# extension.net
KiCad netlist of a schematic drawn in EAGLE
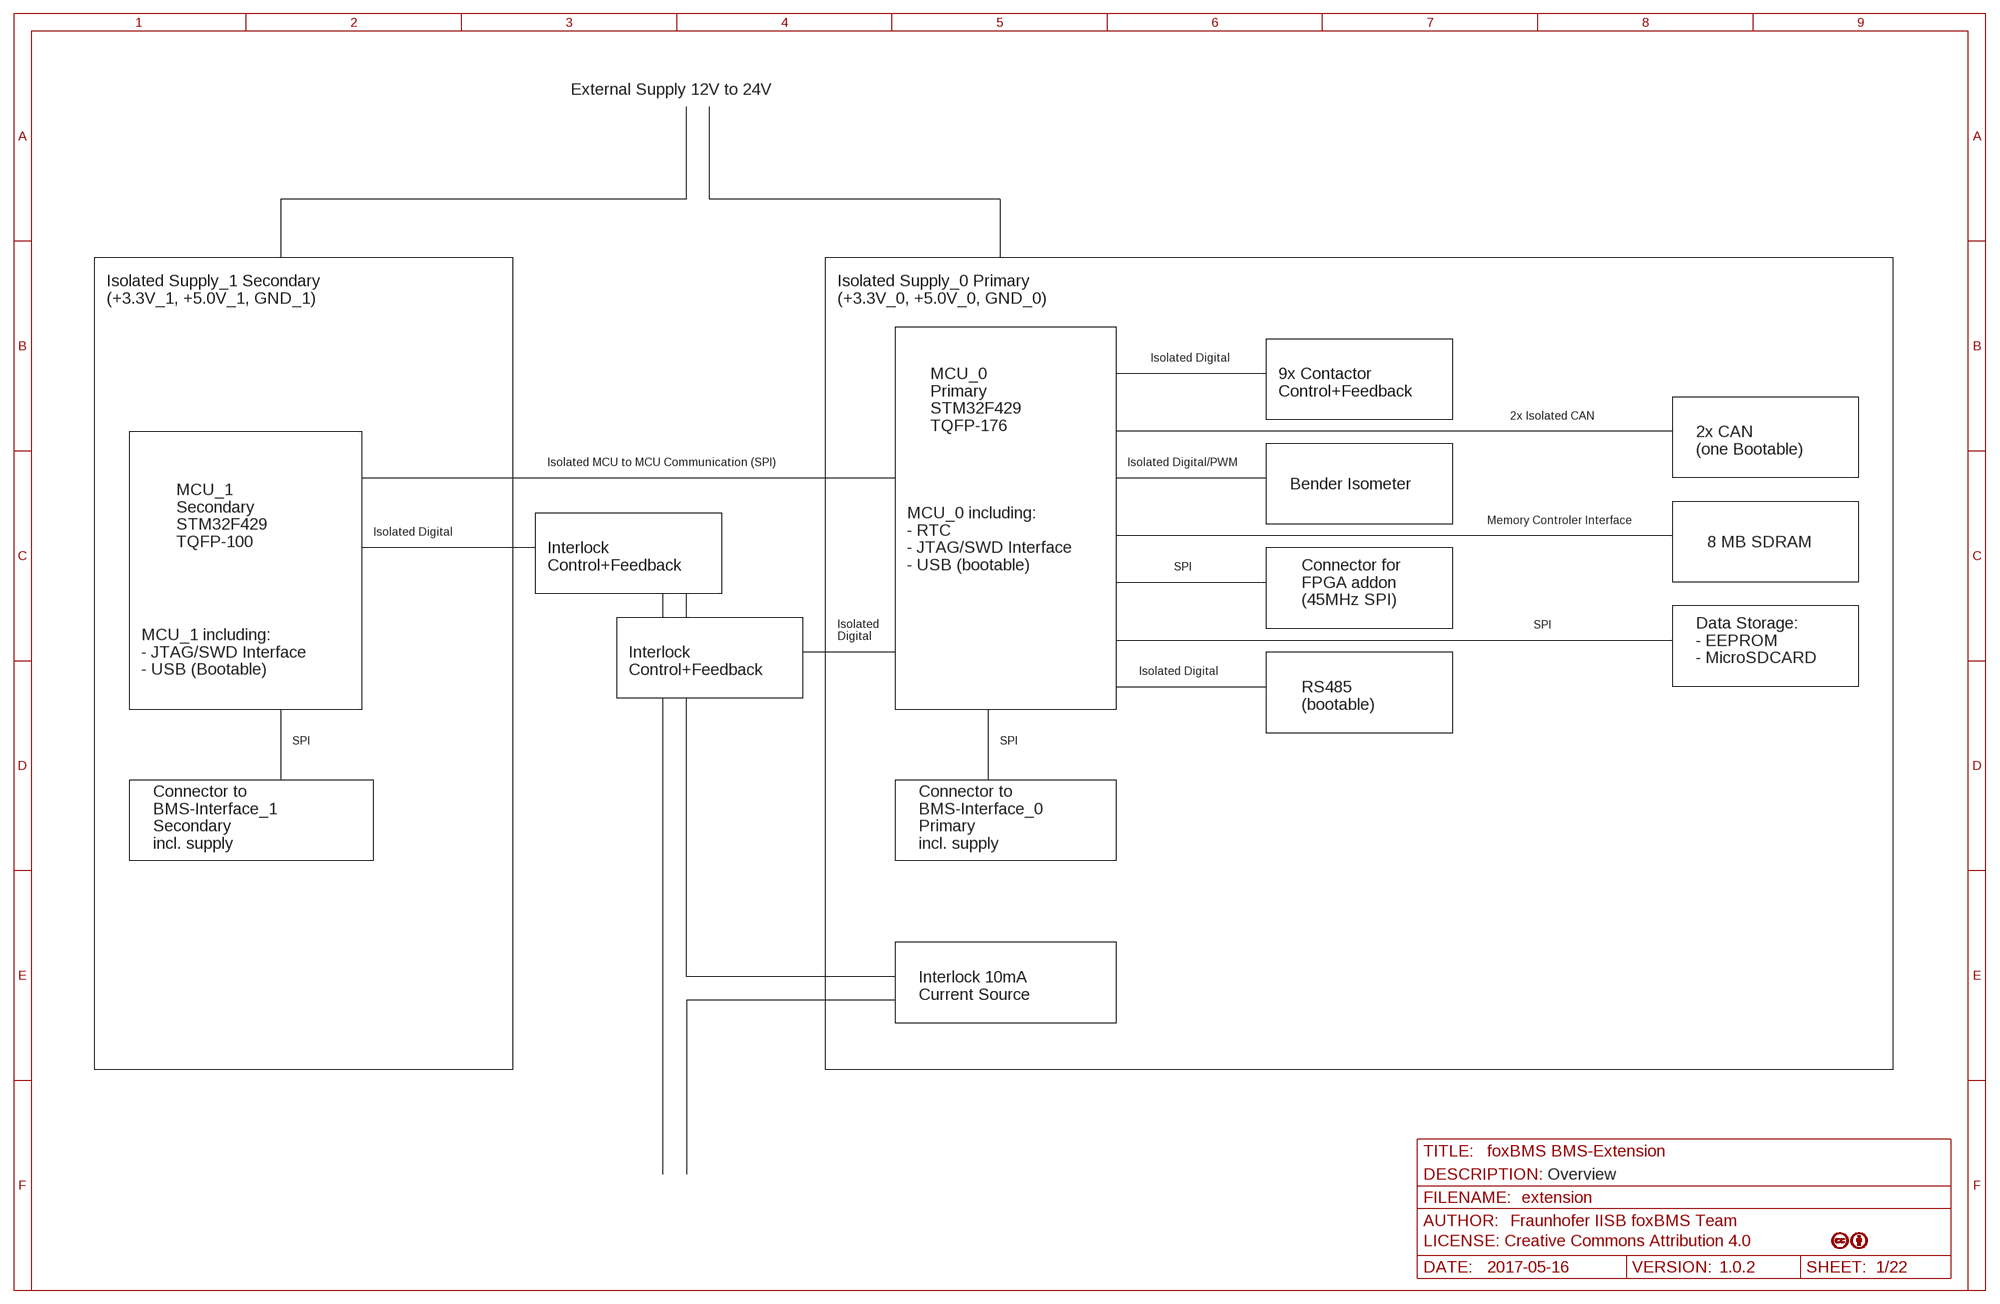
[diagram p0: schematic, sheet 1]
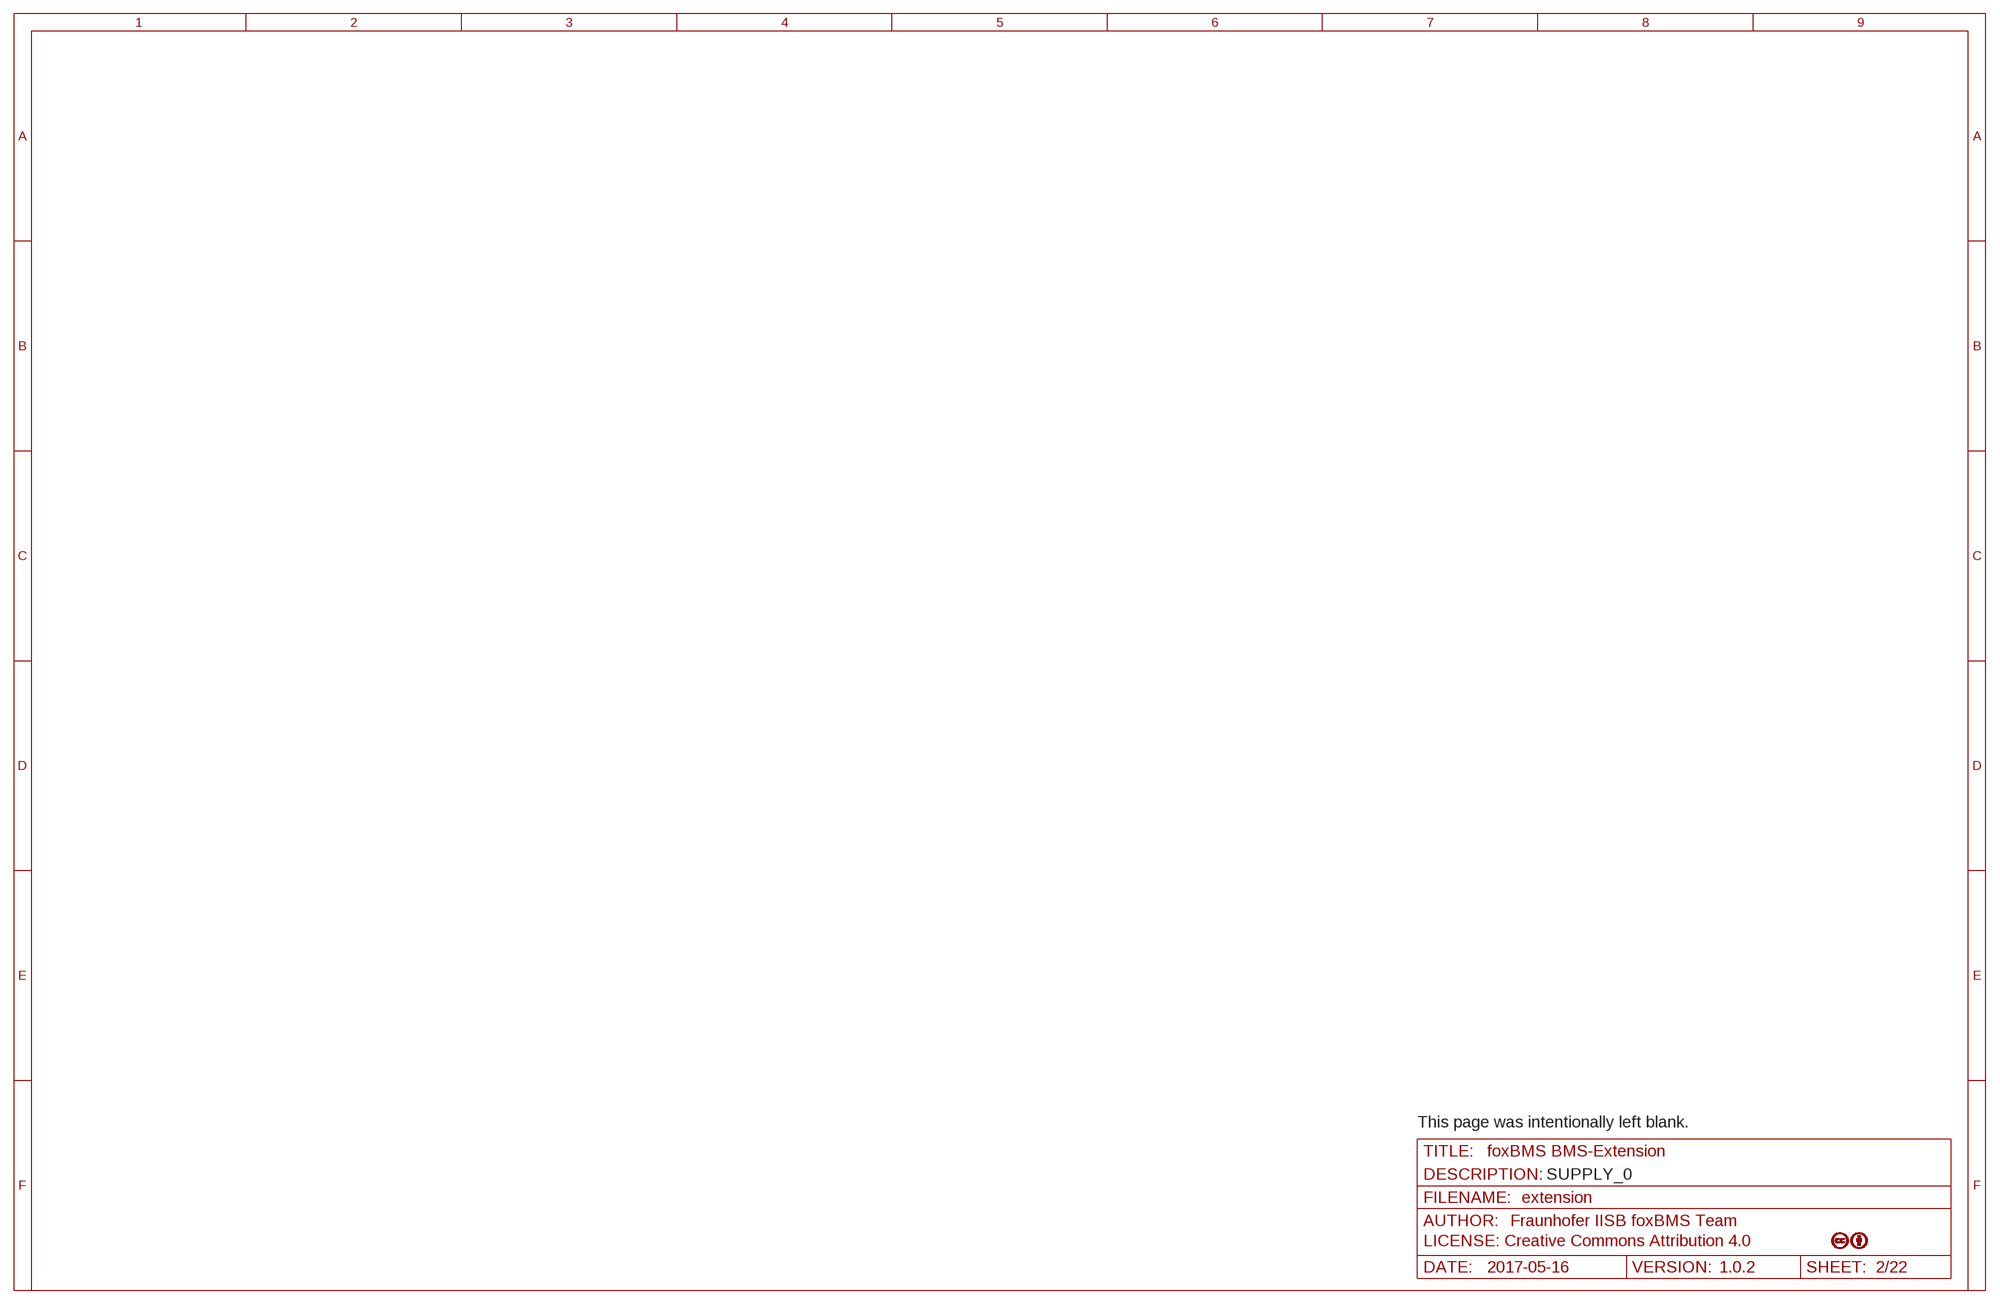
[diagram p1: schematic, sheet 2]
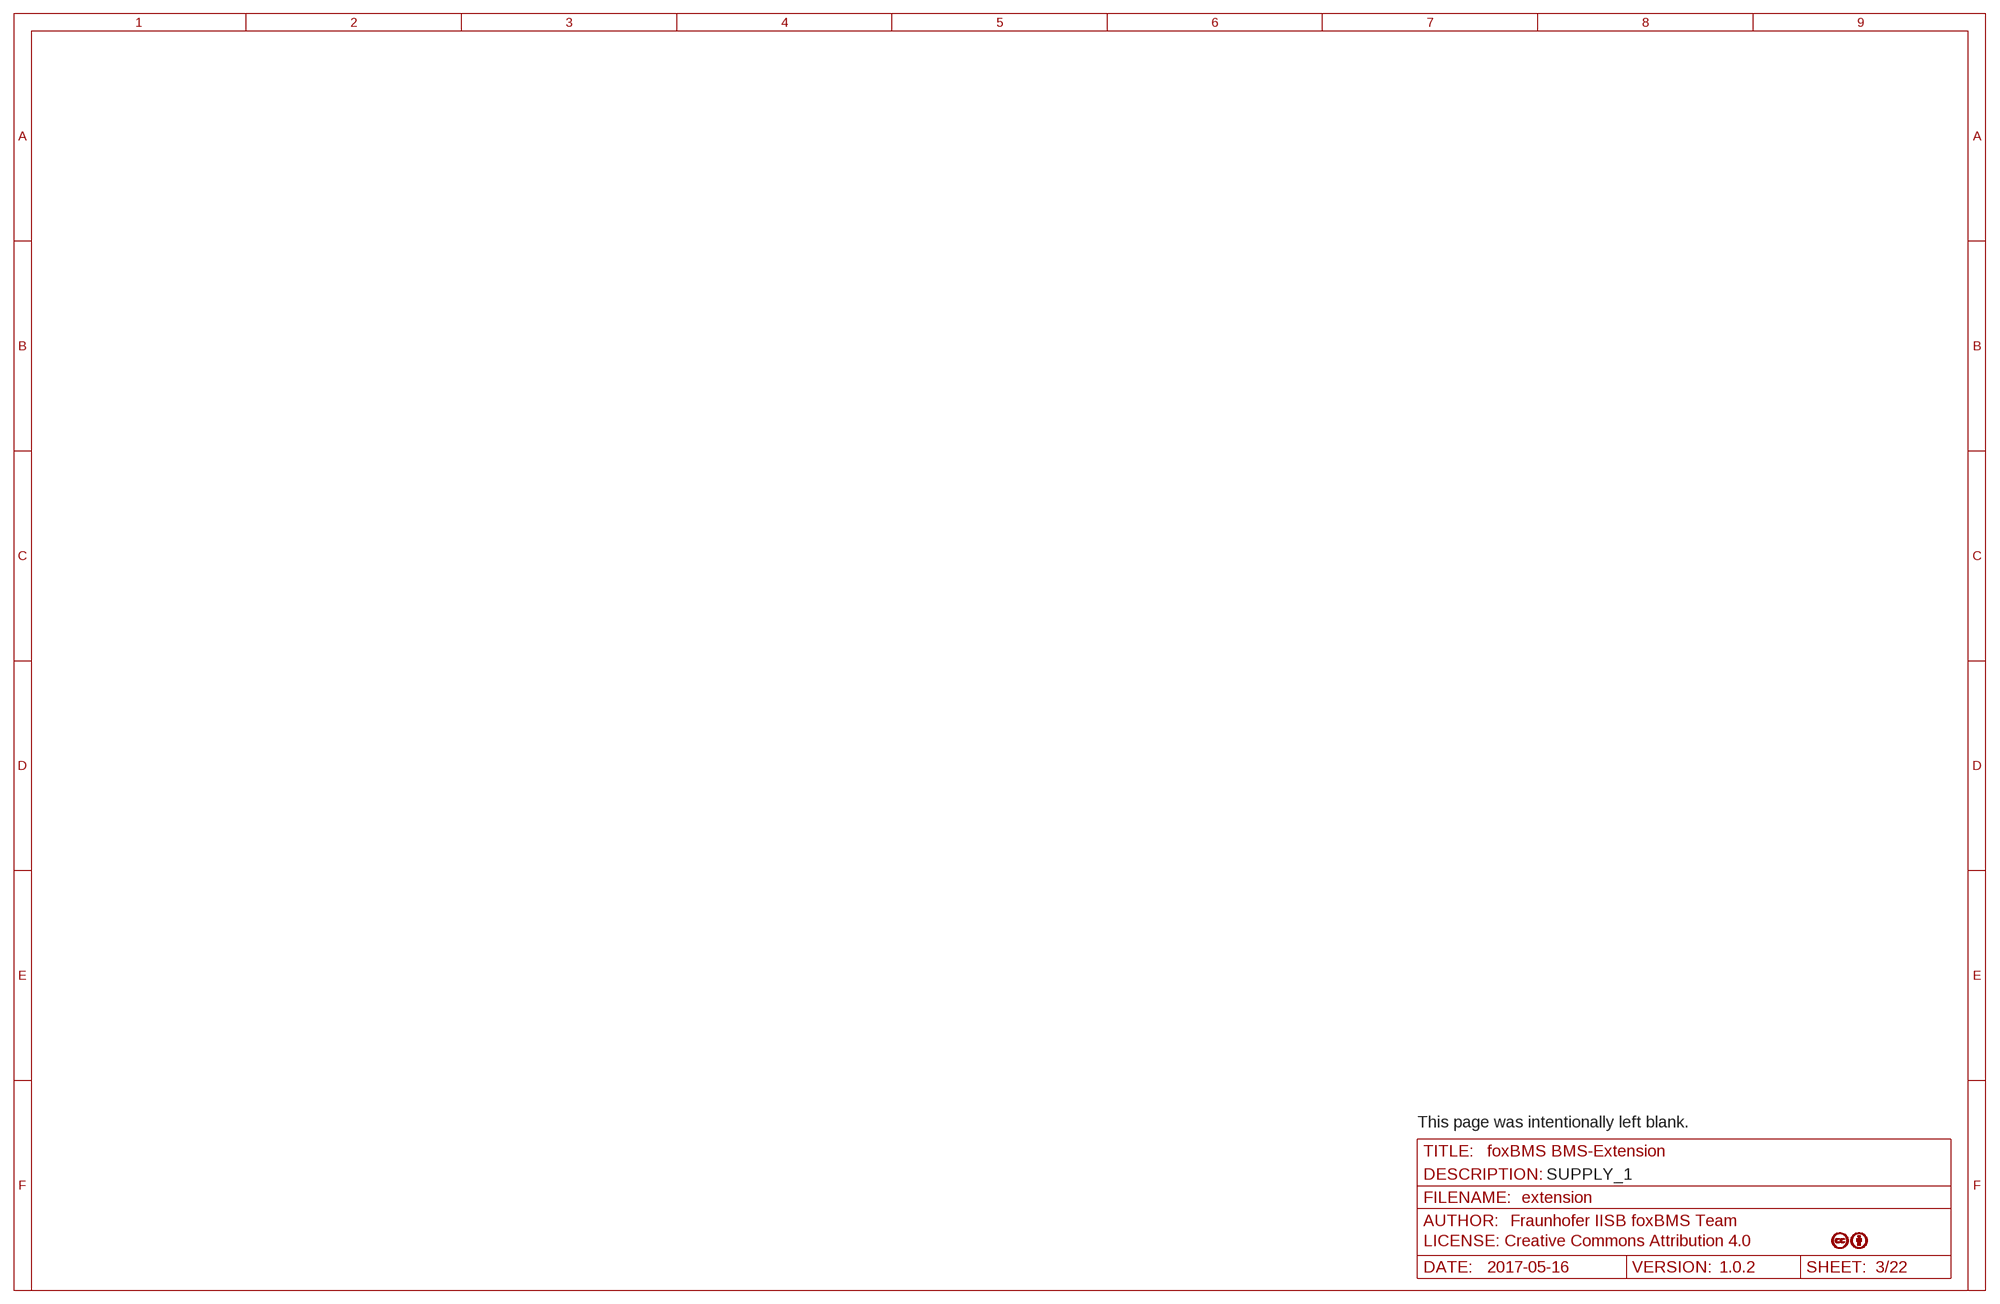
[diagram p2: schematic, sheet 3]
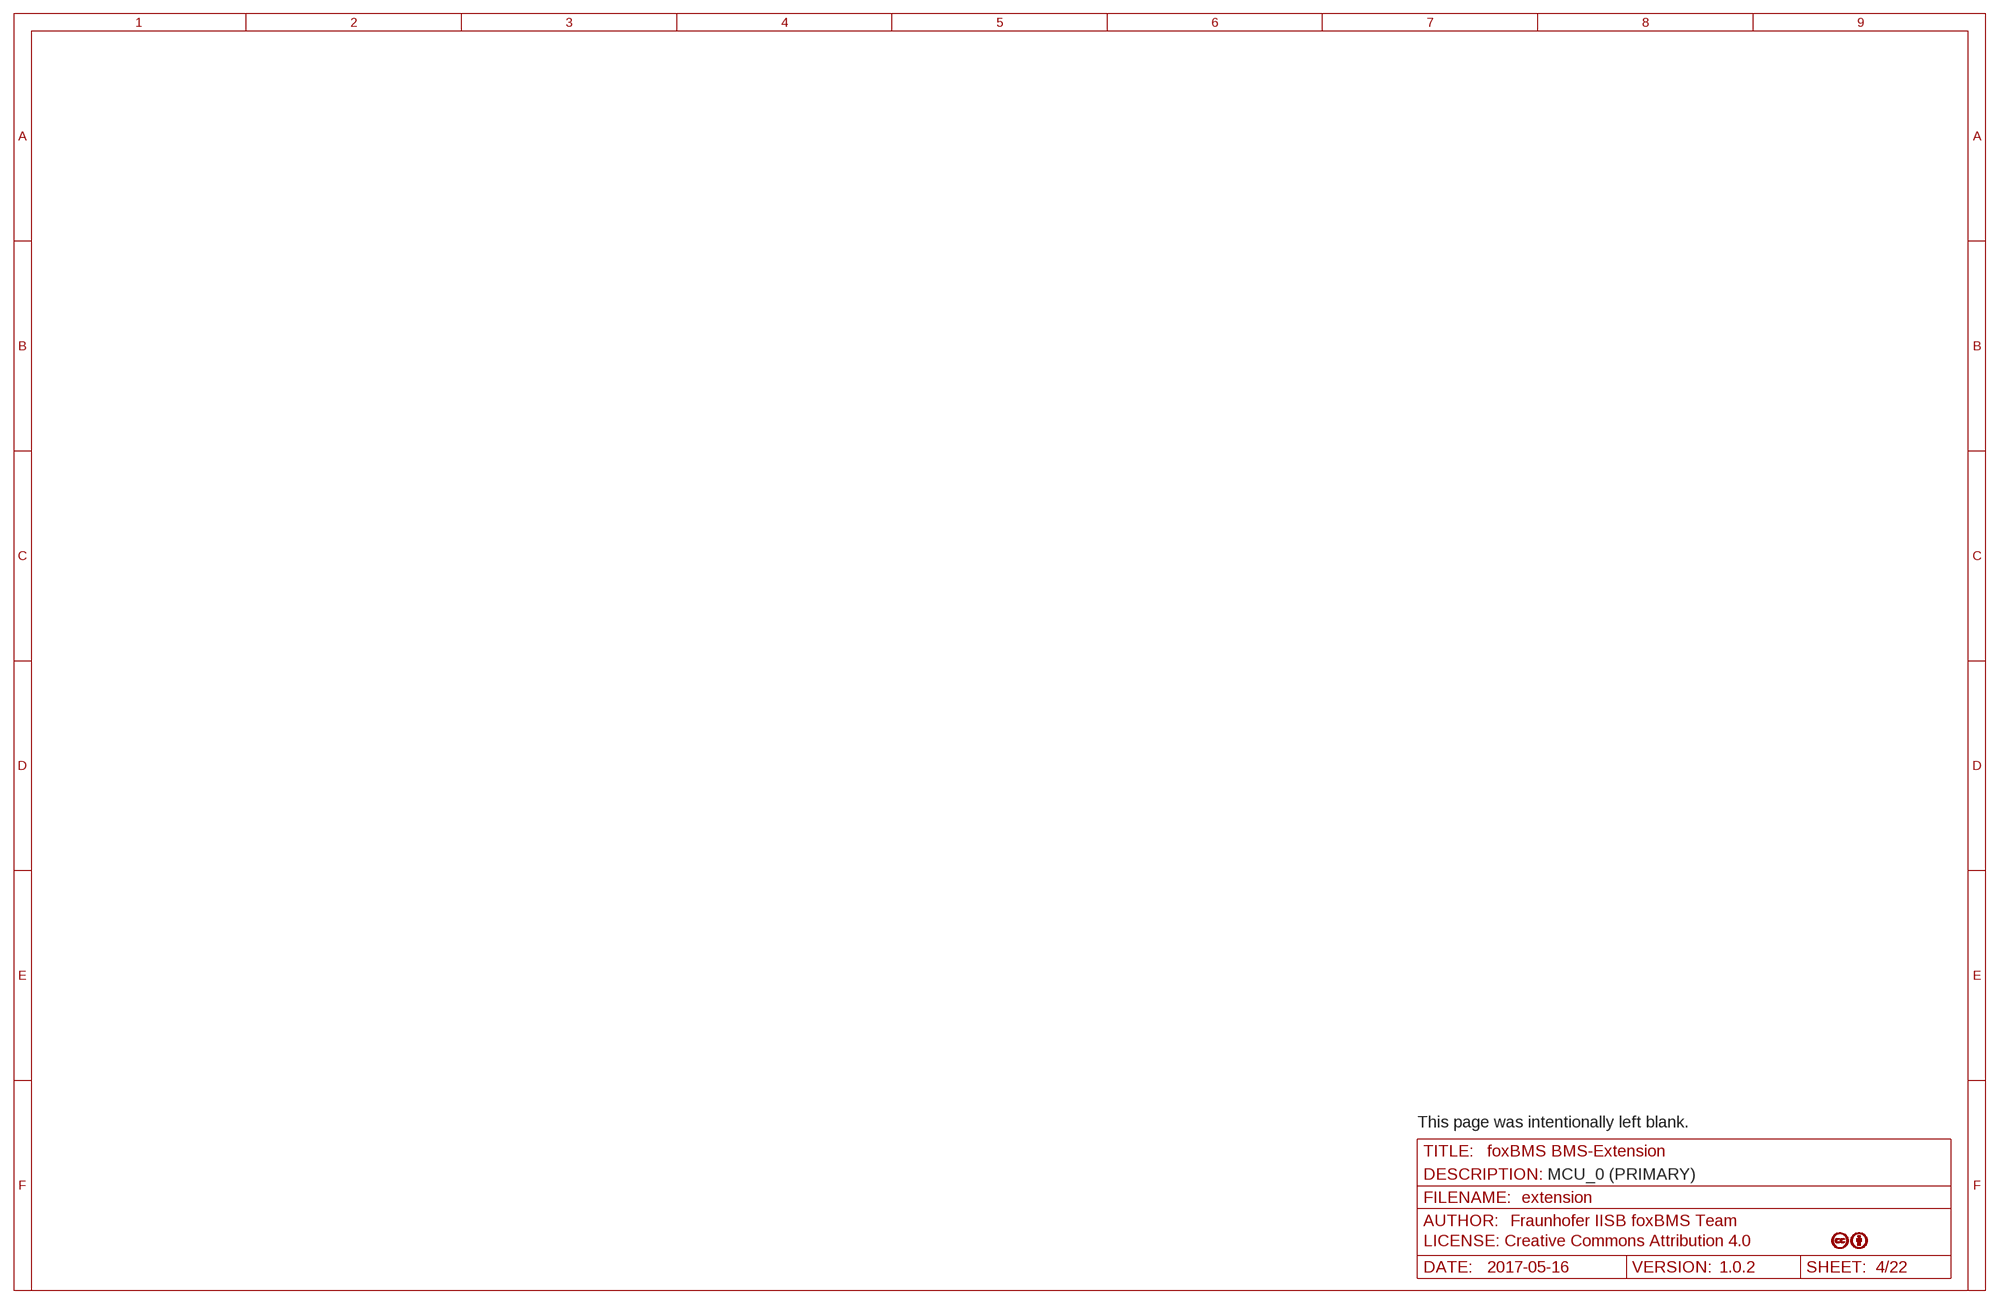
[diagram p3: schematic, sheet 4]
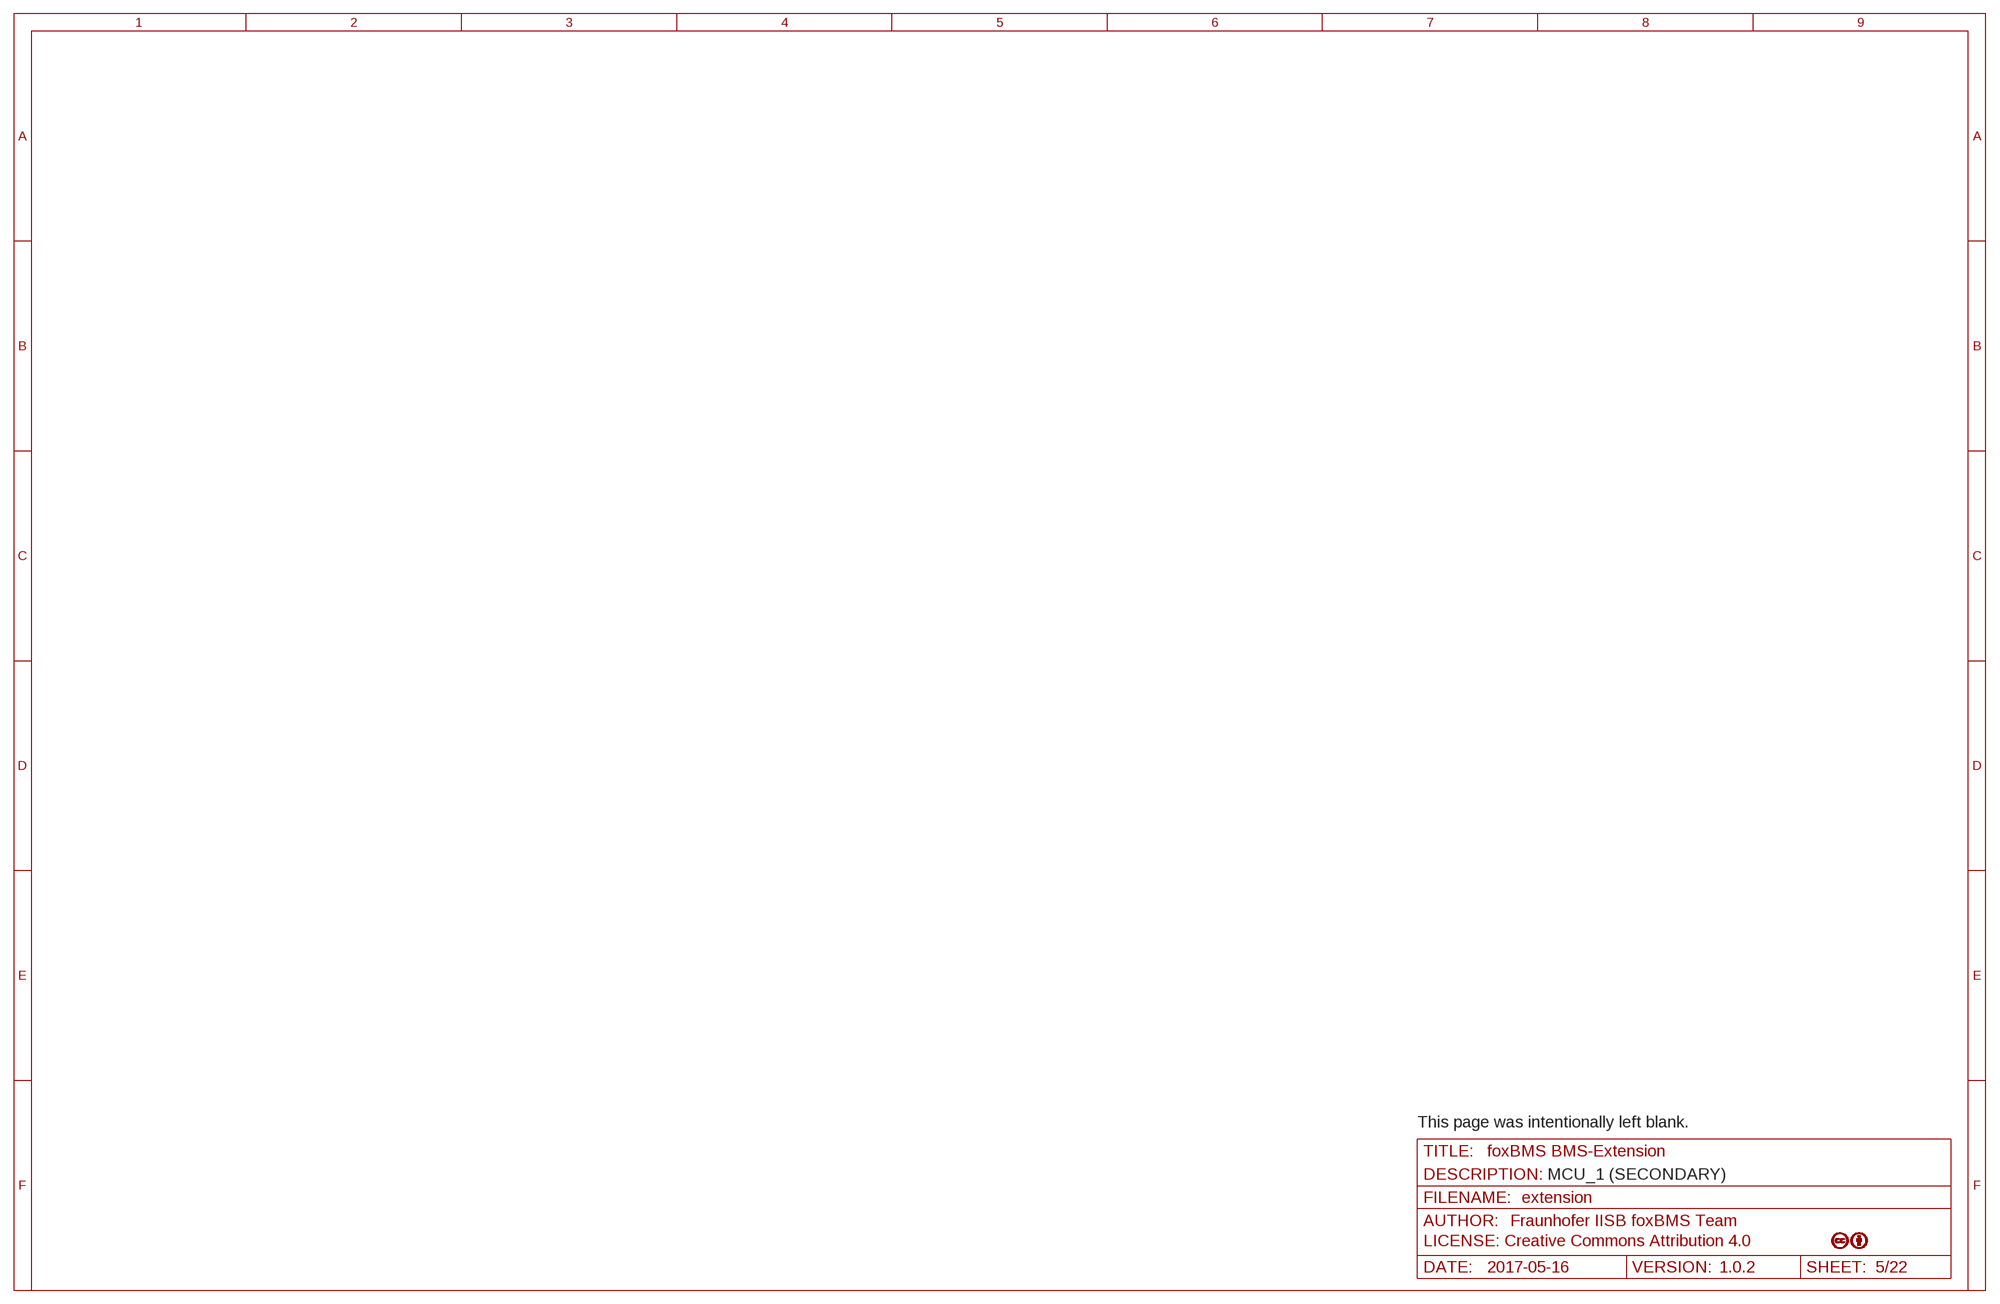
[diagram p4: schematic, sheet 5]
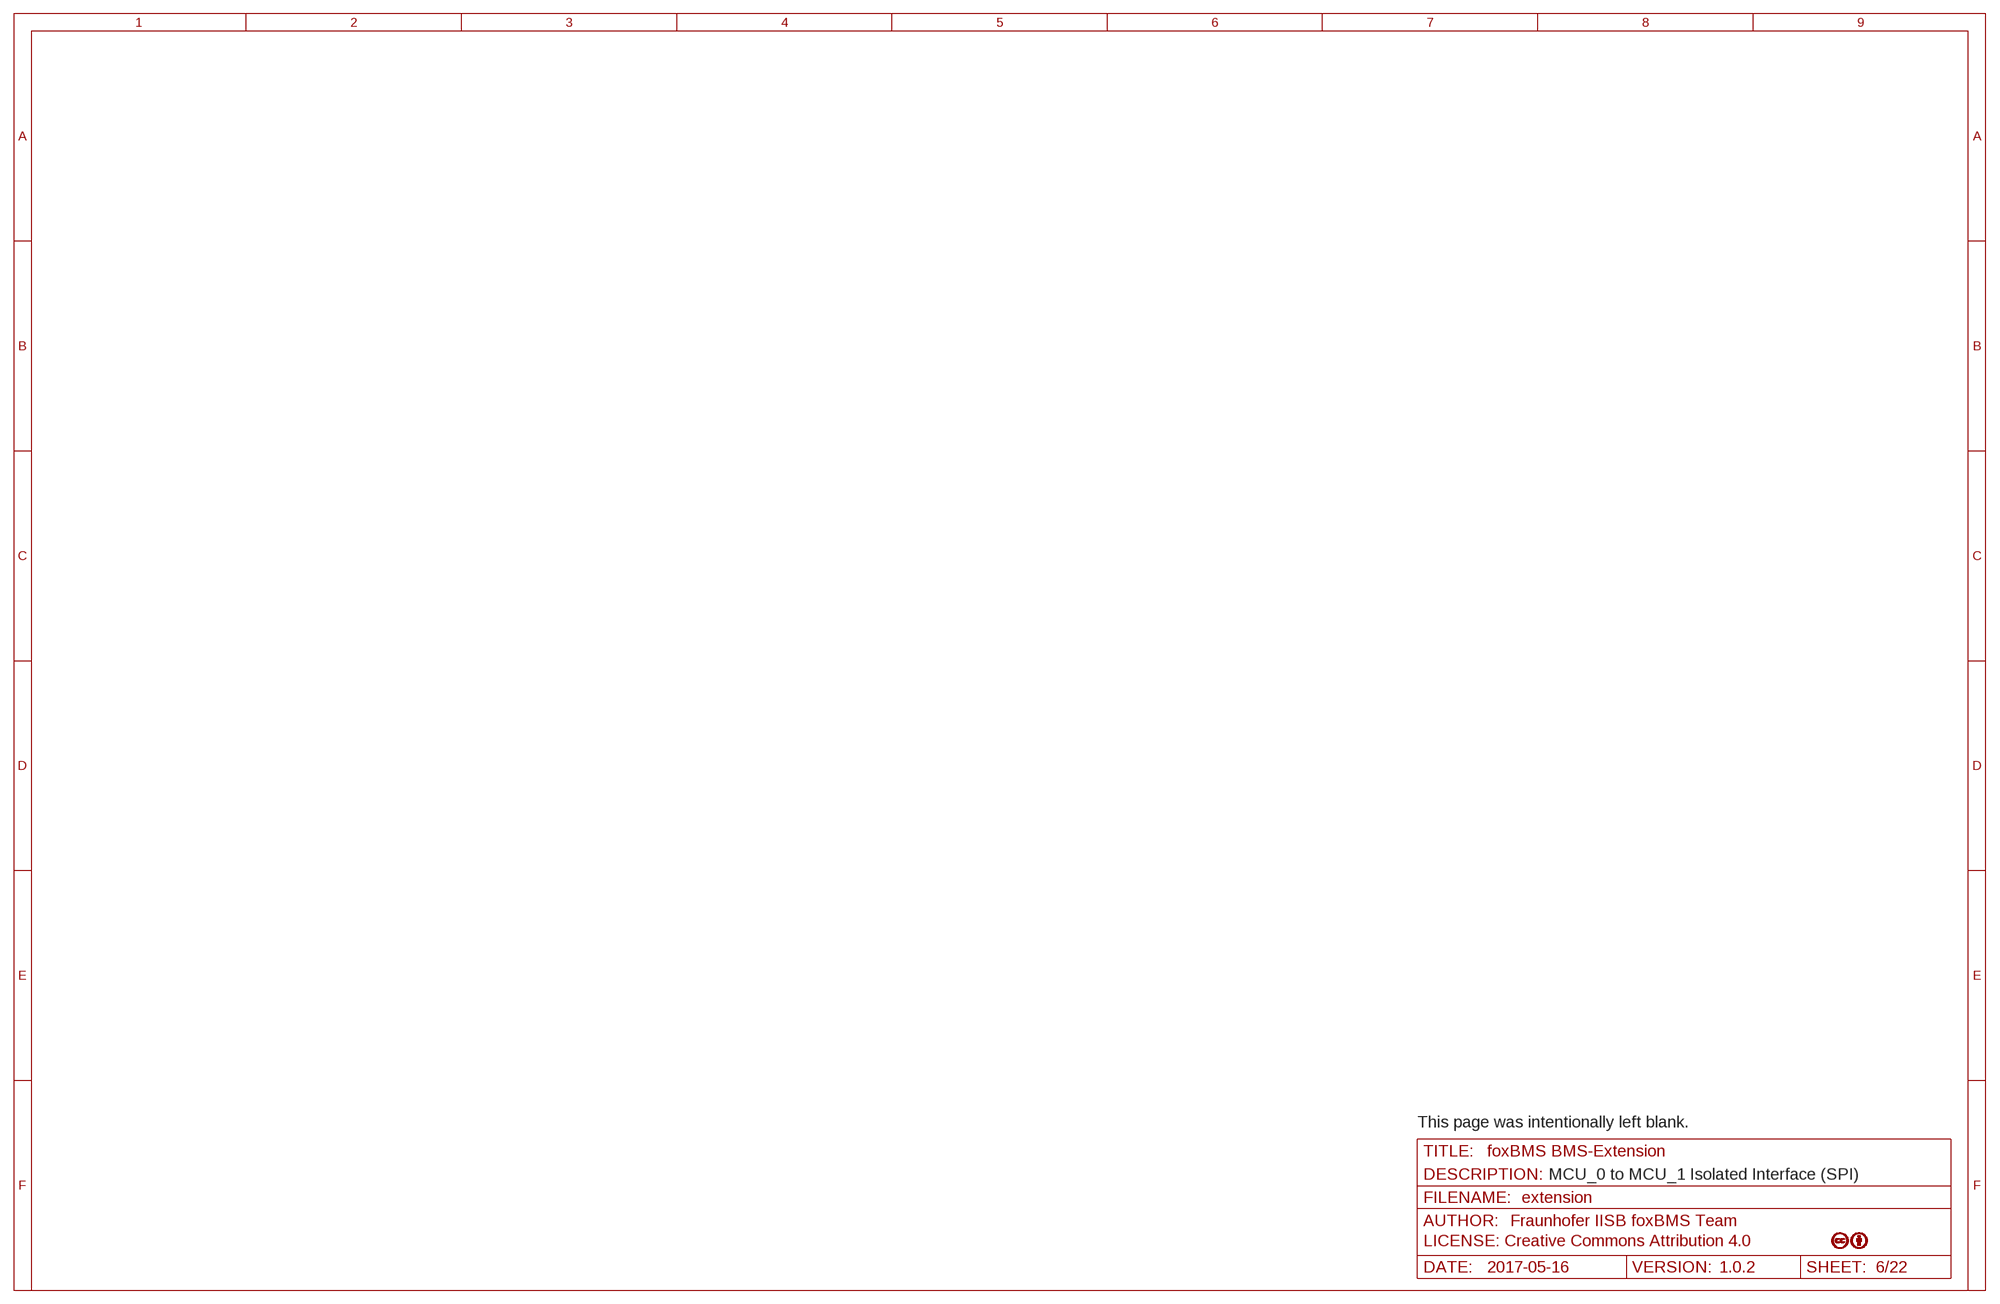
[diagram p5: schematic, sheet 6]
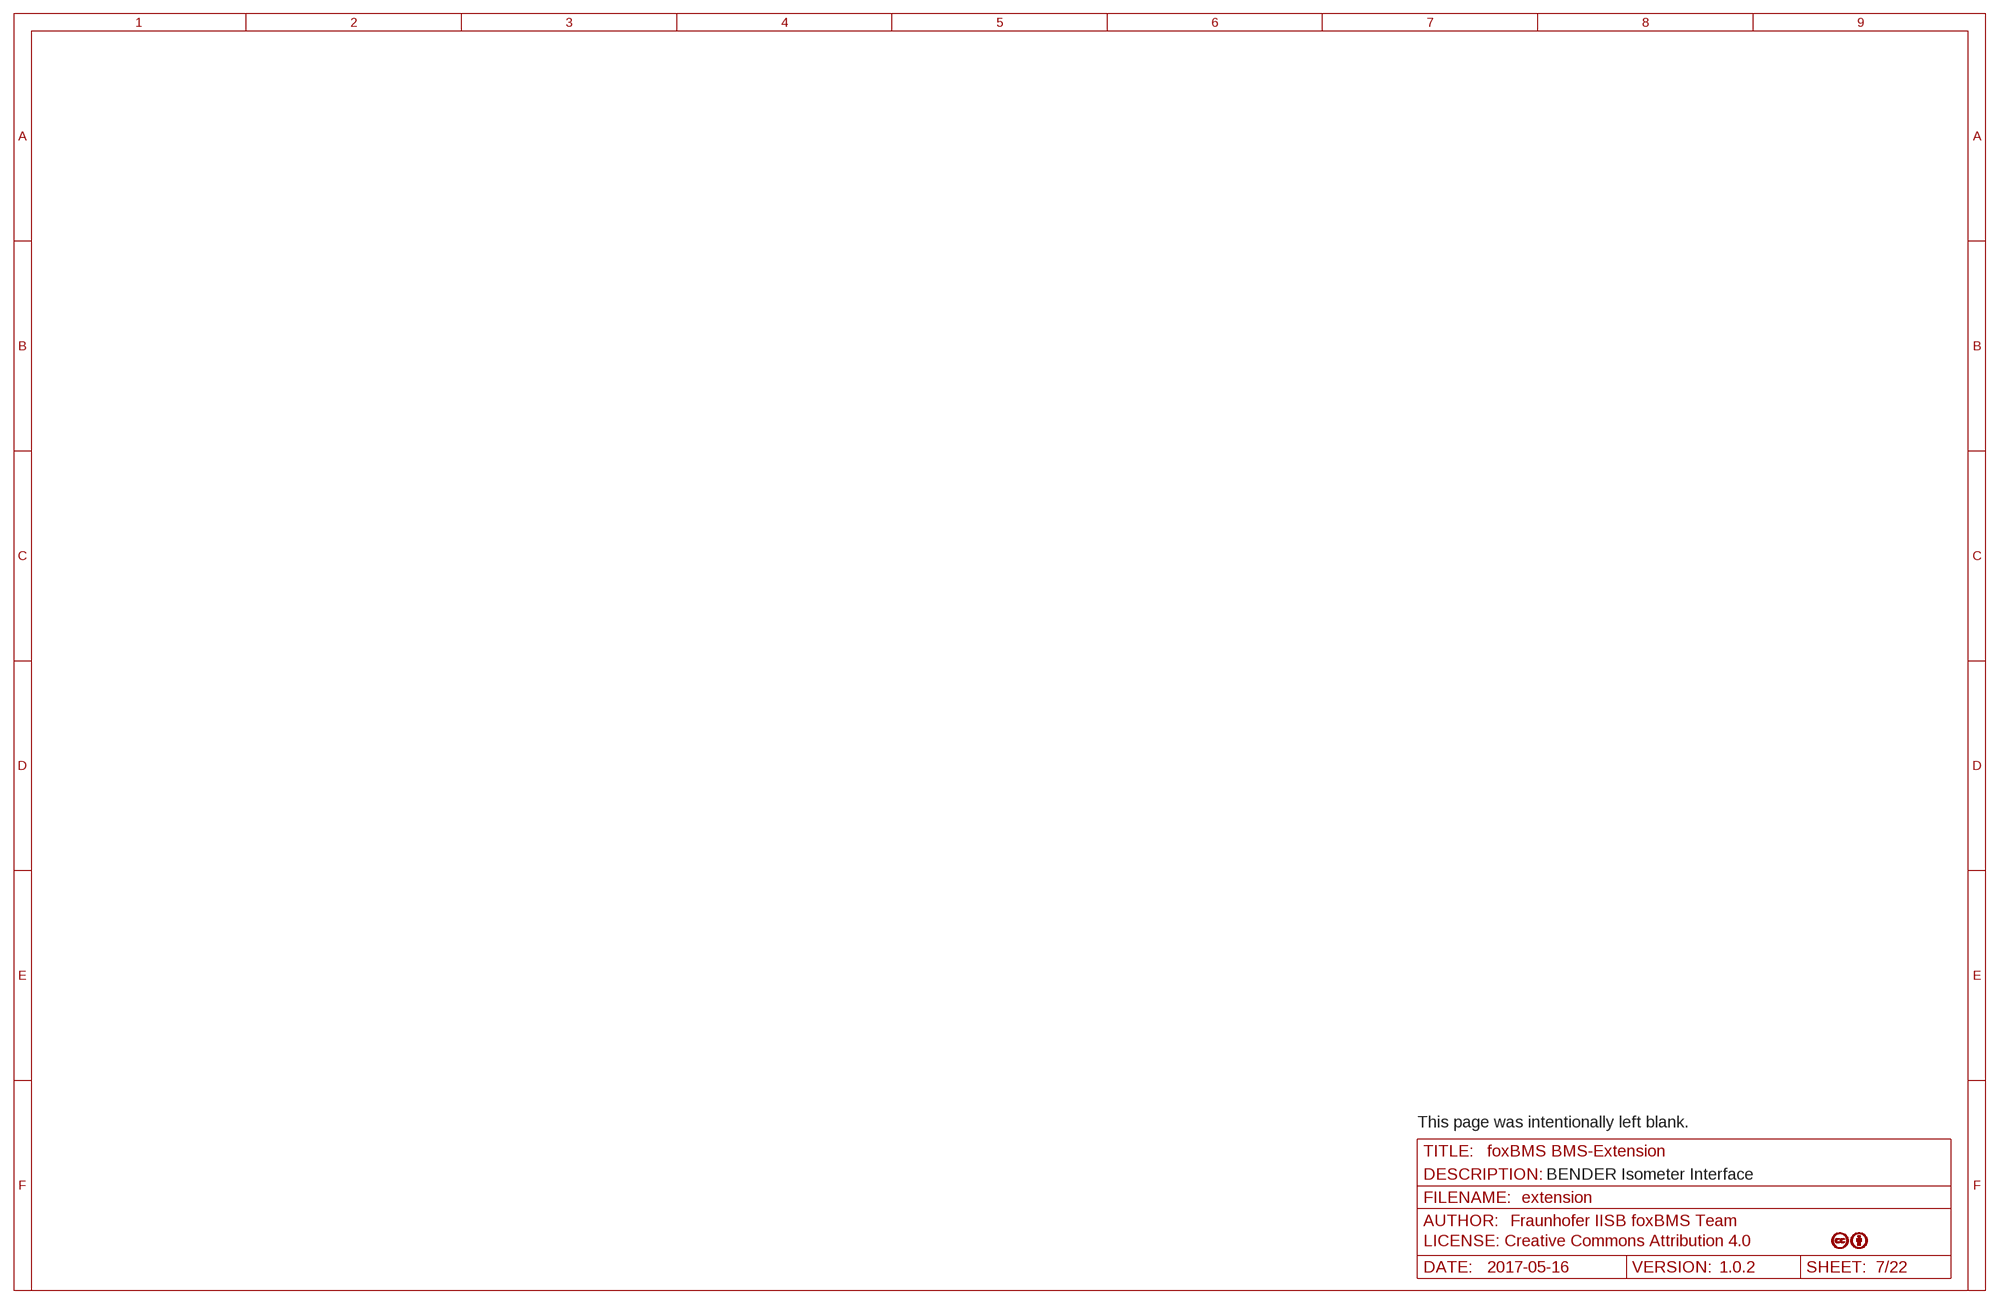
[diagram p6: schematic, sheet 7]
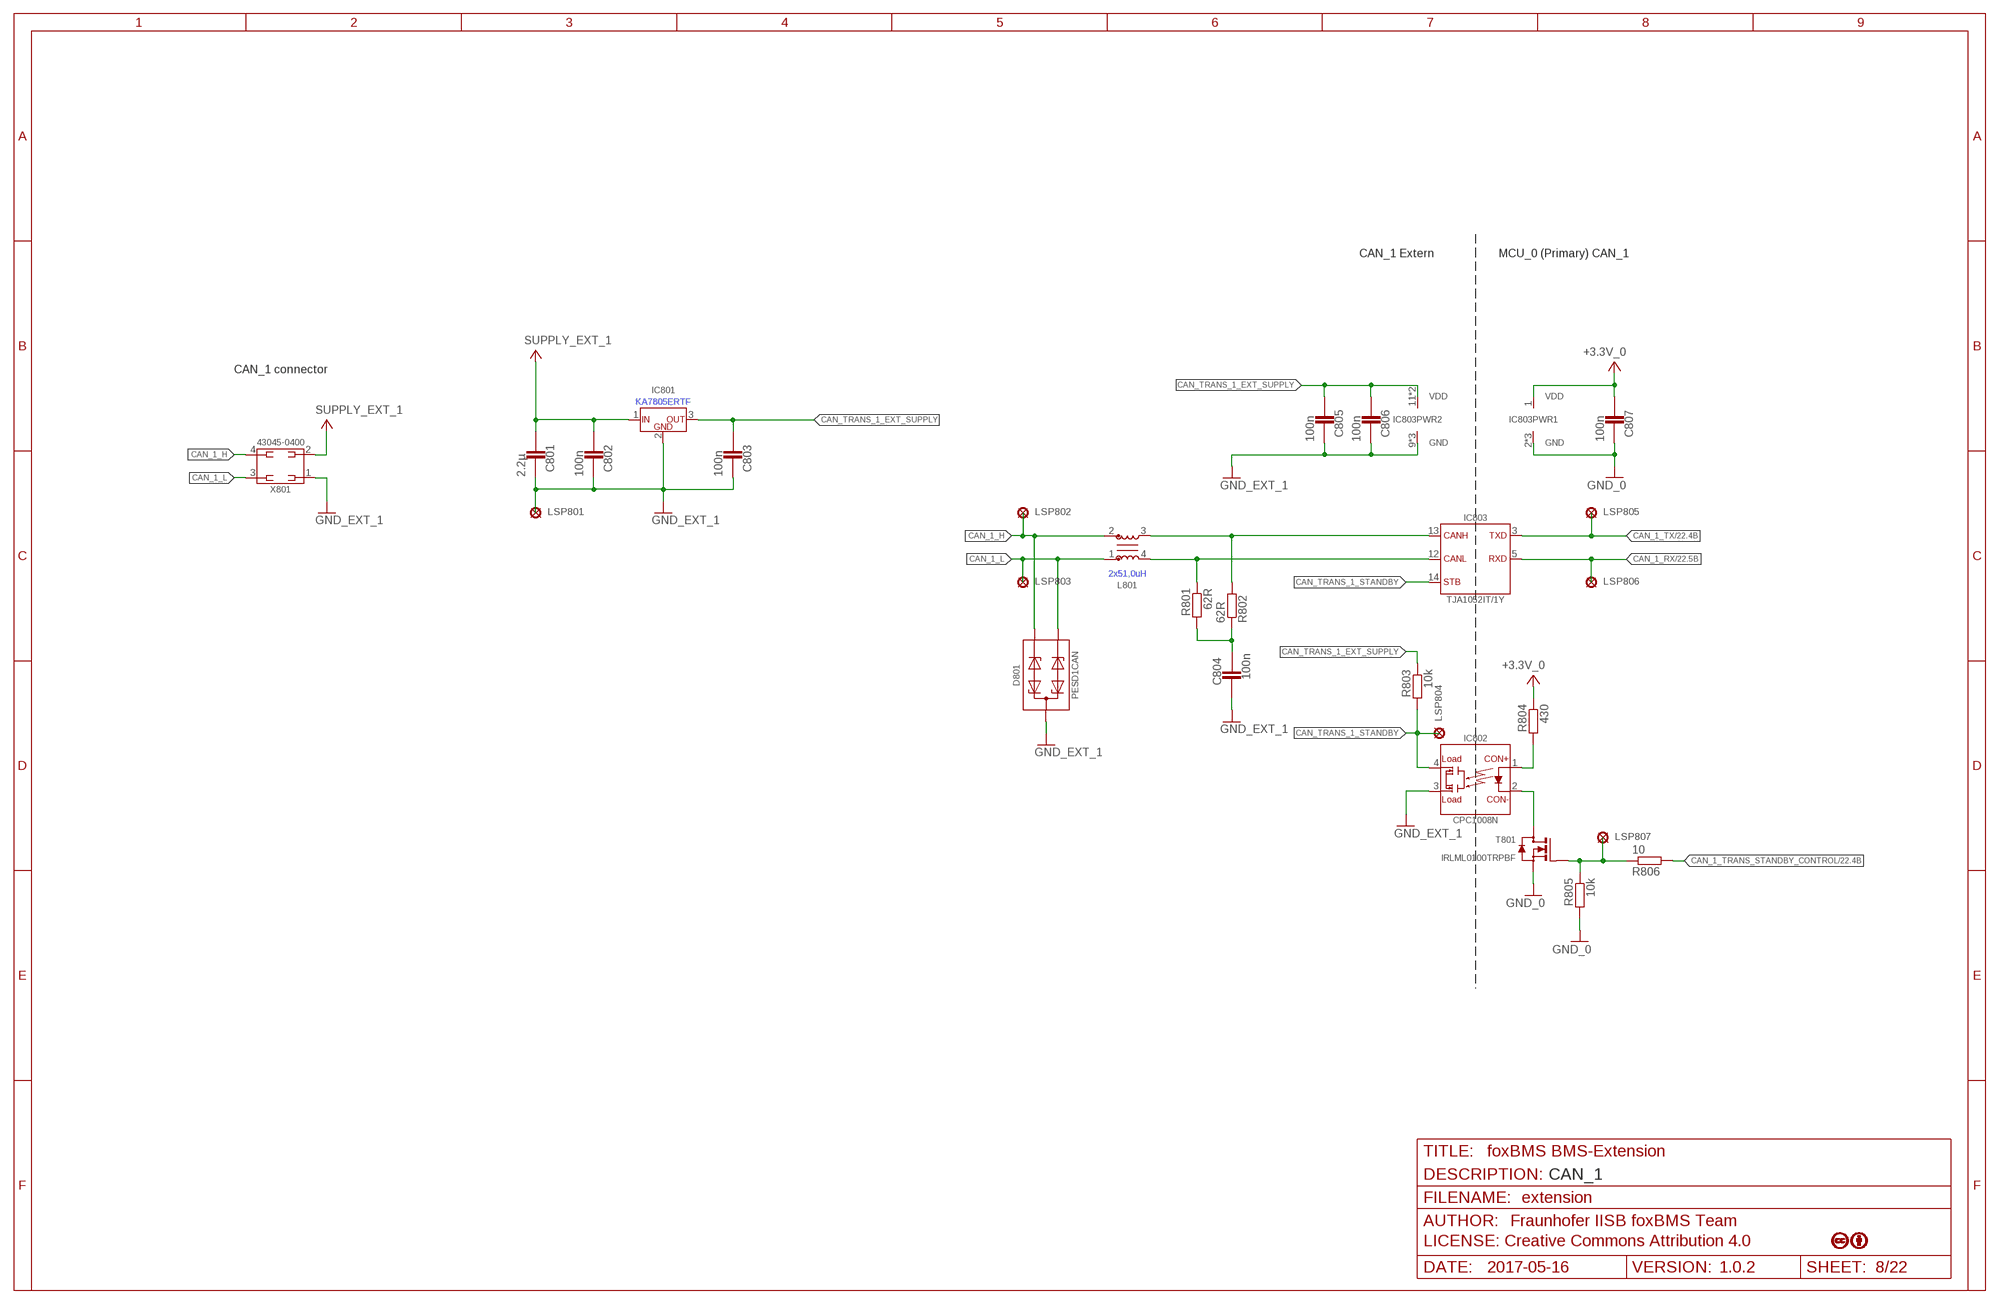
[diagram p7: schematic, sheet 8]
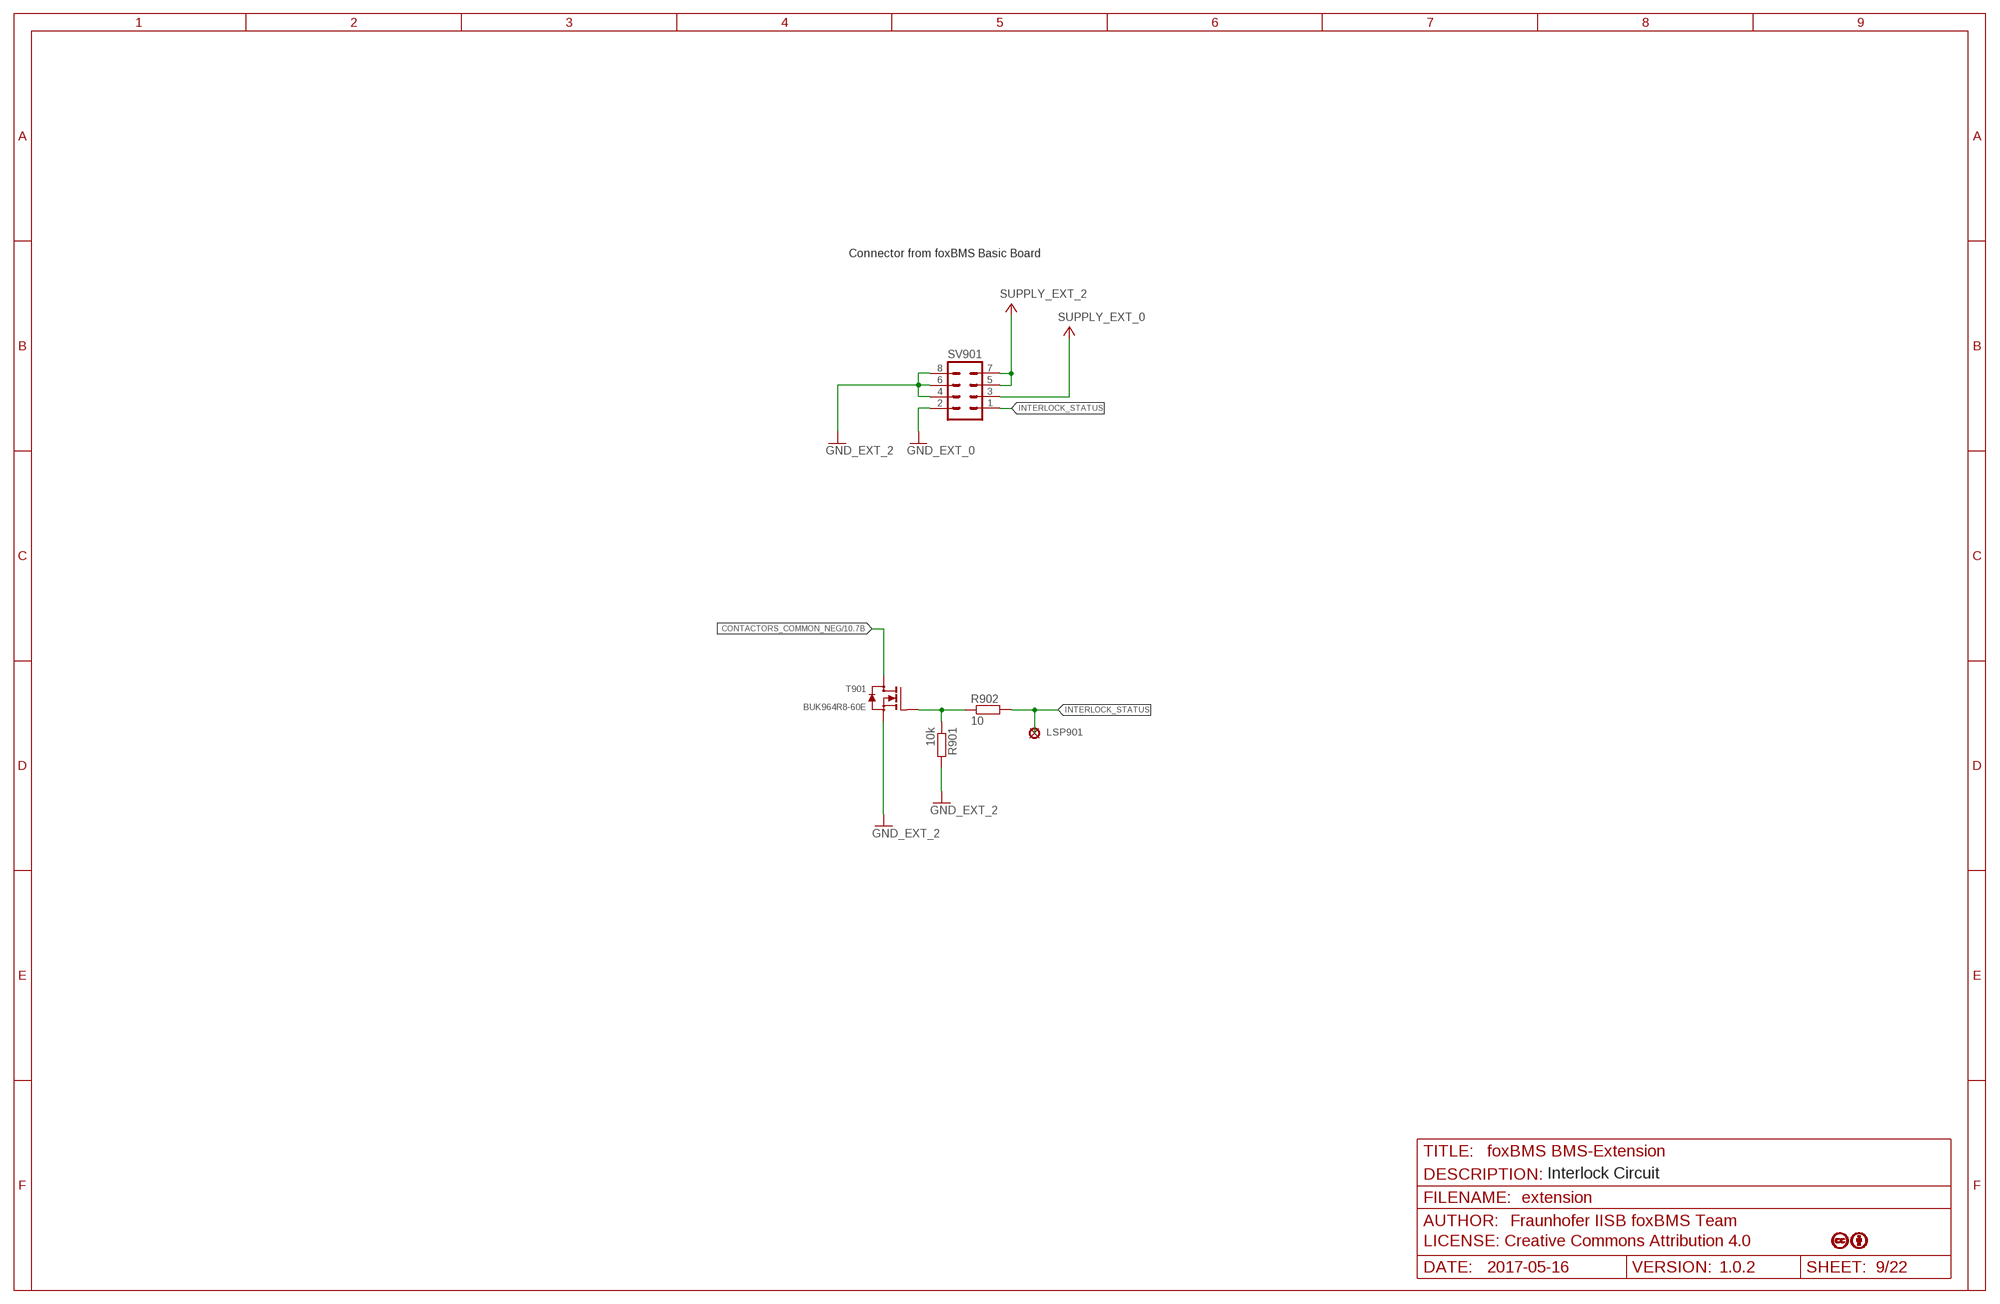
[diagram p8: schematic, sheet 9]
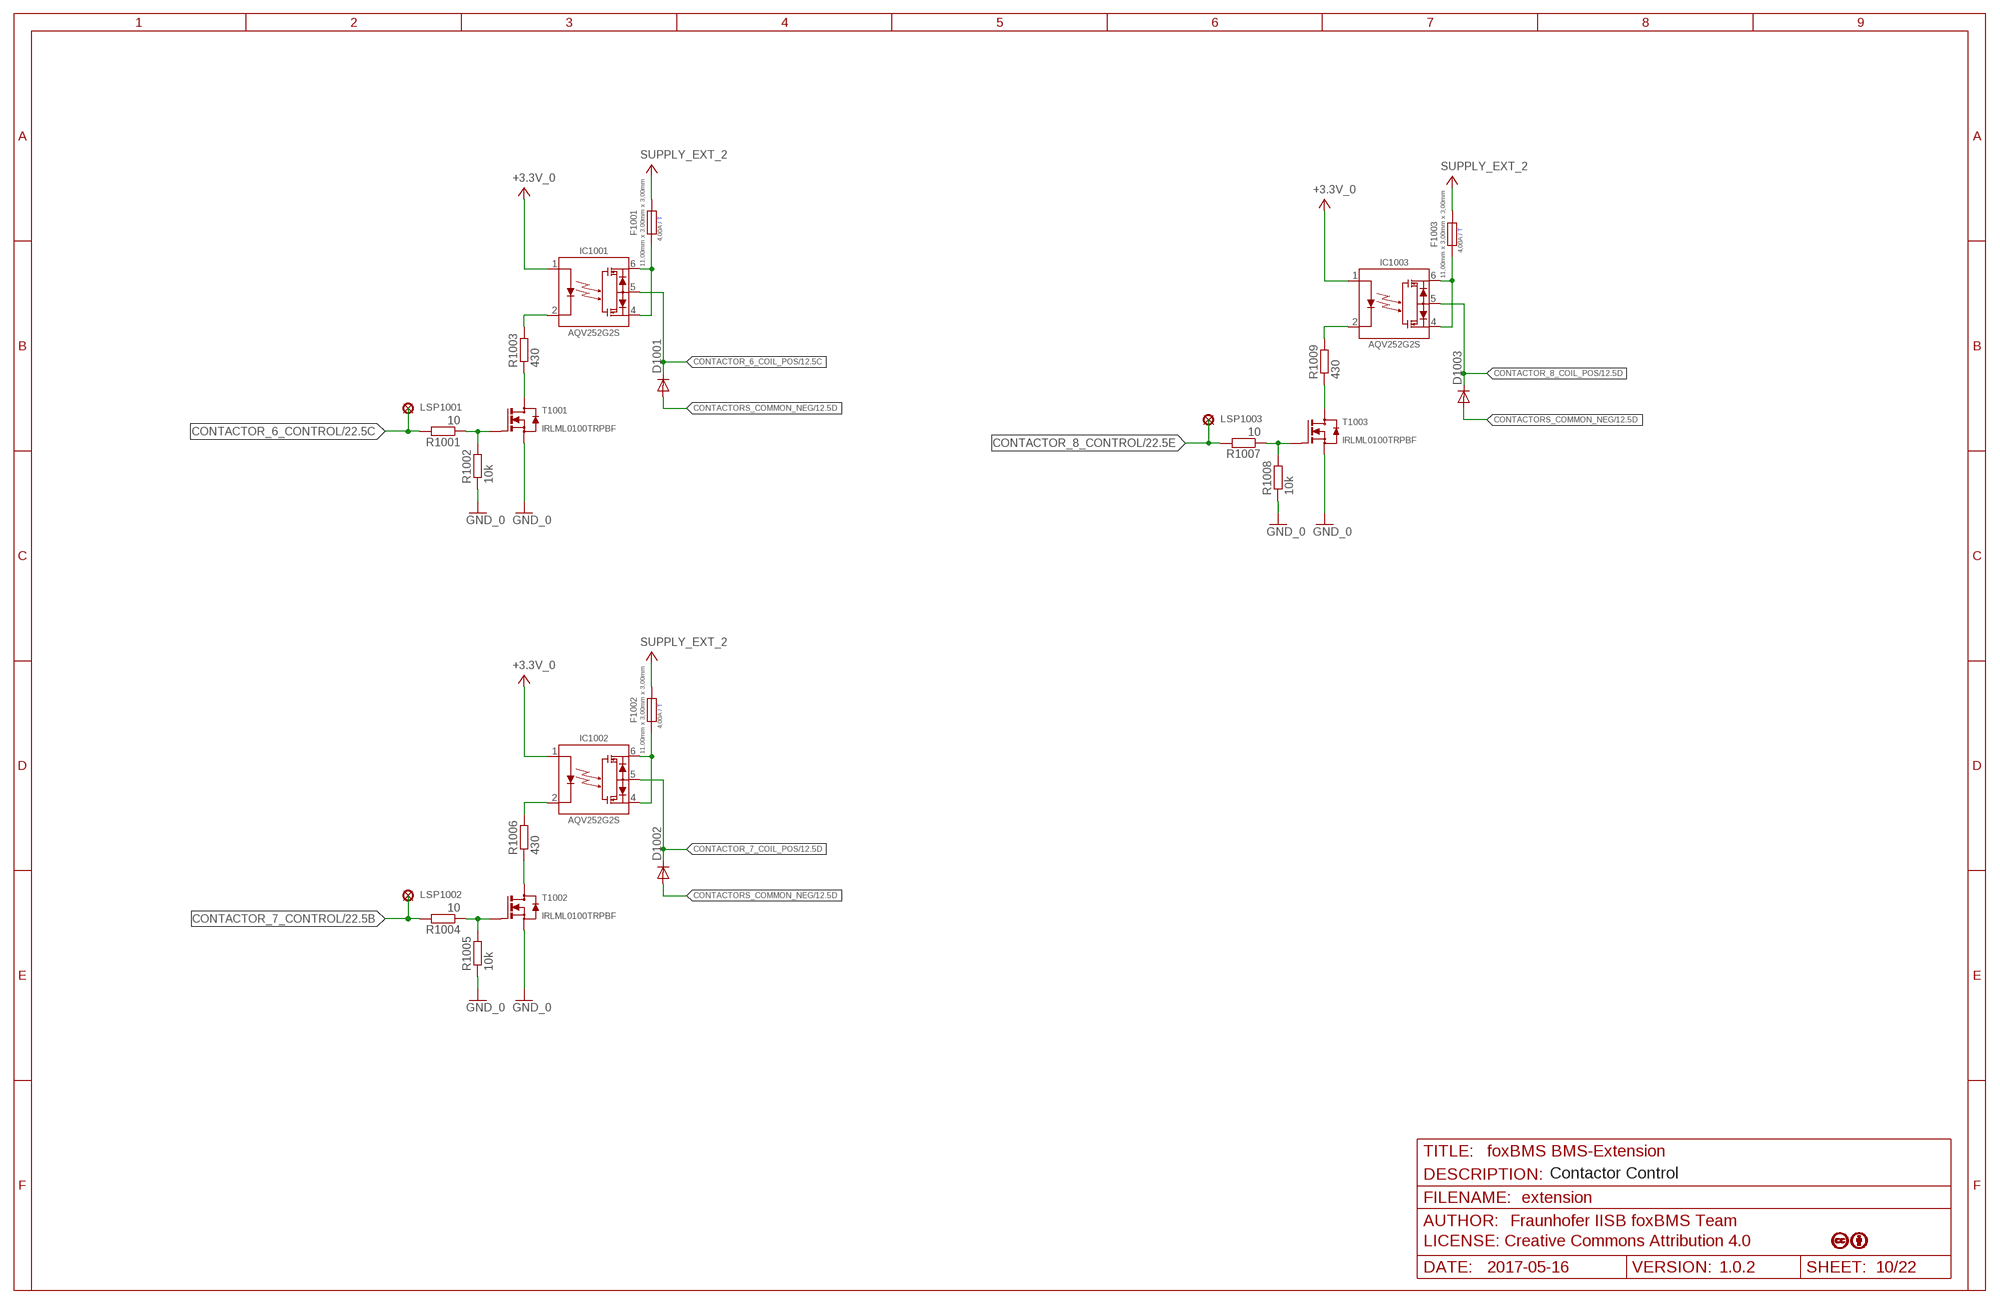
[diagram p9: schematic, sheet 10]
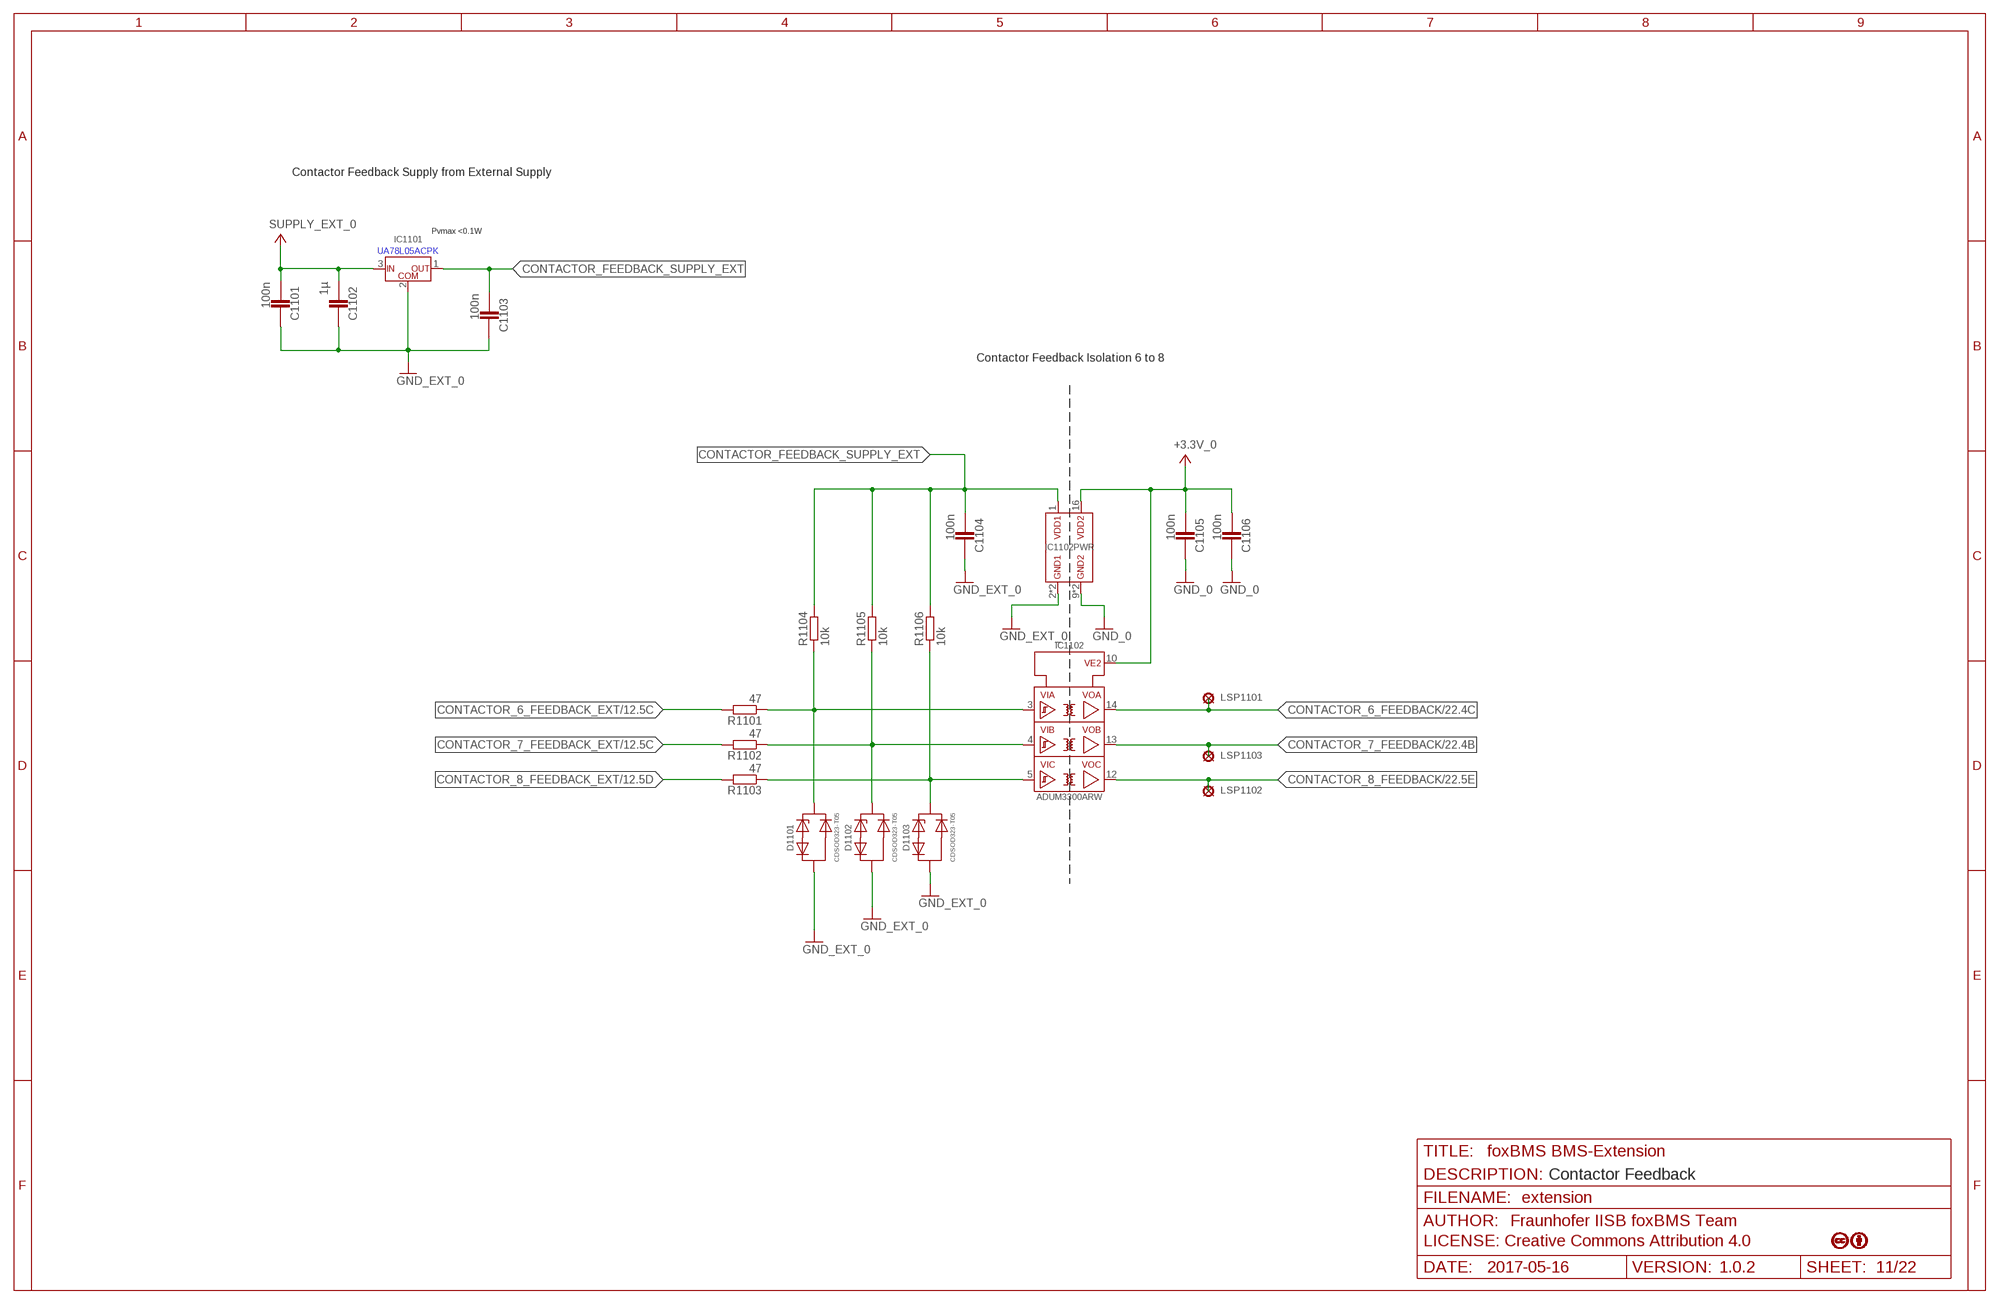
[diagram p10: schematic, sheet 11]
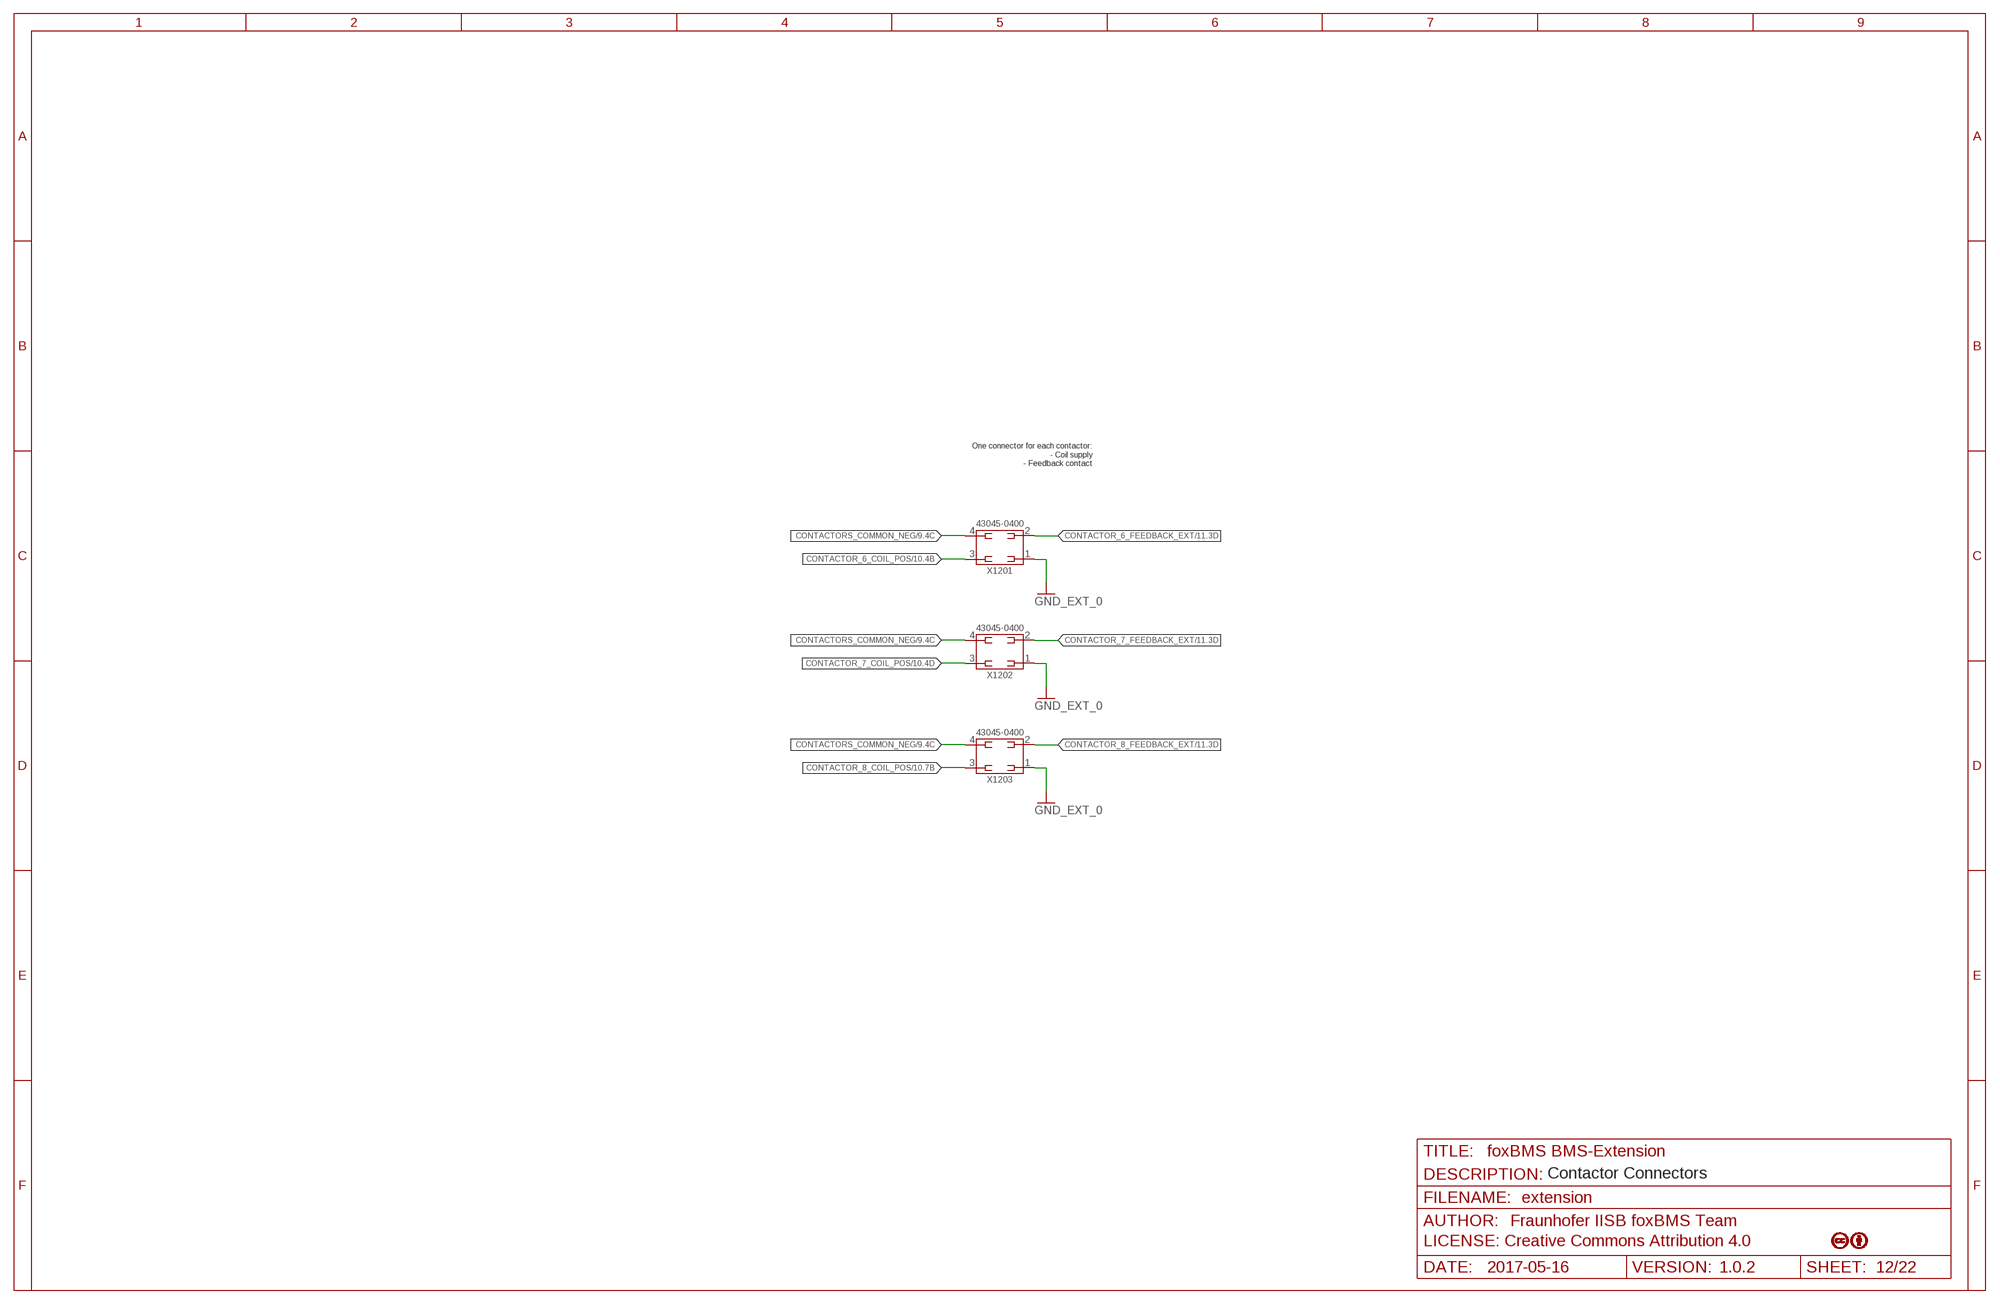
[diagram p11: schematic, sheet 12]
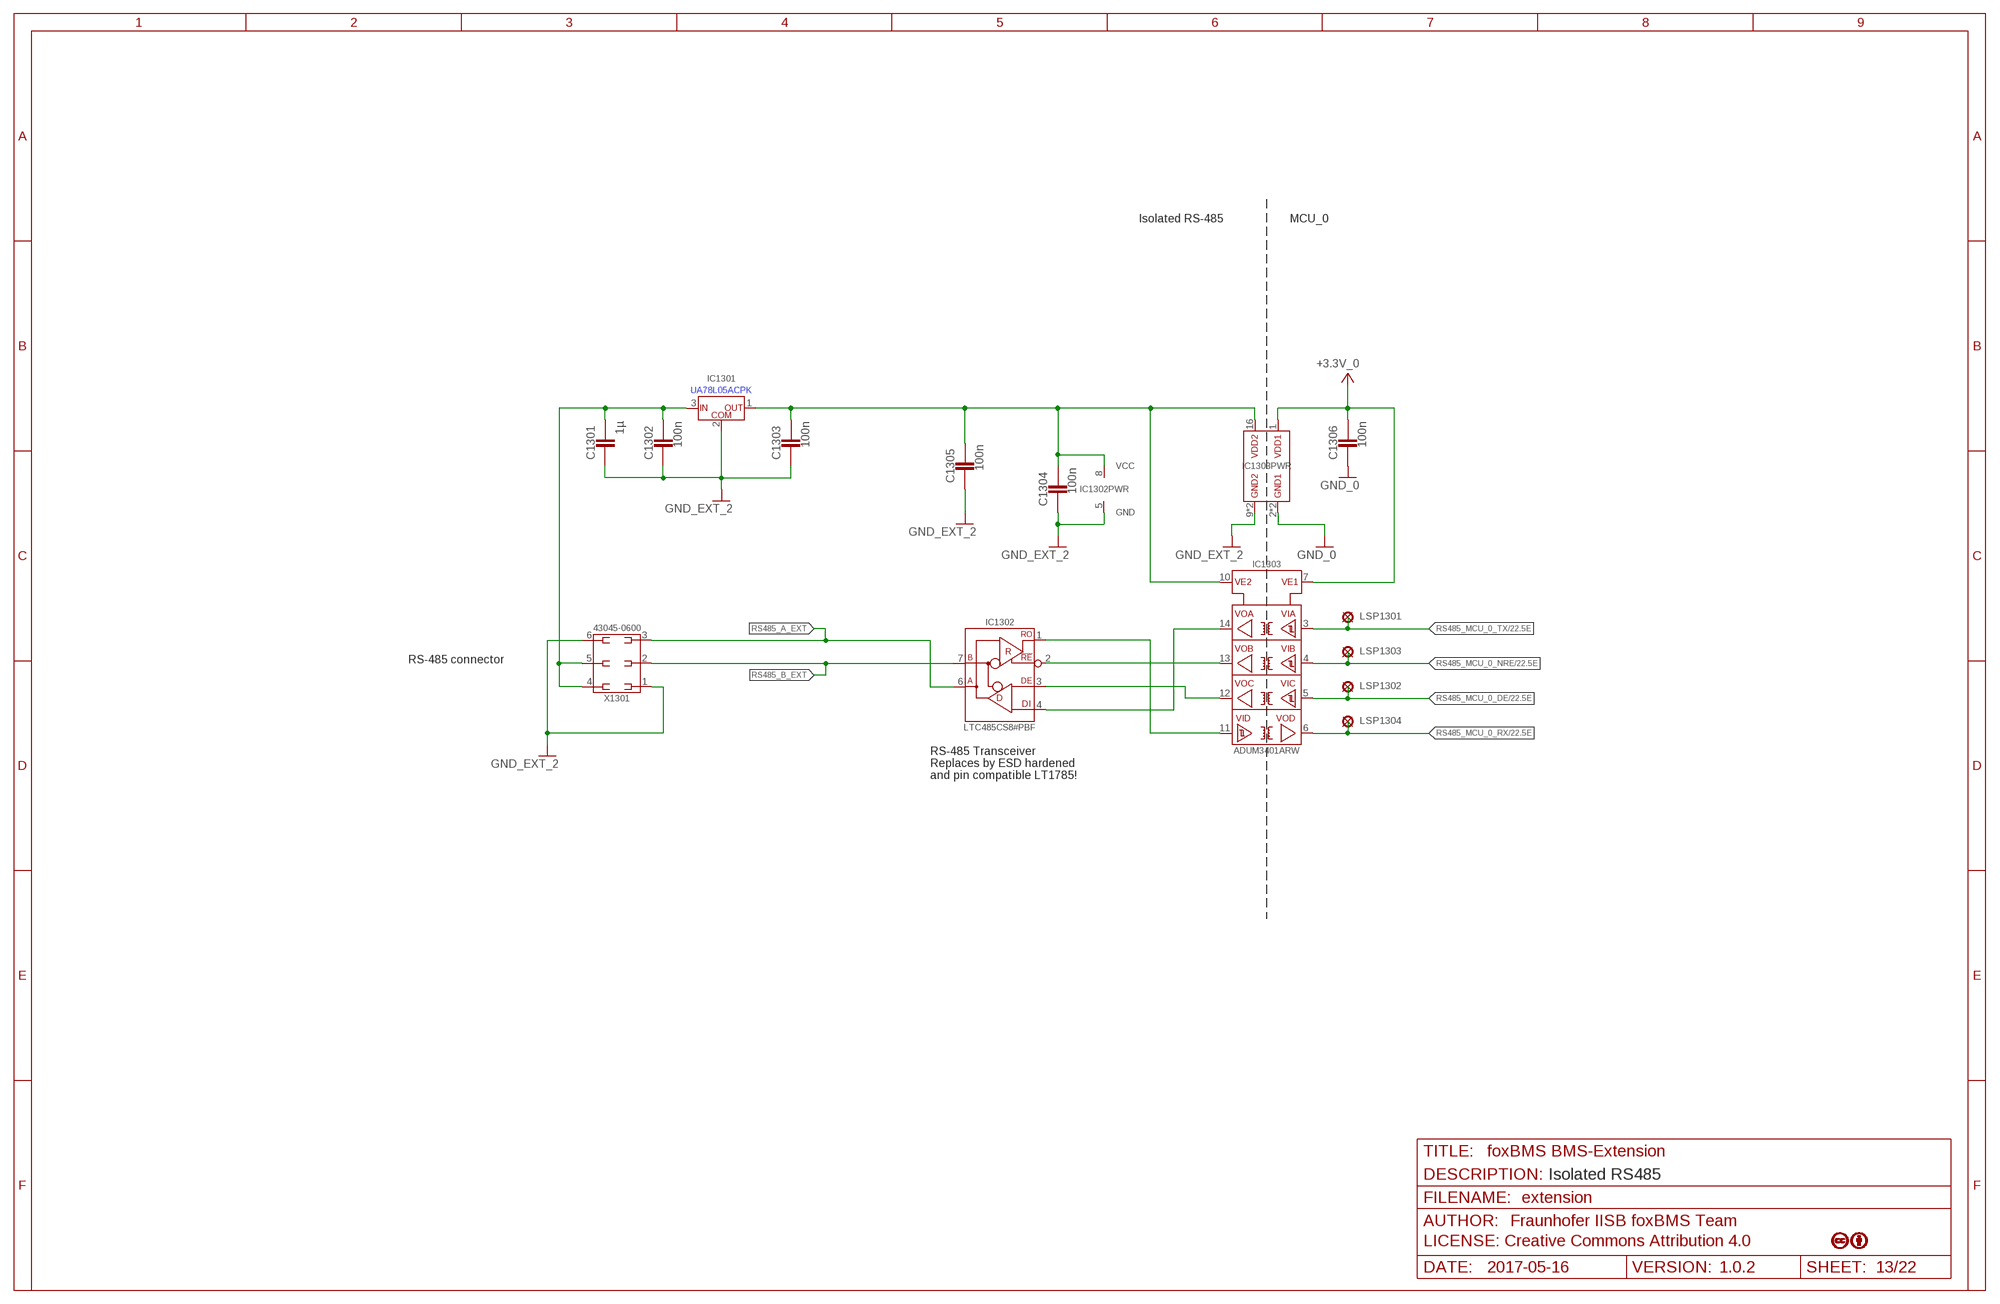
[diagram p12: schematic, sheet 13]
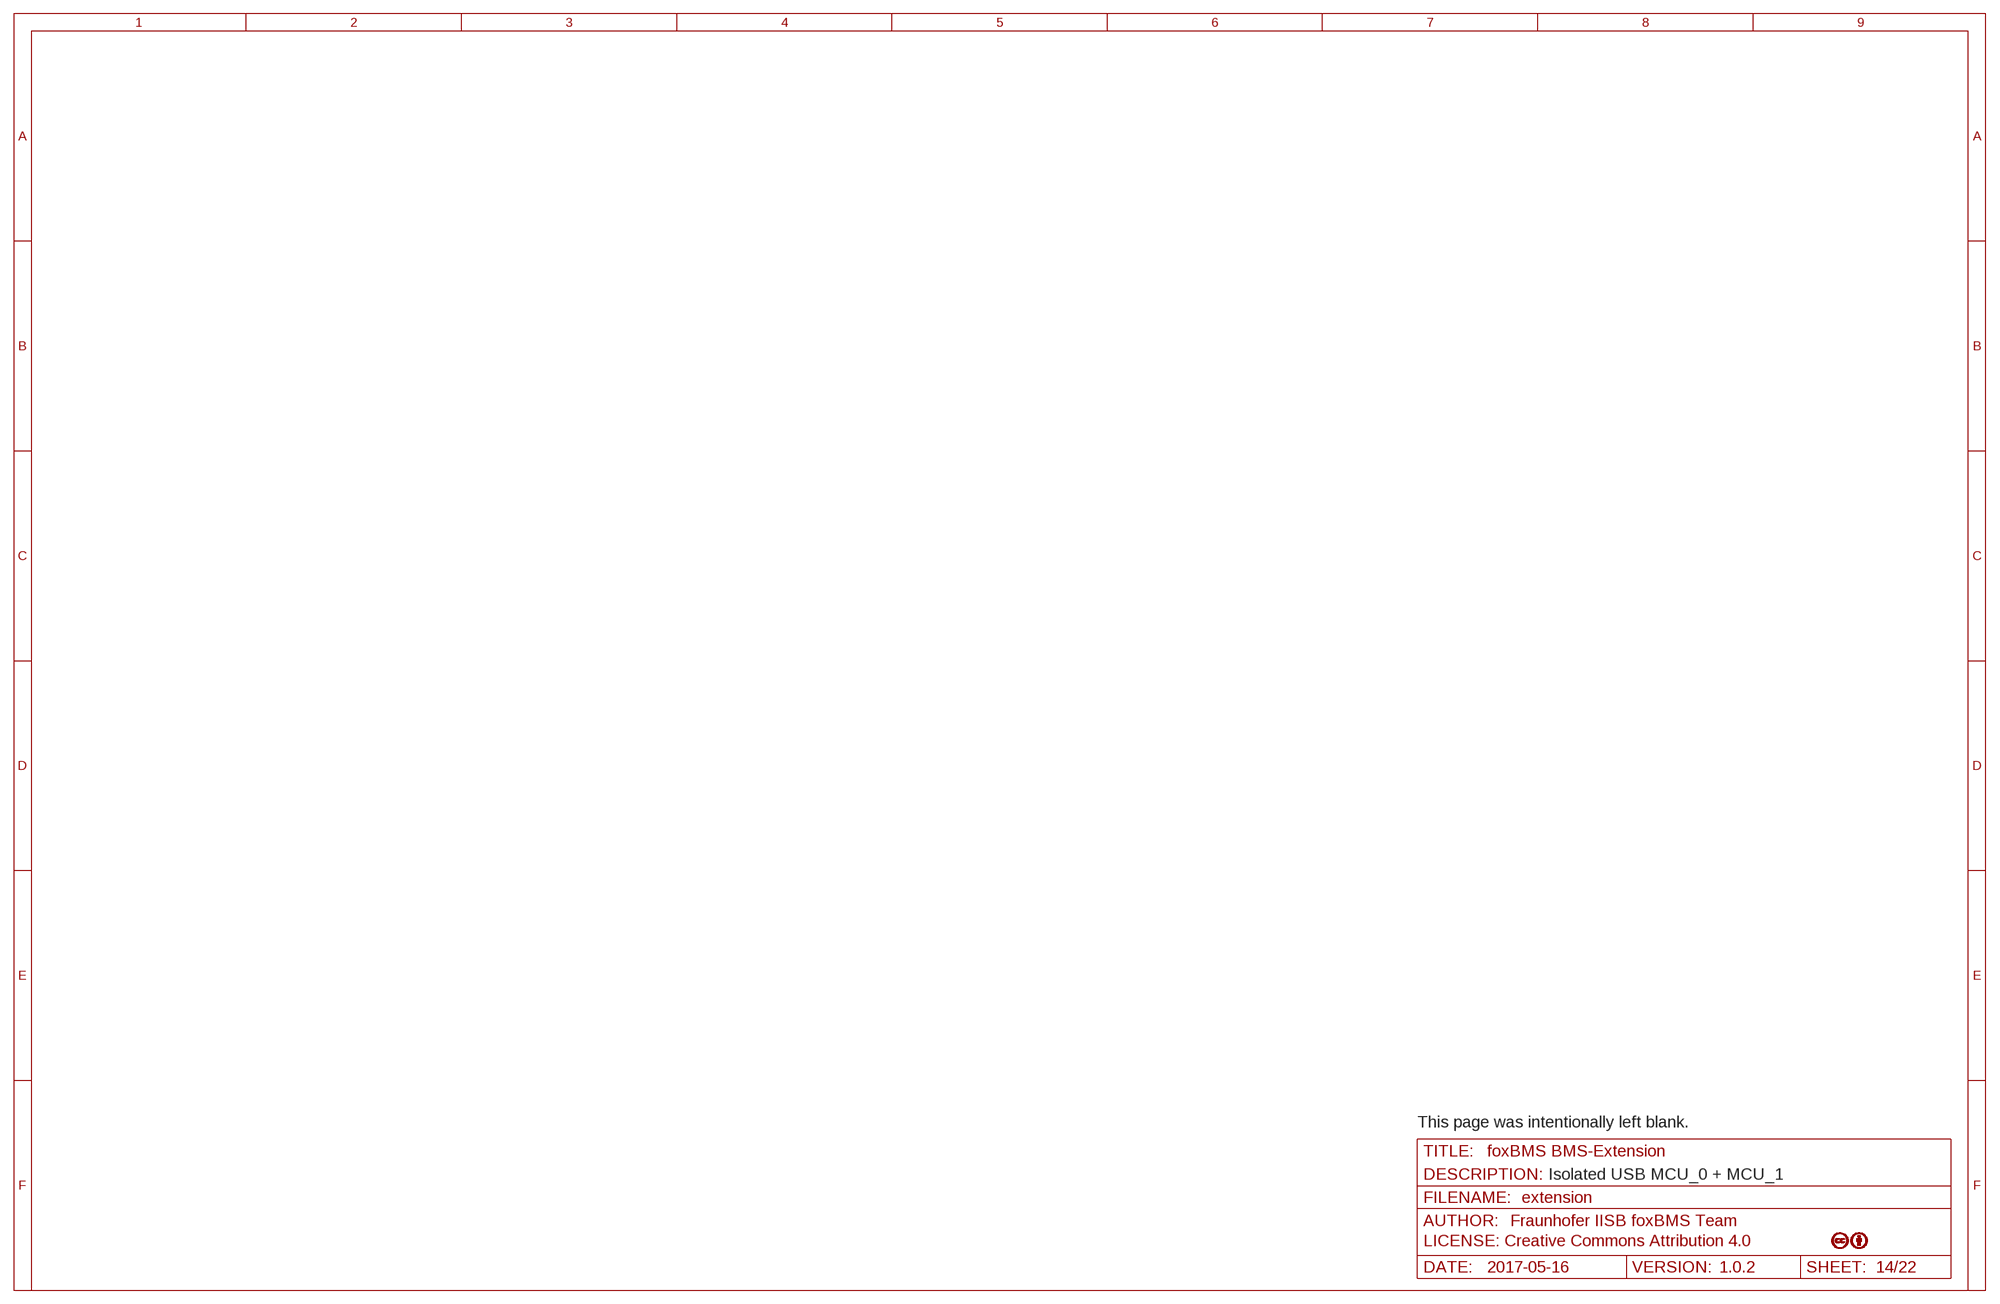
[diagram p13: schematic, sheet 14]
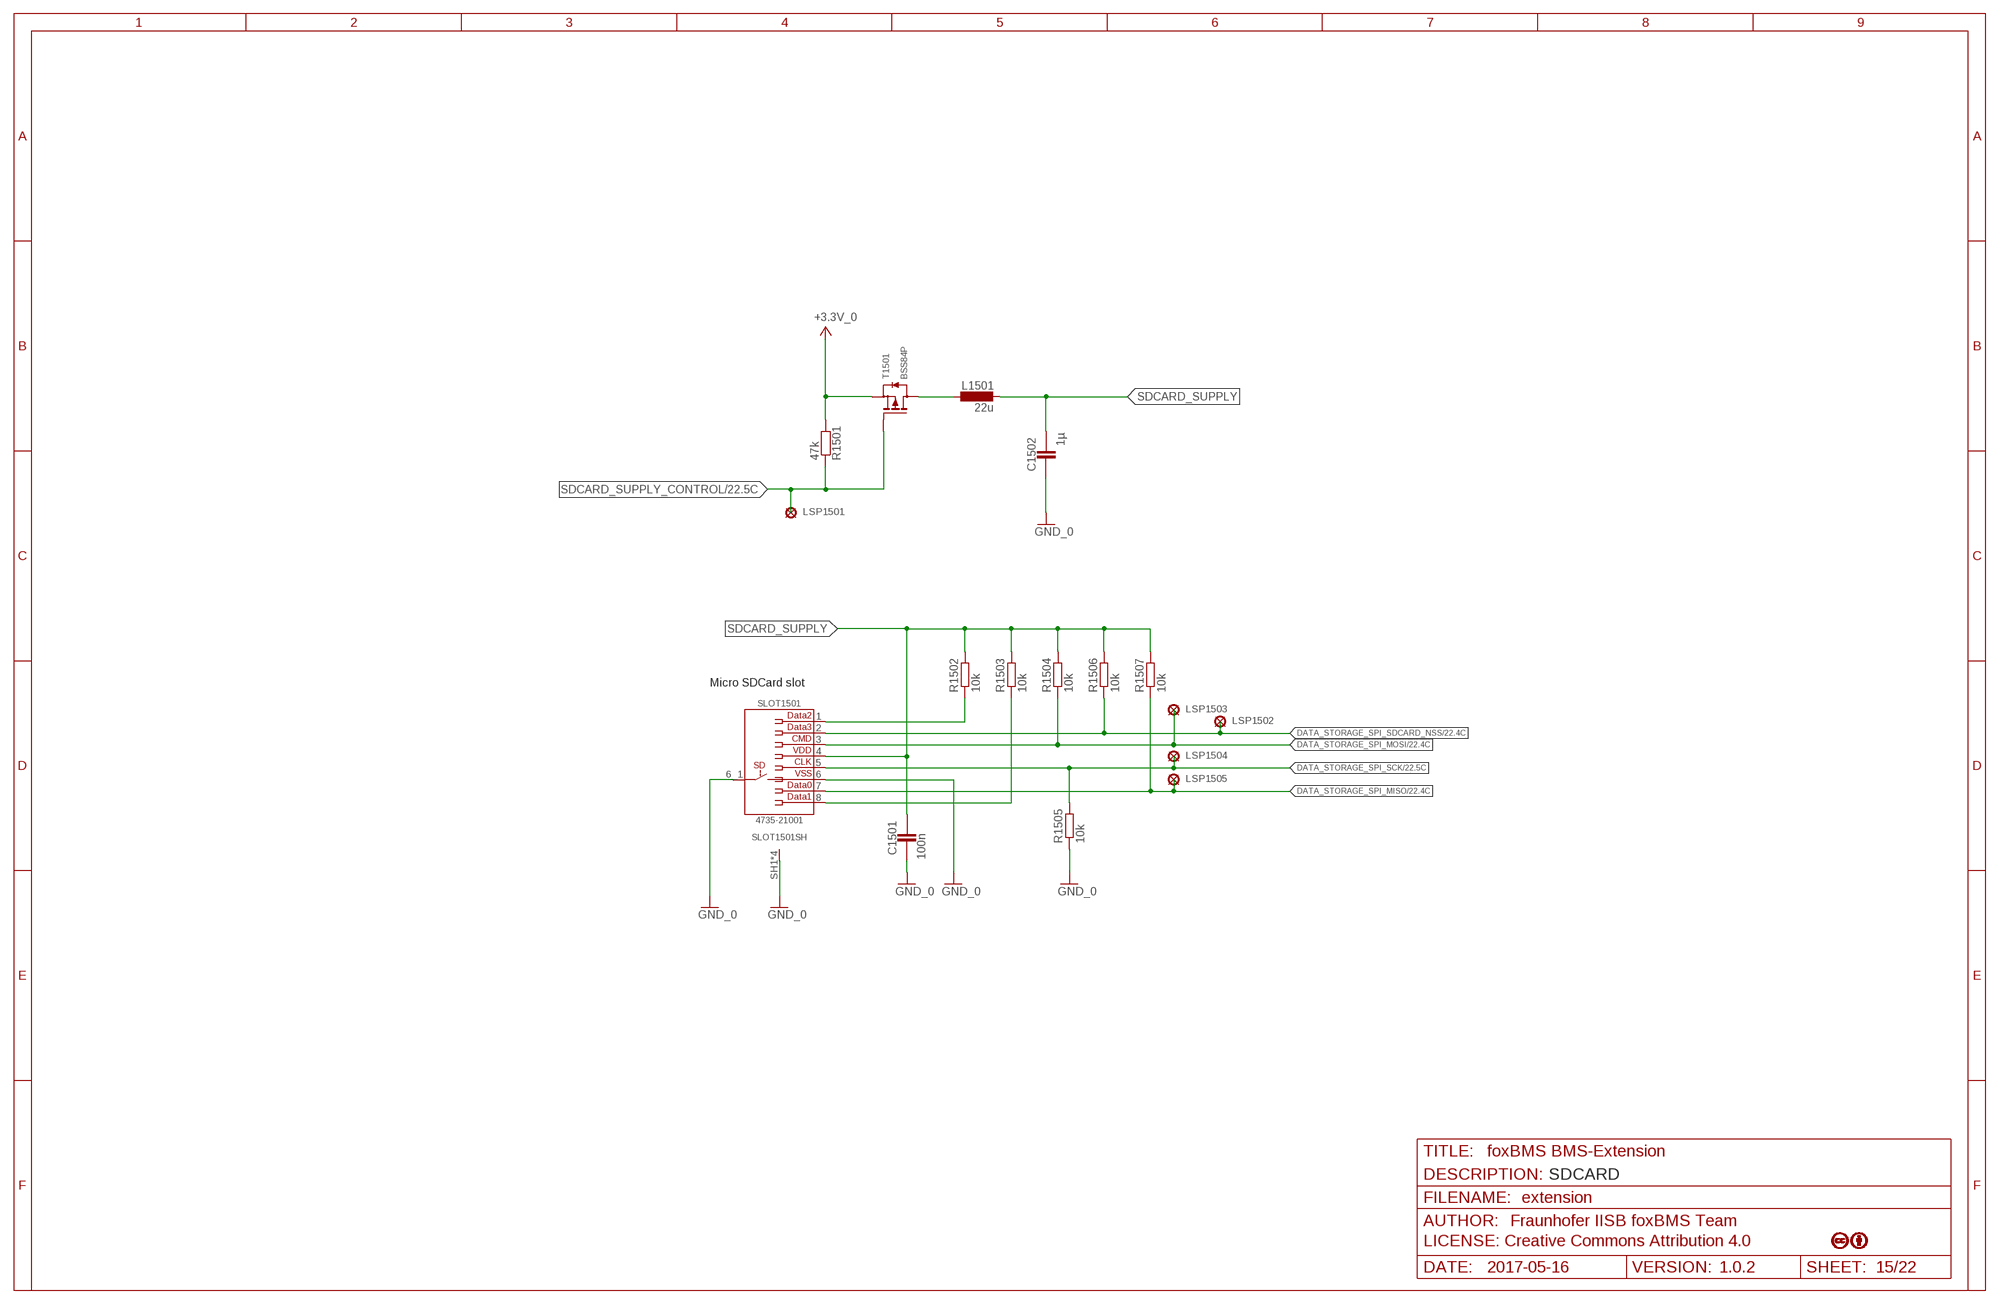
[diagram p14: schematic, sheet 15]
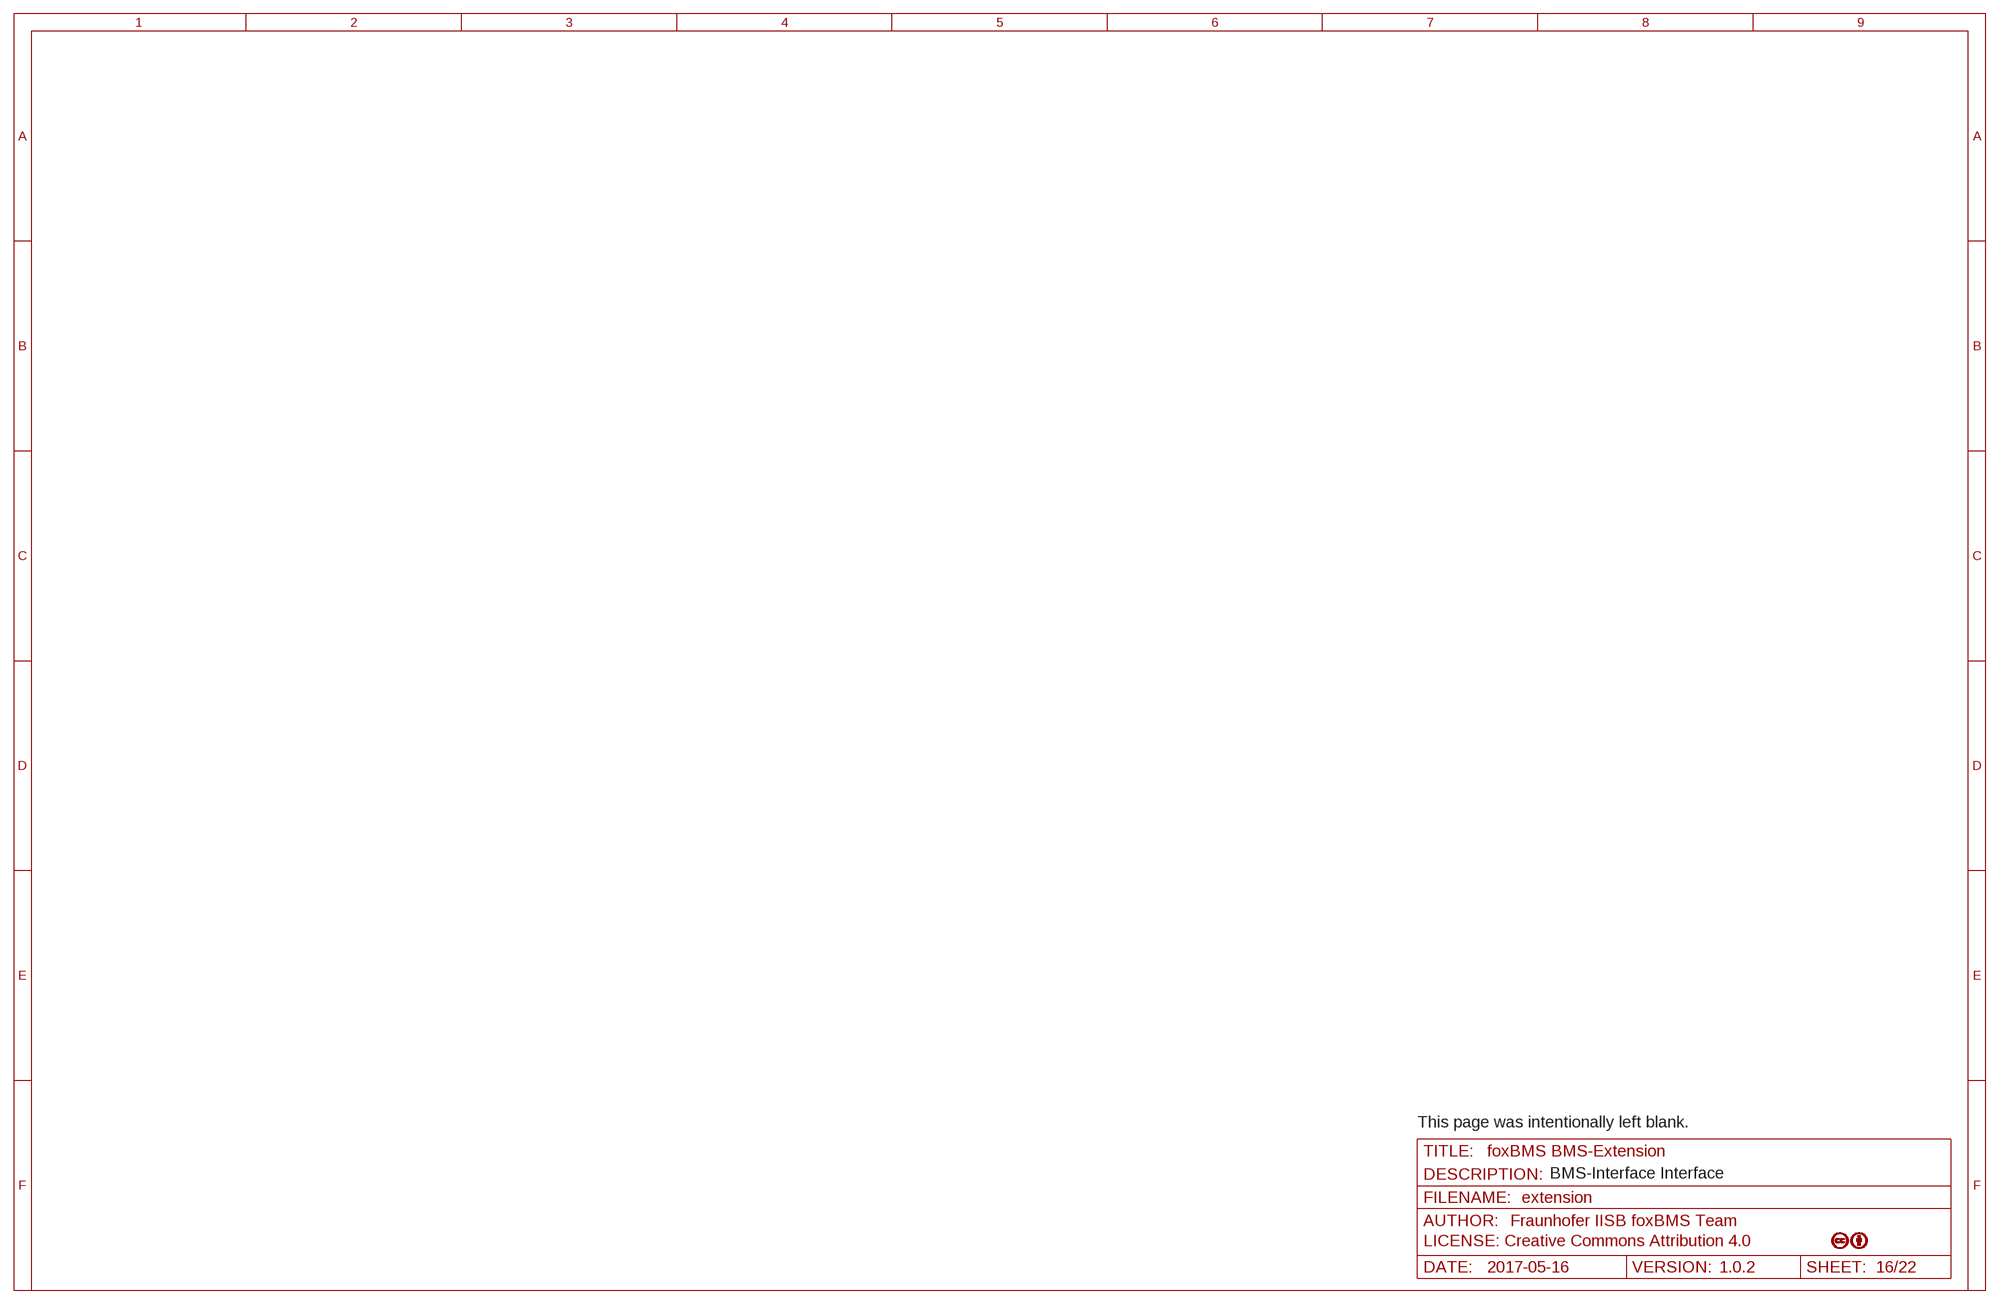
[diagram p15: schematic, sheet 16]
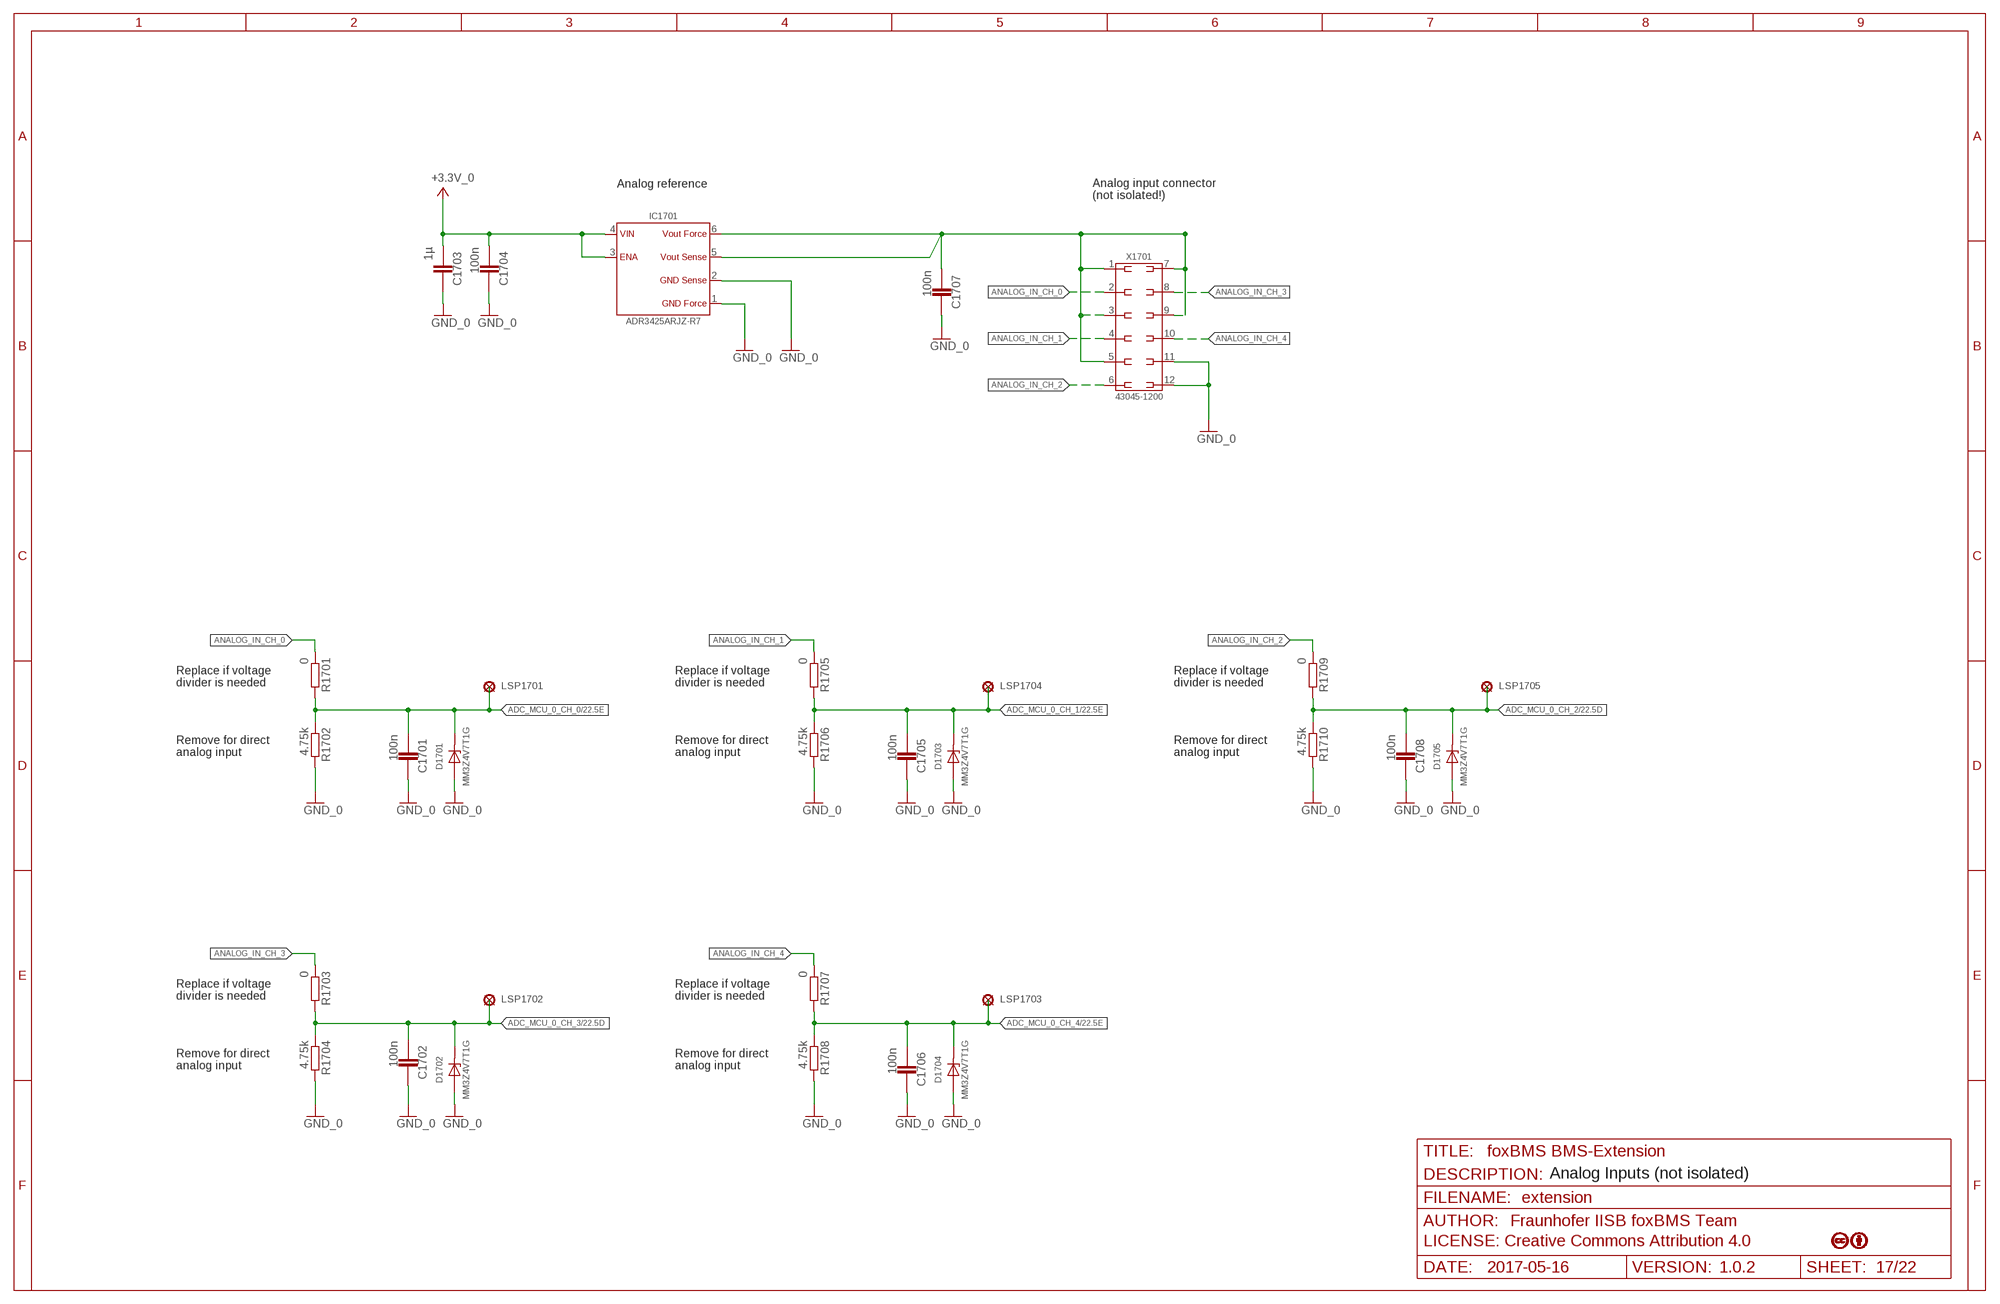
[diagram p16: schematic, sheet 17]
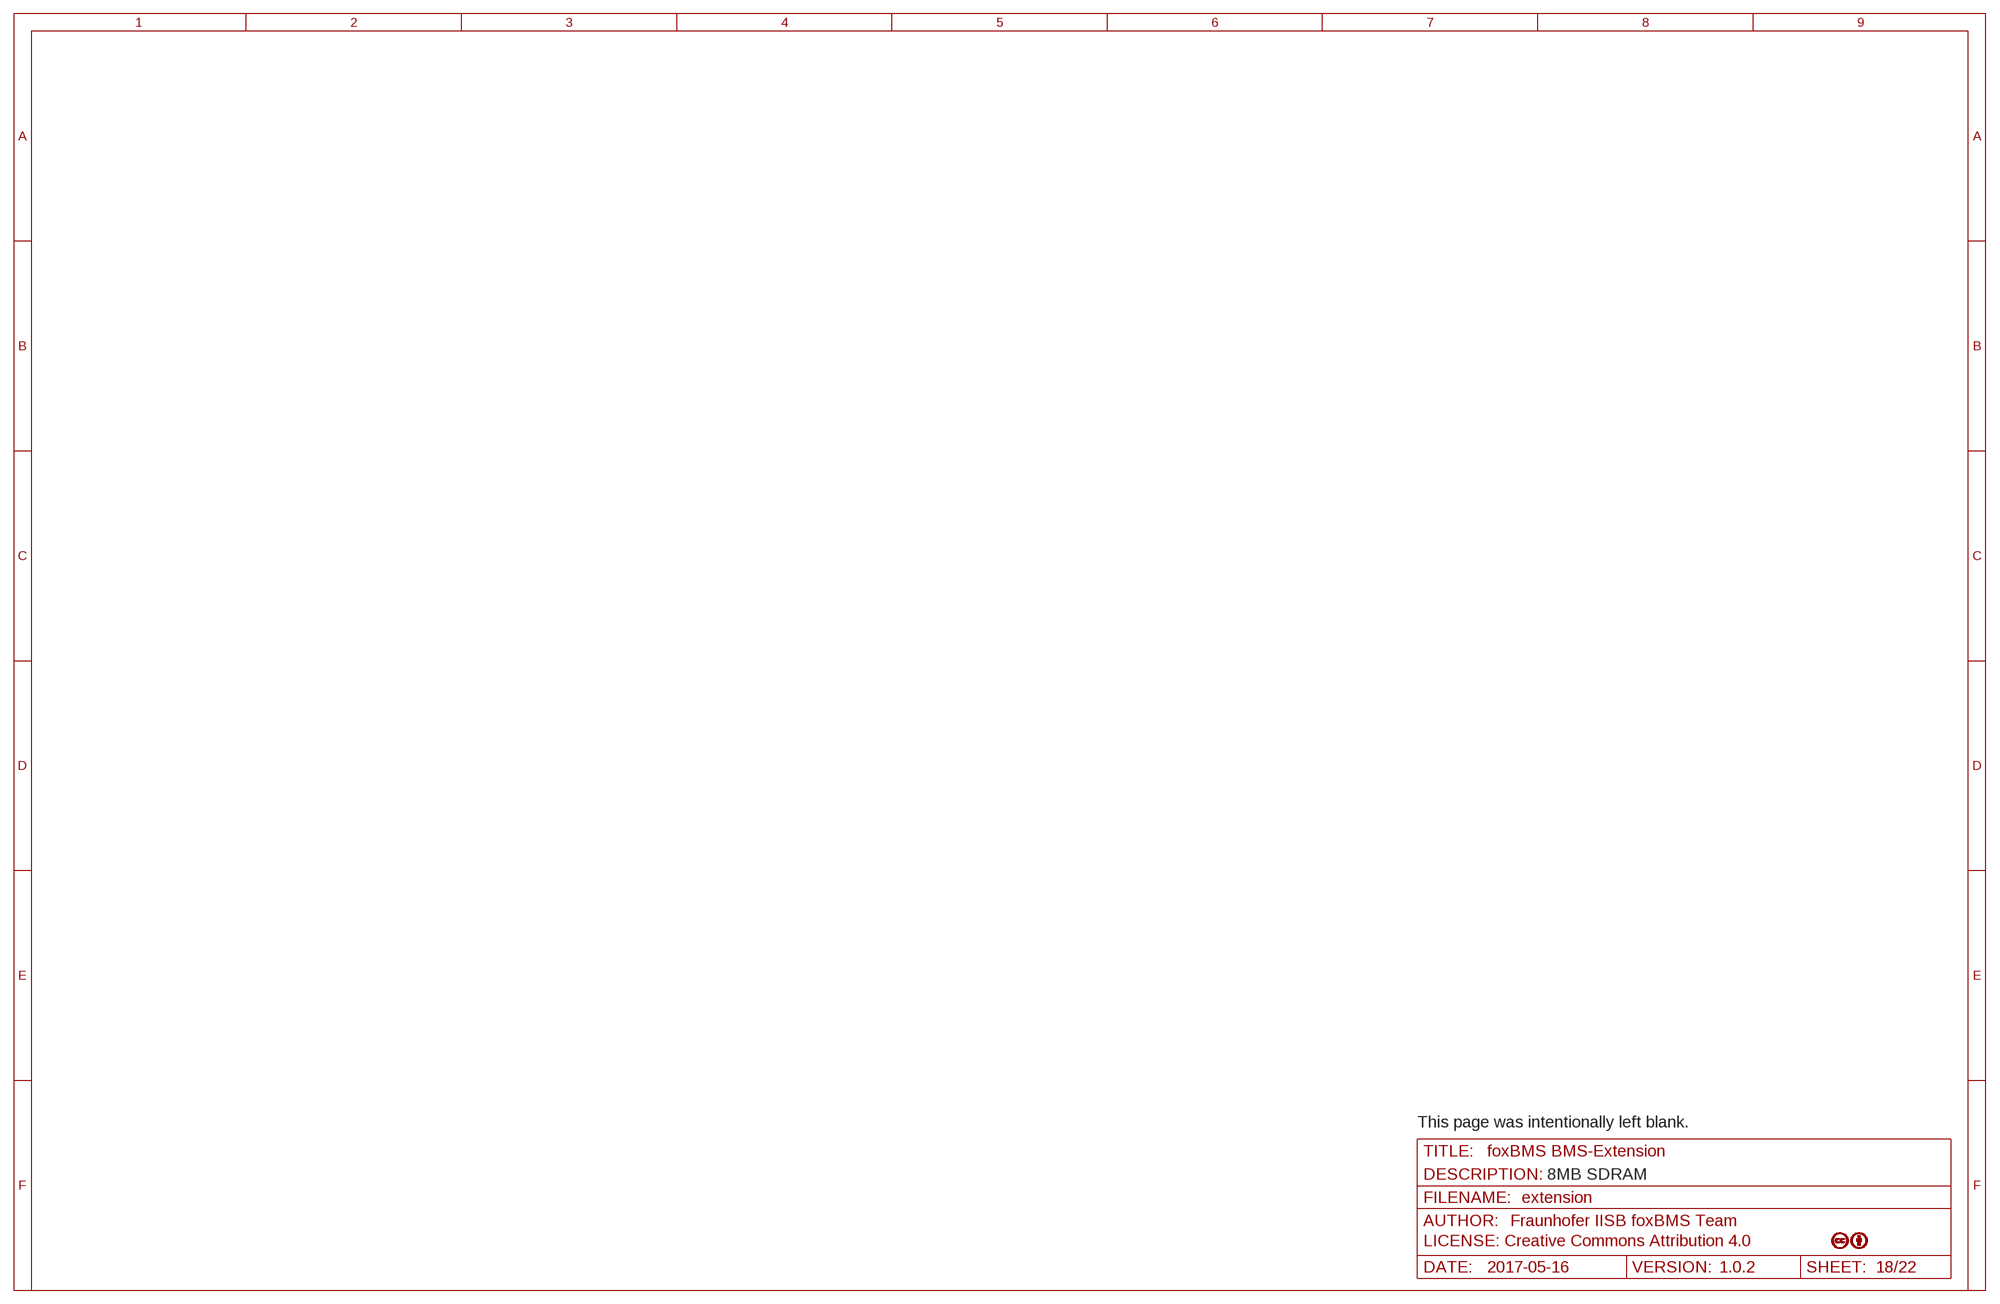
[diagram p17: schematic, sheet 18]
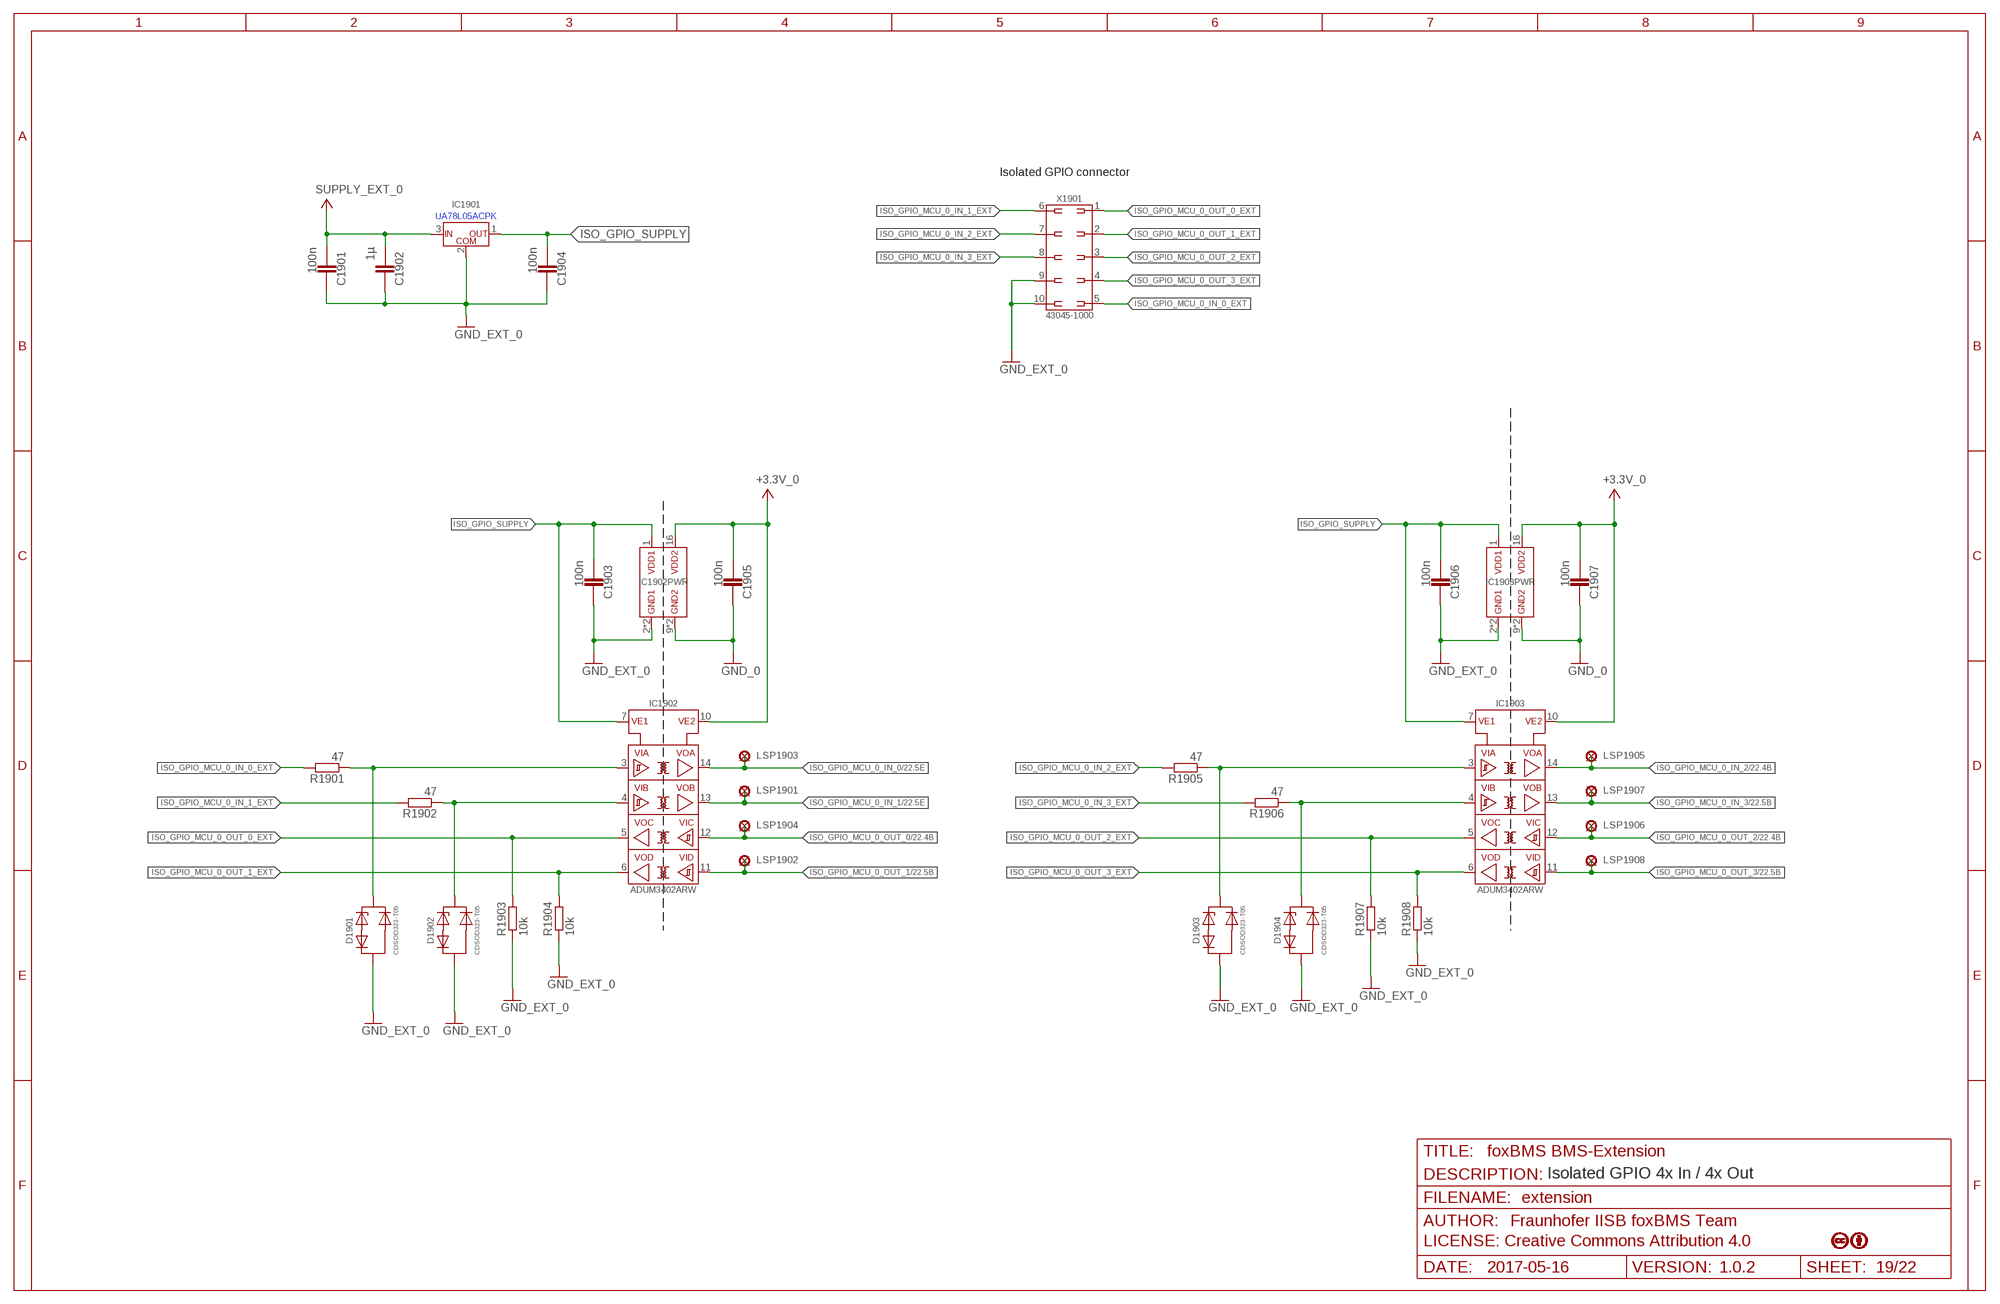
[diagram p18: schematic, sheet 19]
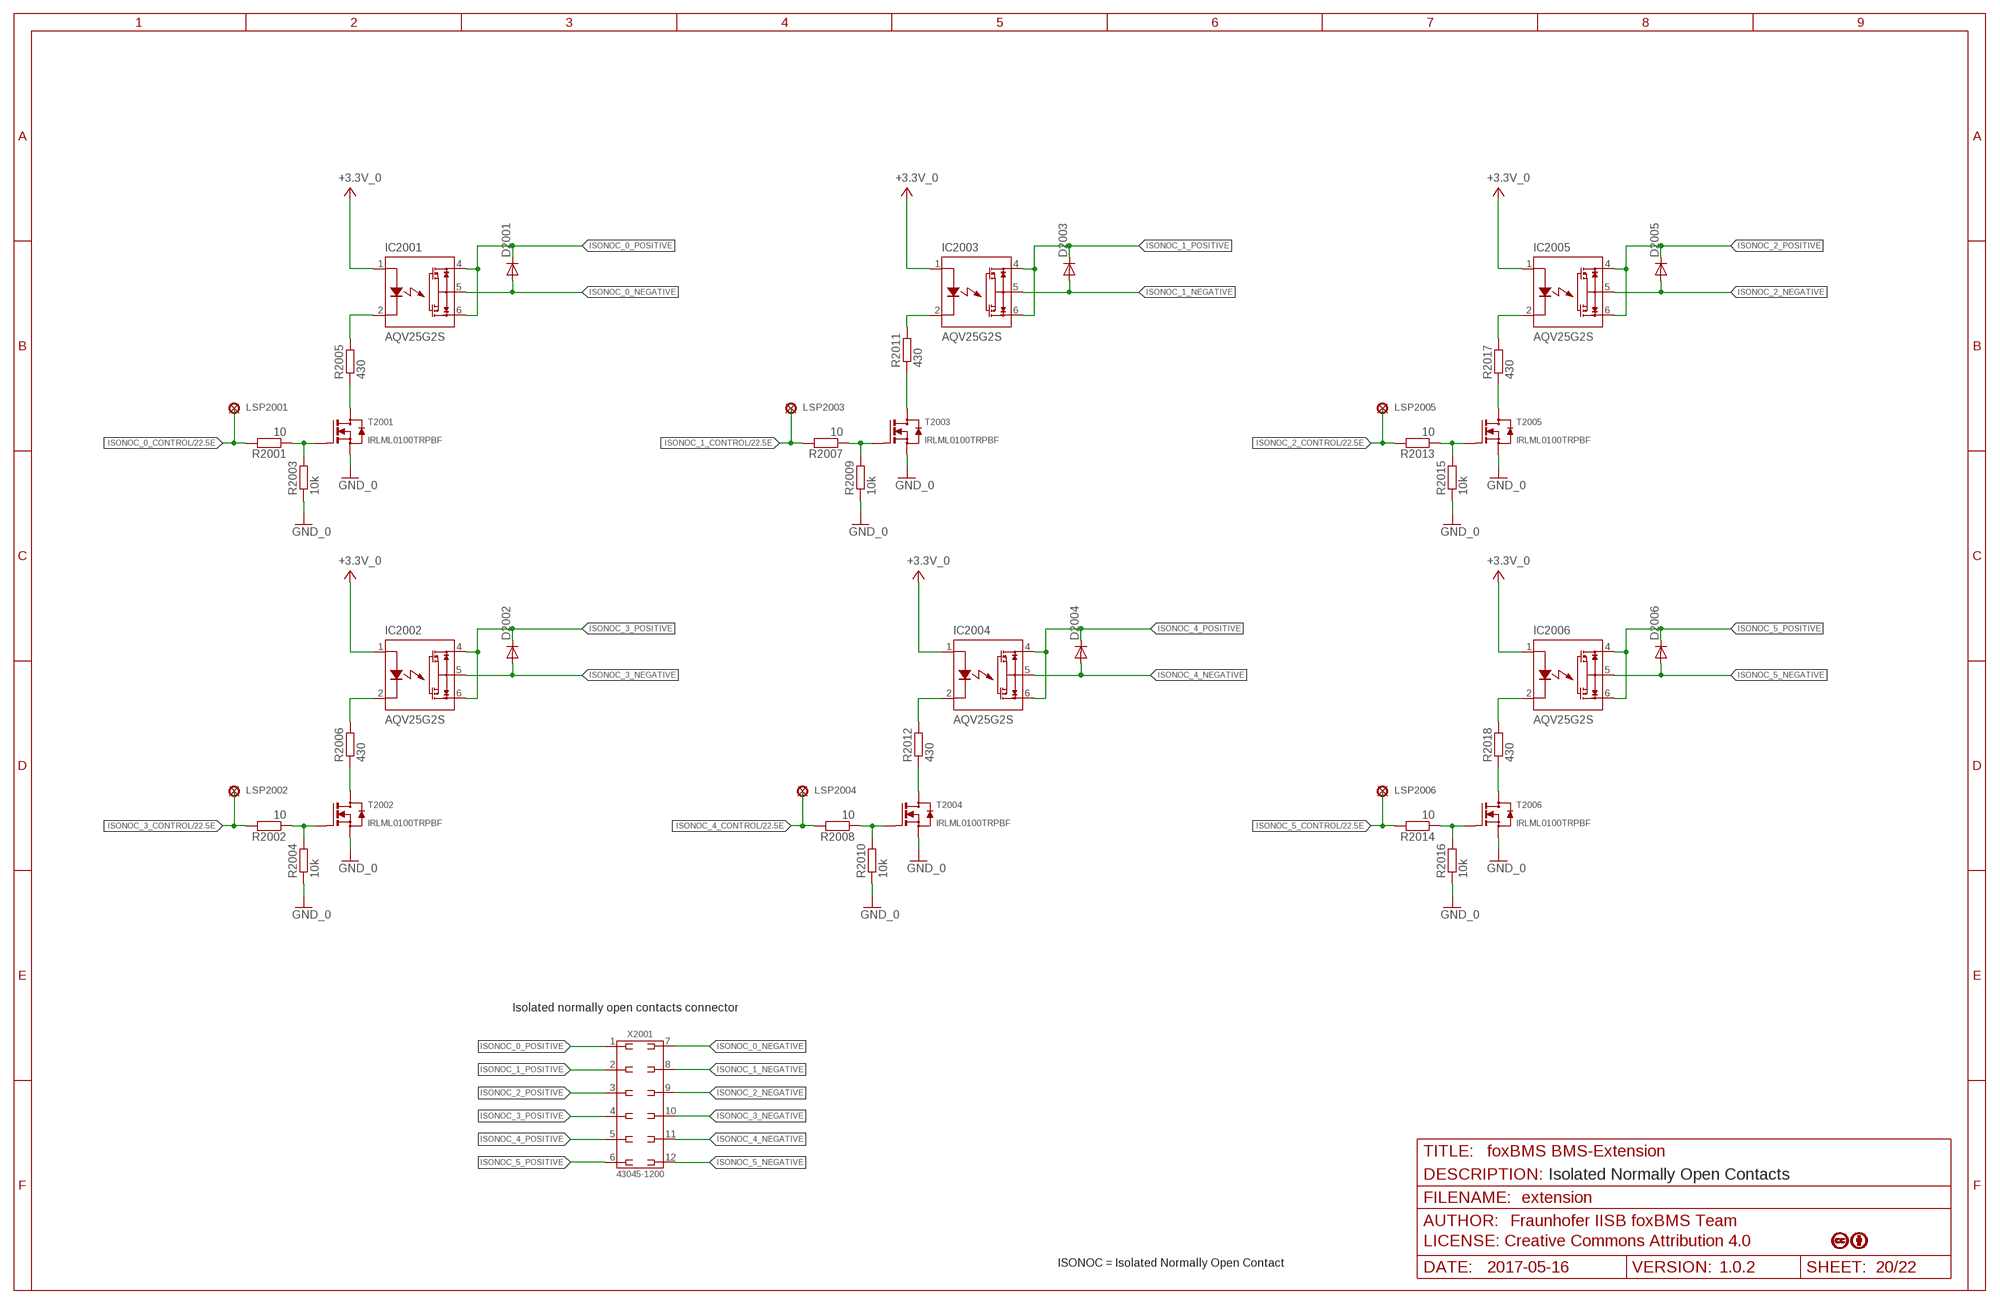
[diagram p19: schematic, sheet 20]
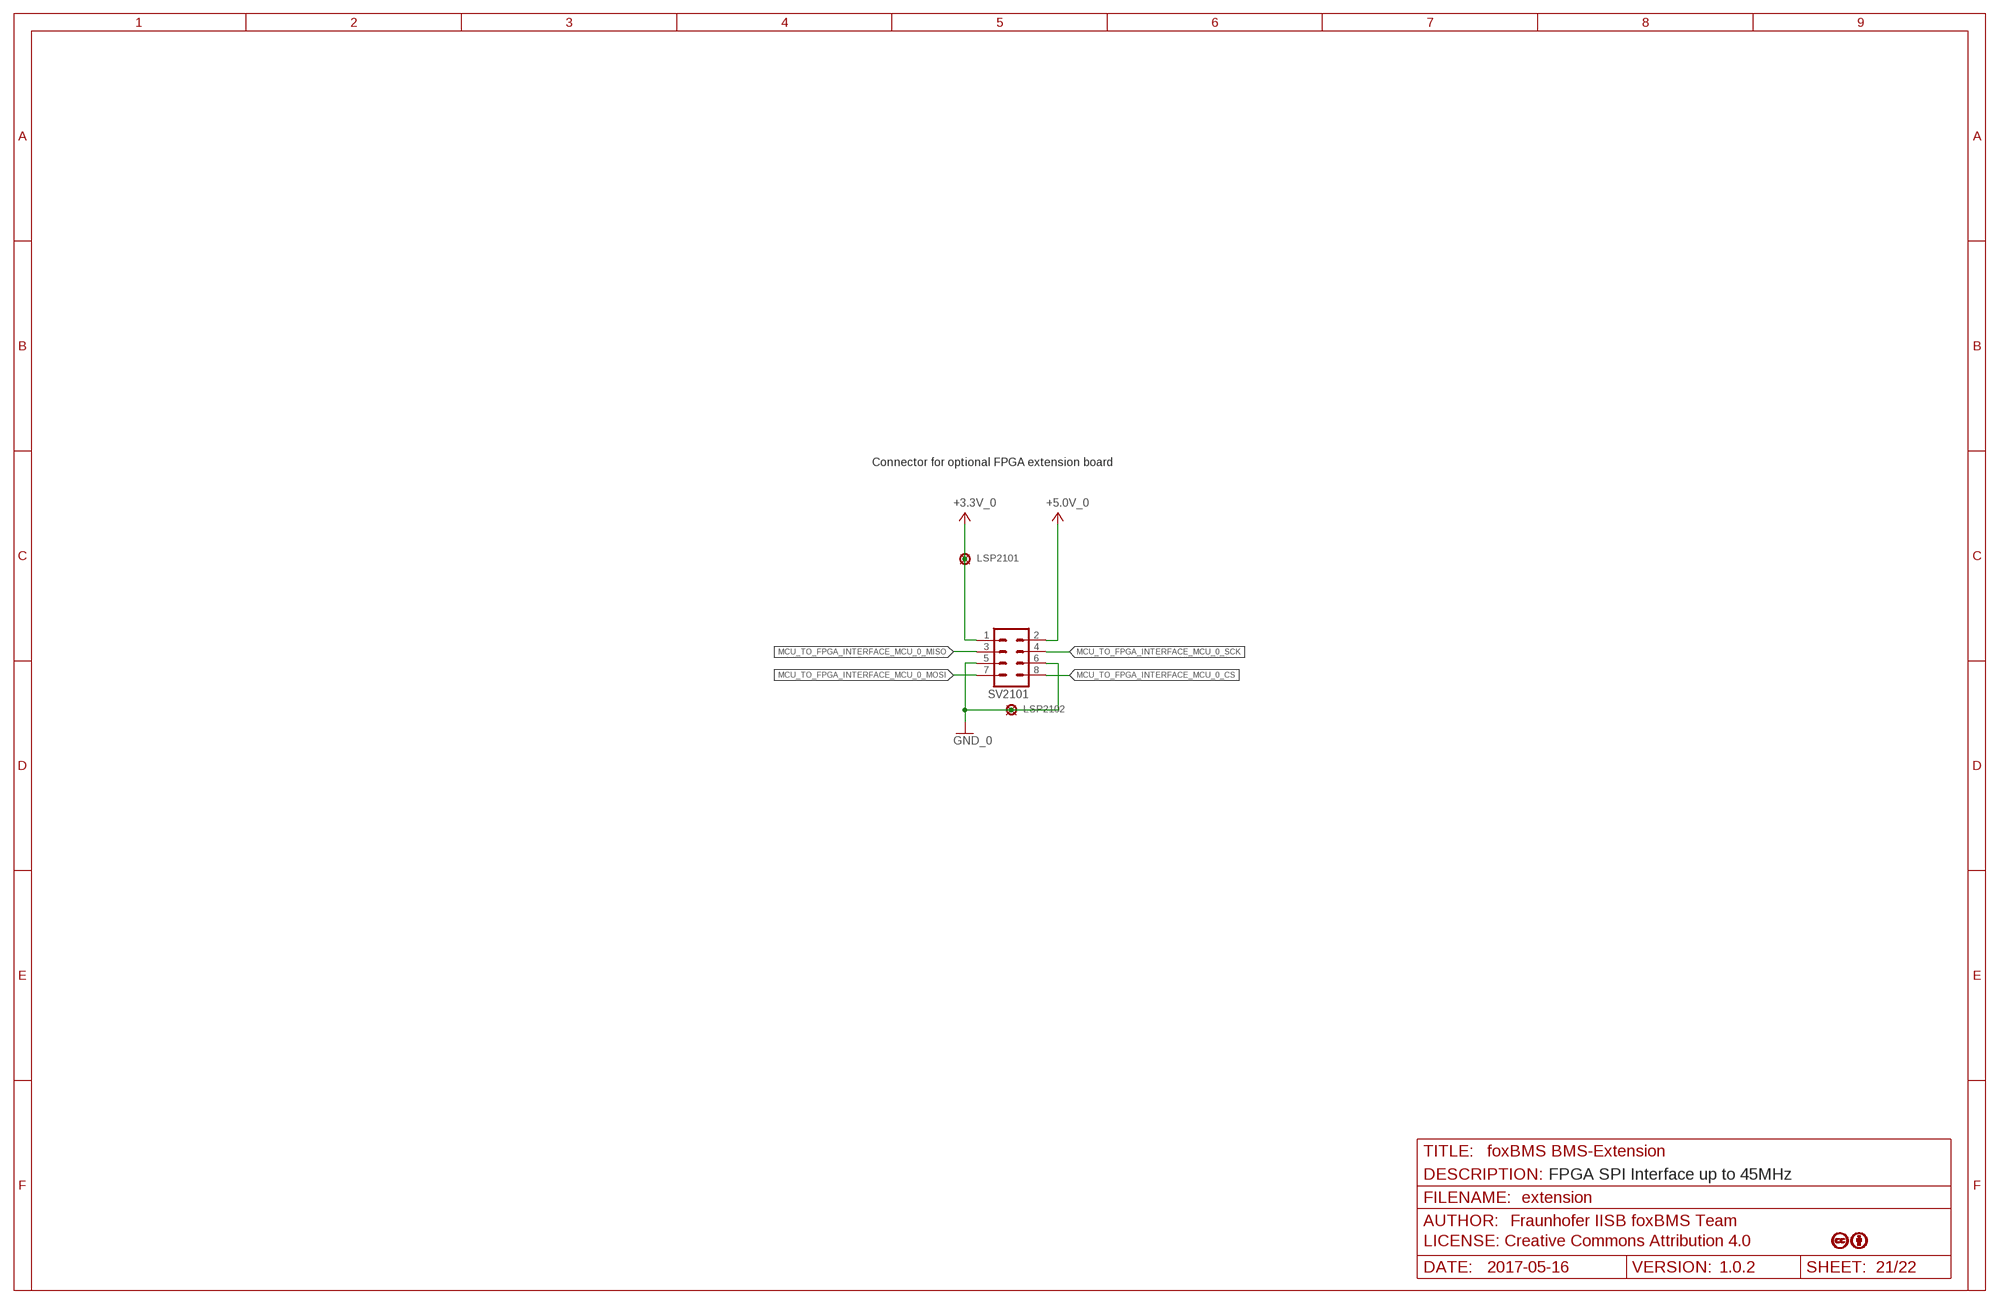
[diagram p20: schematic, sheet 21]
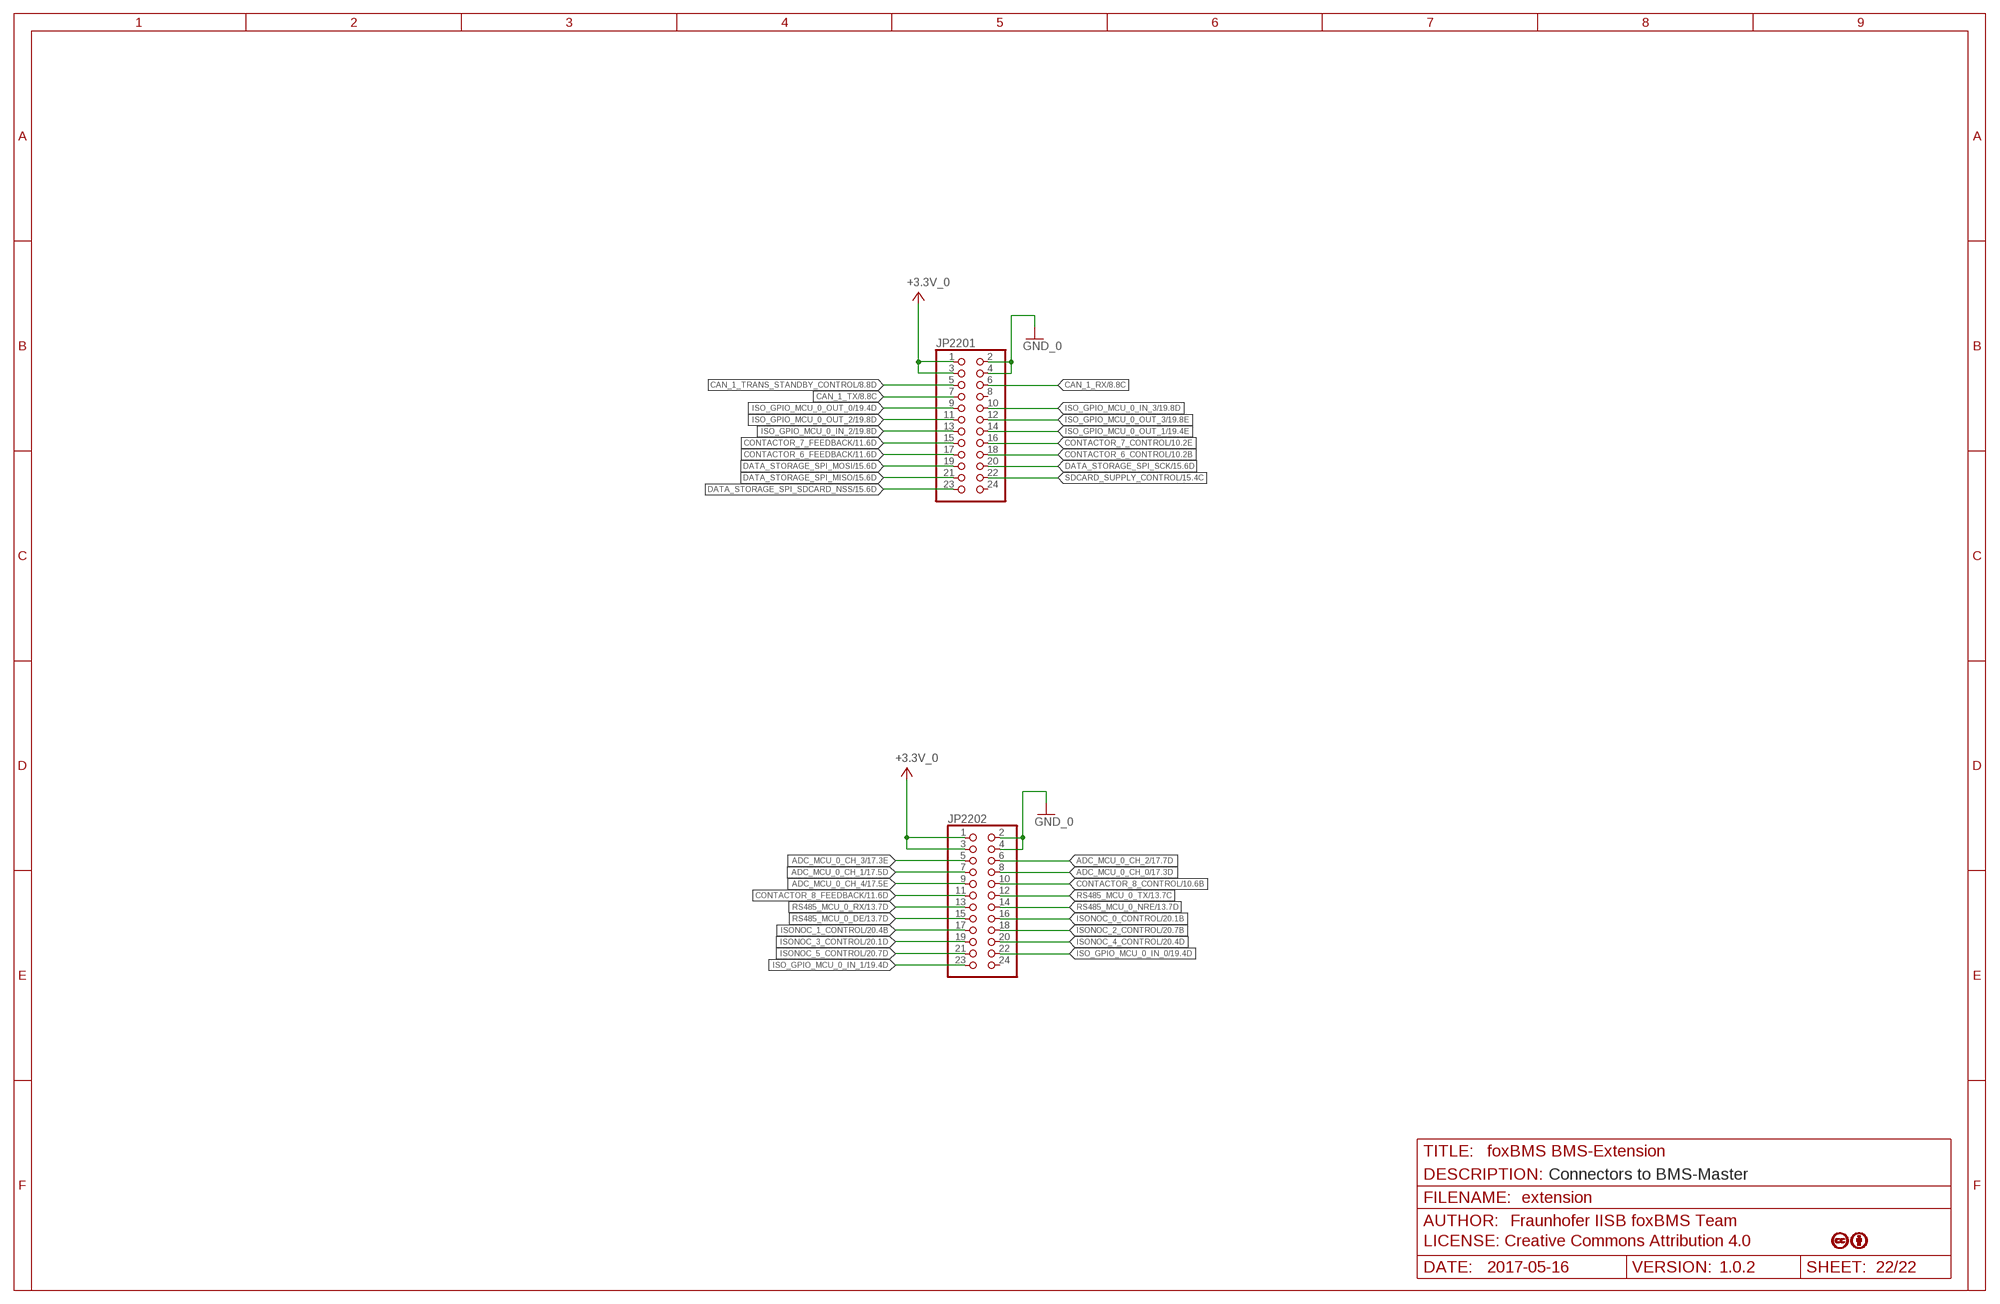
[diagram p21: schematic, sheet 22]

(export (version "E")
  (design (tool "Eeschema 10.0.6"))
  (components
    (comp (ref "C1301")
      (value "1µ")
      (footprint "eagle-import:0603")
      (libsource (lib "eagle-import") (part "C0603_X7R_"))
    )
    (comp (ref "C1302")
      (value "100n")
      (footprint "eagle-import:0603")
      (libsource (lib "eagle-import") (part "C0603_X7R_"))
    )
    (comp (ref "C1303")
      (value "100n")
      (footprint "eagle-import:0603")
      (libsource (lib "eagle-import") (part "C0603_X7R_"))
    )
    (comp (ref "C1304")
      (value "100n")
      (footprint "eagle-import:0603")
      (libsource (lib "eagle-import") (part "C0603_X7R_"))
    )
    (comp (ref "C1305")
      (value "100n")
      (footprint "eagle-import:0603")
      (libsource (lib "eagle-import") (part "C0603_X7R_"))
    )
    (comp (ref "C1306")
      (value "100n")
      (footprint "eagle-import:0603")
      (libsource (lib "eagle-import") (part "C0603_X7R_"))
    )
    (comp (ref "IC1301")
      (value "UA78L05ACPK")
      (footprint "eagle-import:IC_SMD_SOT-89_(SC-62_TO-243)_(R-PSSO-F3)_R_TI_REV01")
      (fields
        (field (name "PDF-LOCAL") "file:///C:\\Eagle-Datasheet\\Spannungsregler\\UA78L00_Texas_Instruments.pdf")
      )
      (libsource (lib "eagle-import") (part "UA78L?PK05AC"))
    )
    (comp (ref "IC1302")
      (value "LTC485CS8#PBF")
      (footprint "eagle-import:IC_SMD_SOIC-8_(S8_REV_G)_R_LINEAR_REV01")
      (fields (field (name "PDF-LOCAL") "file:///C:\\Eagle-Datasheet\\Schnittstellen-IC\\LTC485_Linear.pdf"))
      (libsource (lib "eagle-import") (part "LTC485S8#PBFC"))
    )
    (comp (ref "IC1303")
      (value "ADUM3401ARW")
      (footprint "eagle-import:IC_SMD_SOIC-16_(JEDEC_MS-013-AA)_R_ANALOG_REV01")
      (libsource (lib "eagle-import") (part "ADUM3401ARW"))
    )
    (comp (ref "LSP1301")
      (value "PAD_2.0X1.5MM")
      (footprint "eagle-import:PAD2.0X1.5MM")
      (libsource (lib "eagle-import") (part "PAD_2.0X1.5MM"))
    )
    (comp (ref "LSP1302")
      (value "PAD_2.0X1.5MM")
      (footprint "eagle-import:PAD2.0X1.5MM")
      (libsource (lib "eagle-import") (part "PAD_2.0X1.5MM"))
    )
    (comp (ref "LSP1303")
      (value "PAD_2.0X1.5MM")
      (footprint "eagle-import:PAD2.0X1.5MM")
      (libsource (lib "eagle-import") (part "PAD_2.0X1.5MM"))
    )
    (comp (ref "LSP1304")
      (value "PAD_2.0X1.5MM")
      (footprint "eagle-import:PAD2.0X1.5MM")
      (libsource (lib "eagle-import") (part "PAD_2.0X1.5MM"))
    )
    (comp (ref "X1301")
      (value "43045-0600_MOLEX_6PIN")
      (footprint "eagle-import:X_TH_MOLEX_43045-0600_R_REV01")
      (fields (field (name "PDF-LOCAL") "file:///C:\\Eagle-Datasheet\\Steckverbindung\\430450600_Molex.pdf"))
      (libsource (lib "eagle-import") (part "43045-06?_MOLEX_6PIN00"))
    )
    (comp (ref "C1501")
      (value "100n")
      (footprint "eagle-import:0603")
      (libsource (lib "eagle-import") (part "C0603_NP0_"))
    )
    (comp (ref "C1502")
      (value "1µ")
      (footprint "eagle-import:0603")
      (libsource (lib "eagle-import") (part "C0603_NP0_"))
    )
    (comp (ref "L1501")
      (value "22u")
      (footprint "eagle-import:0805")
      (libsource (lib "eagle-import") (part "L0805"))
    )
    (comp (ref "LSP1501")
      (value "PAD_2.0X1.5MM")
      (footprint "eagle-import:PAD2.0X1.5MM")
      (libsource (lib "eagle-import") (part "PAD_2.0X1.5MM"))
    )
    (comp (ref "LSP1502")
      (value "PAD_2.0X1.5MM")
      (footprint "eagle-import:PAD2.0X1.5MM")
      (libsource (lib "eagle-import") (part "PAD_2.0X1.5MM"))
    )
    (comp (ref "LSP1503")
      (value "PAD_2.0X1.5MM")
      (footprint "eagle-import:PAD2.0X1.5MM")
      (libsource (lib "eagle-import") (part "PAD_2.0X1.5MM"))
    )
    (comp (ref "LSP1504")
      (value "PAD_2.0X1.5MM")
      (footprint "eagle-import:PAD2.0X1.5MM")
      (libsource (lib "eagle-import") (part "PAD_2.0X1.5MM"))
    )
    (comp (ref "LSP1505")
      (value "PAD_2.0X1.5MM")
      (footprint "eagle-import:PAD2.0X1.5MM")
      (libsource (lib "eagle-import") (part "PAD_2.0X1.5MM"))
    )
    (comp (ref "R1501")
      (value "47k")
      (footprint "eagle-import:0603")
      (libsource (lib "eagle-import") (part "R0603_MET_"))
    )
    (comp (ref "R1502")
      (value "10k")
      (footprint "eagle-import:0603")
      (libsource (lib "eagle-import") (part "R0603_MET_"))
    )
    (comp (ref "R1503")
      (value "10k")
      (footprint "eagle-import:0603")
      (libsource (lib "eagle-import") (part "R0603_MET_"))
    )
    (comp (ref "R1504")
      (value "10k")
      (footprint "eagle-import:0603")
      (libsource (lib "eagle-import") (part "R0603_MET_"))
    )
    (comp (ref "R1505")
      (value "10k")
      (footprint "eagle-import:0603")
      (libsource (lib "eagle-import") (part "R0603_MET_"))
    )
    (comp (ref "R1506")
      (value "10k")
      (footprint "eagle-import:0603")
      (libsource (lib "eagle-import") (part "R0603_MET_"))
    )
    (comp (ref "R1507")
      (value "10k")
      (footprint "eagle-import:0603")
      (libsource (lib "eagle-import") (part "R0603_MET_"))
    )
    (comp (ref "SLOT1501")
      (value "MICRO_SD")
      (footprint "eagle-import:X_SMD_MICRO-SD-4735-21001_R_MOLEX_REV01")
      (fields
        (field (name "PDF-LOCAL") "file:///C:\\Eagle-Datasheet\\Steckverbindung\\473521001_SD_Molex.pdf")
      )
      (libsource (lib "eagle-import") (part "MICRO_SD"))
    )
    (comp (ref "T1501")
      (value "BSS84P")
      (footprint "eagle-import:V_SMD_SOT23_(TO-236AB)_R_INFINEON_REV01")
      (fields (field (name "PDF-LOCAL") "file:///C:\\Eagle-Datasheet\\Transistoren\\BSS84P_Infineon.pdf"))
      (libsource (lib "eagle-import") (part "BSS84P"))
    )
    (comp (ref "LSP2101")
      (value "PAD_2.0X1.5MM")
      (footprint "eagle-import:PAD2.0X1.5MM")
      (libsource (lib "eagle-import") (part "PAD_2.0X1.5MM"))
    )
    (comp (ref "LSP2102")
      (value "PAD_2.0X1.5MM")
      (footprint "eagle-import:PAD2.0X1.5MM")
      (libsource (lib "eagle-import") (part "PAD_2.0X1.5MM"))
    )
    (comp (ref "SV2101")
      (value "MA04-2")
      (footprint "eagle-import:MA04-2")
      (libsource (lib "eagle-import") (part "MA04-2"))
    )
    (comp (ref "JP2201")
      (value "PINHD-2X12")
      (footprint "eagle-import:2X12")
      (libsource (lib "eagle-import") (part "PINHD-2X12"))
    )
    (comp (ref "JP2202")
      (value "PINHD-2X12")
      (footprint "eagle-import:2X12")
      (libsource (lib "eagle-import") (part "PINHD-2X12"))
    )
    (comp (ref "C1901")
      (value "100n")
      (footprint "eagle-import:0603")
      (libsource (lib "eagle-import") (part "C0603_X7R_"))
    )
    (comp (ref "C1902")
      (value "1µ")
      (footprint "eagle-import:0603")
      (libsource (lib "eagle-import") (part "C0603_X7R_"))
    )
    (comp (ref "C1903")
      (value "100n")
      (footprint "eagle-import:0603")
      (libsource (lib "eagle-import") (part "C0603_X7R_"))
    )
    (comp (ref "C1904")
      (value "100n")
      (footprint "eagle-import:0603")
      (libsource (lib "eagle-import") (part "C0603_X7R_"))
    )
    (comp (ref "C1905")
      (value "100n")
      (footprint "eagle-import:0603")
      (libsource (lib "eagle-import") (part "C0603_X7R_"))
    )
    (comp (ref "C1906")
      (value "100n")
      (footprint "eagle-import:0603")
      (libsource (lib "eagle-import") (part "C0603_X7R_"))
    )
    (comp (ref "C1907")
      (value "100n")
      (footprint "eagle-import:0603")
      (libsource (lib "eagle-import") (part "C0603_X7R_"))
    )
    (comp (ref "D1901")
      (value "CDSOD323-T05")
      (footprint "eagle-import:D_SMD_SOD323_(SC-76)_R_BOURNS_REV01")
      (libsource (lib "eagle-import") (part "CDSOD323-T?05"))
    )
    (comp (ref "D1902")
      (value "CDSOD323-T05")
      (footprint "eagle-import:D_SMD_SOD323_(SC-76)_R_BOURNS_REV01")
      (libsource (lib "eagle-import") (part "CDSOD323-T?05"))
    )
    (comp (ref "D1903")
      (value "CDSOD323-T05")
      (footprint "eagle-import:D_SMD_SOD323_(SC-76)_R_BOURNS_REV01")
      (libsource (lib "eagle-import") (part "CDSOD323-T?05"))
    )
    (comp (ref "D1904")
      (value "CDSOD323-T05")
      (footprint "eagle-import:D_SMD_SOD323_(SC-76)_R_BOURNS_REV01")
      (libsource (lib "eagle-import") (part "CDSOD323-T?05"))
    )
    (comp (ref "IC1901")
      (value "UA78L05ACPK")
      (footprint "eagle-import:IC_SMD_SOT-89_(SC-62_TO-243)_(R-PSSO-F3)_R_TI_REV01")
      (fields
        (field (name "PDF-LOCAL") "file:///C:\\Eagle-Datasheet\\Spannungsregler\\UA78L00_Texas_Instruments.pdf")
      )
      (libsource (lib "eagle-import") (part "UA78L?PK05AC"))
    )
    (comp (ref "IC1902")
      (value "ADUM3402ARW")
      (footprint "eagle-import:IC_SMD_SOIC-16_(JEDEC_MS-013-AA)_R_ANALOG_REV01")
      (libsource (lib "eagle-import") (part "ADUM3402ARW"))
    )
    (comp (ref "IC1903")
      (value "ADUM3402ARW")
      (footprint "eagle-import:IC_SMD_SOIC-16_(JEDEC_MS-013-AA)_R_ANALOG_REV01")
      (libsource (lib "eagle-import") (part "ADUM3402ARW"))
    )
    (comp (ref "LSP1901")
      (value "PAD_2.0X1.5MM")
      (footprint "eagle-import:PAD2.0X1.5MM")
      (libsource (lib "eagle-import") (part "PAD_2.0X1.5MM"))
    )
    (comp (ref "LSP1902")
      (value "PAD_2.0X1.5MM")
      (footprint "eagle-import:PAD2.0X1.5MM")
      (libsource (lib "eagle-import") (part "PAD_2.0X1.5MM"))
    )
    (comp (ref "LSP1903")
      (value "PAD_2.0X1.5MM")
      (footprint "eagle-import:PAD2.0X1.5MM")
      (libsource (lib "eagle-import") (part "PAD_2.0X1.5MM"))
    )
    (comp (ref "LSP1904")
      (value "PAD_2.0X1.5MM")
      (footprint "eagle-import:PAD2.0X1.5MM")
      (libsource (lib "eagle-import") (part "PAD_2.0X1.5MM"))
    )
    (comp (ref "LSP1905")
      (value "PAD_2.0X1.5MM")
      (footprint "eagle-import:PAD2.0X1.5MM")
      (libsource (lib "eagle-import") (part "PAD_2.0X1.5MM"))
    )
    (comp (ref "LSP1906")
      (value "PAD_2.0X1.5MM")
      (footprint "eagle-import:PAD2.0X1.5MM")
      (libsource (lib "eagle-import") (part "PAD_2.0X1.5MM"))
    )
    (comp (ref "LSP1907")
      (value "PAD_2.0X1.5MM")
      (footprint "eagle-import:PAD2.0X1.5MM")
      (libsource (lib "eagle-import") (part "PAD_2.0X1.5MM"))
    )
    (comp (ref "LSP1908")
      (value "PAD_2.0X1.5MM")
      (footprint "eagle-import:PAD2.0X1.5MM")
      (libsource (lib "eagle-import") (part "PAD_2.0X1.5MM"))
    )
    (comp (ref "R1901")
      (value "47")
      (footprint "eagle-import:0603")
      (libsource (lib "eagle-import") (part "R0603_MET_"))
    )
    (comp (ref "R1902")
      (value "47")
      (footprint "eagle-import:0603")
      (libsource (lib "eagle-import") (part "R0603_MET_"))
    )
    (comp (ref "R1903")
      (value "10k")
      (footprint "eagle-import:0603")
      (libsource (lib "eagle-import") (part "R0603_MET_"))
    )
    (comp (ref "R1904")
      (value "10k")
      (footprint "eagle-import:0603")
      (libsource (lib "eagle-import") (part "R0603_MET_"))
    )
    (comp (ref "R1905")
      (value "47")
      (footprint "eagle-import:0603")
      (libsource (lib "eagle-import") (part "R0603_MET_"))
    )
    (comp (ref "R1906")
      (value "47")
      (footprint "eagle-import:0603")
      (libsource (lib "eagle-import") (part "R0603_MET_"))
    )
    (comp (ref "R1907")
      (value "10k")
      (footprint "eagle-import:0603")
      (libsource (lib "eagle-import") (part "R0603_MET_"))
    )
    (comp (ref "R1908")
      (value "10k")
      (footprint "eagle-import:0603")
      (libsource (lib "eagle-import") (part "R0603_MET_"))
    )
    (comp (ref "X1901")
      (value "43045-1000_MOLEX_10PIN")
      (footprint "eagle-import:X_TH_MOLEX_43045-1000_R_REV01")
      (fields (field (name "PDF-LOCAL") "file:///C:\\Eagle-Datasheet\\Steckverbindung\\430451000_Molex.pdf"))
      (libsource (lib "eagle-import") (part "43045-10?_MOLEX_10PIN00"))
    )
    (comp (ref "C801")
      (value "2.2µ")
      (footprint "eagle-import:0603")
      (libsource (lib "eagle-import") (part "C0603_X7R_"))
    )
    (comp (ref "C802")
      (value "100n")
      (footprint "eagle-import:0603")
      (libsource (lib "eagle-import") (part "C0603_X7R_"))
    )
    (comp (ref "C803")
      (value "100n")
      (footprint "eagle-import:0603")
      (libsource (lib "eagle-import") (part "C0603_X7R_"))
    )
    (comp (ref "C804")
      (value "100n")
      (footprint "eagle-import:0603")
      (libsource (lib "eagle-import") (part "C0603_X7R_"))
    )
    (comp (ref "C805")
      (value "100n")
      (footprint "eagle-import:0603")
      (libsource (lib "eagle-import") (part "C0603_X7R_"))
    )
    (comp (ref "C806")
      (value "100n")
      (footprint "eagle-import:0603")
      (libsource (lib "eagle-import") (part "C0603_X7R_"))
    )
    (comp (ref "C807")
      (value "100n")
      (footprint "eagle-import:0603")
      (libsource (lib "eagle-import") (part "C0603_X7R_"))
    )
    (comp (ref "D801")
      (value "PESD1CAN")
      (footprint "eagle-import:D_SMD_SOT23_(TO-236AB)_R_NXP_REV01")
      (fields (field (name "PDF-LOCAL") "file:///C:\\Eagle-Datasheet\\TVS\\PESD1CAN_NXP.pdf"))
      (libsource (lib "eagle-import") (part "PESD1CAN"))
    )
    (comp (ref "IC801")
      (value "KA7805ERTF")
      (footprint "eagle-import:IC_SMD_TO-252_(D-PAK)_R_FAIRCHILD_REV01")
      (fields
        (field (name "PDF-LOCAL") "file:///C:\\Eagle-Datasheet\\Spannungsregler\\KA7805E_Fairchild.pdf")
      )
      (libsource (lib "eagle-import") (part "KA78ERTF05"))
    )
    (comp (ref "IC802")
      (value "CPC1008N")
      (footprint "eagle-import:K_SMD_SOP-4_R_IXYS_REV01")
      (fields (field (name "PDF-LOCAL") "file:///C:\\Eagle-Datasheet\\Relais\\CPC1008N_IXYS.pdf"))
      (libsource (lib "eagle-import") (part "CPC1008N"))
    )
    (comp (ref "IC803")
      (value "TJA1052IT/1Y")
      (footprint "eagle-import:IC_SMD_SO16_(SOT162-1)_R_NXP_REV01")
      (fields (field (name "PDF-LOCAL") "file:///C:\\Eagle-Datasheet\\Schnittstellen-IC\\TJA1052I_NXP.pdf"))
      (libsource (lib "eagle-import") (part "TJA1052IT/1Y"))
    )
    (comp (ref "L801")
      (value "B82789C0513N002")
      (footprint "eagle-import:L_SMD_FILTER_HF_R_EPCOS_SIMDAD_1812_REV01")
      (fields (field (name "PDF-LOCAL") "file:///C:\\Eagle-Datasheet\\Induktivitaet\\B82789C0_EPCOS.pdf"))
      (libsource (lib "eagle-import") (part "B82789C0513N002"))
    )
    (comp (ref "LSP801")
      (value "PAD_2.0X1.5MM")
      (footprint "eagle-import:PAD2.0X1.5MM")
      (libsource (lib "eagle-import") (part "PAD_2.0X1.5MM"))
    )
    (comp (ref "LSP802")
      (value "PAD_2.0X1.5MM")
      (footprint "eagle-import:PAD2.0X1.5MM")
      (libsource (lib "eagle-import") (part "PAD_2.0X1.5MM"))
    )
    (comp (ref "LSP803")
      (value "PAD_2.0X1.5MM")
      (footprint "eagle-import:PAD2.0X1.5MM")
      (libsource (lib "eagle-import") (part "PAD_2.0X1.5MM"))
    )
    (comp (ref "LSP804")
      (value "PAD_2.0X1.5MM")
      (footprint "eagle-import:PAD2.0X1.5MM")
      (libsource (lib "eagle-import") (part "PAD_2.0X1.5MM"))
    )
    (comp (ref "LSP805")
      (value "PAD_2.0X1.5MM")
      (footprint "eagle-import:PAD2.0X1.5MM")
      (libsource (lib "eagle-import") (part "PAD_2.0X1.5MM"))
    )
    (comp (ref "LSP806")
      (value "PAD_2.0X1.5MM")
      (footprint "eagle-import:PAD2.0X1.5MM")
      (libsource (lib "eagle-import") (part "PAD_2.0X1.5MM"))
    )
    (comp (ref "LSP807")
      (value "PAD_2.0X1.5MM")
      (footprint "eagle-import:PAD2.0X1.5MM")
      (libsource (lib "eagle-import") (part "PAD_2.0X1.5MM"))
    )
    (comp (ref "R801")
      (value "62R")
      (footprint "eagle-import:0603")
      (libsource (lib "eagle-import") (part "R0603_CARB_"))
    )
    (comp (ref "R802")
      (value "62R")
      (footprint "eagle-import:0603")
      (libsource (lib "eagle-import") (part "R0603_CARB_"))
    )
    (comp (ref "R803")
      (value "10k")
      (footprint "eagle-import:0603")
      (libsource (lib "eagle-import") (part "R0603_CARB_"))
    )
    (comp (ref "R804")
      (value "430")
      (footprint "eagle-import:0603")
      (libsource (lib "eagle-import") (part "R0603_CARB_"))
    )
    (comp (ref "R805")
      (value "10k")
      (footprint "eagle-import:0603")
      (libsource (lib "eagle-import") (part "R0603_CARB_"))
    )
    (comp (ref "R806")
      (value "10")
      (footprint "eagle-import:0603")
      (libsource (lib "eagle-import") (part "R0603_CARB_"))
    )
    (comp (ref "T801")
      (value "IRLML0100TRPBF")
      (footprint "eagle-import:V_SMD_SOT-23_(TO-236AB)_R_IR_REV01")
      (fields (field (name "PDF-LOCAL") "file:///C:\\Eagle-Datasheet\\Transistoren\\IRLML0100PBF-1_IR.pdf"))
      (libsource (lib "eagle-import") (part "IR?LML0100TRPBF"))
    )
    (comp (ref "X801")
      (value "43045-0400_MOLEX_4PIN")
      (footprint "eagle-import:X_TH_MOLEX_43045-0400_R_REV01")
      (fields (field (name "PDF-LOCAL") "file:///C:\\Eagle-Datasheet\\Steckverbindung\\430450400_Molex.pdf"))
      (libsource (lib "eagle-import") (part "43045-04?_MOLEX_4PIN00"))
    )
    (comp (ref "LSP901")
      (value "PAD_2.0X1.5MM")
      (footprint "eagle-import:PAD2.0X1.5MM")
      (libsource (lib "eagle-import") (part "PAD_2.0X1.5MM"))
    )
    (comp (ref "R901")
      (value "10k")
      (footprint "eagle-import:0603")
      (libsource (lib "eagle-import") (part "R0603_MET_"))
    )
    (comp (ref "R902")
      (value "10")
      (footprint "eagle-import:0603")
      (libsource (lib "eagle-import") (part "R0603_MET_"))
    )
    (comp (ref "SV901")
      (value "MA04-2")
      (footprint "eagle-import:MA04-2")
      (libsource (lib "eagle-import") (part "MA04-2"))
    )
    (comp (ref "T901")
      (value "BUK964R8-60E")
      (footprint "eagle-import:V_SMD_TO-263_(D²PAK)_R_NXP_REV01")
      (fields (field (name "PDF-LOCAL") "file:///C:\\Eagle-Datasheet\\Transistoren\\BUK964R8-60E_NXP.pdf"))
      (libsource (lib "eagle-import") (part "BUK?964R8-60E"))
    )
    (comp (ref "D1001")
      (value "DIODE-DO214BA")
      (footprint "eagle-import:DO214BA")
      (libsource (lib "eagle-import") (part "DIODE-DO214BA"))
    )
    (comp (ref "D1002")
      (value "DIODE-DO214BA")
      (footprint "eagle-import:DO214BA")
      (libsource (lib "eagle-import") (part "DIODE-DO214BA"))
    )
    (comp (ref "D1003")
      (value "DIODE-DO214BA")
      (footprint "eagle-import:DO214BA")
      (libsource (lib "eagle-import") (part "DIODE-DO214BA"))
    )
    (comp (ref "F1001")
      (value "4,00A_UMT")
      (footprint "eagle-import:F_SMD_11,00MMX3,00MMX3,00MM_(UMT)_R_SCHURTER_REV01")
      (fields (field (name "PDF-LOCAL") "file:///C:\\Eagle-Datasheet\\Sicherungen\\UMT_250_Schurter.pdf"))
      (libsource (lib "eagle-import") (part "_UMT4,00A"))
    )
    (comp (ref "F1002")
      (value "4,00A_UMT")
      (footprint "eagle-import:F_SMD_11,00MMX3,00MMX3,00MM_(UMT)_R_SCHURTER_REV01")
      (fields (field (name "PDF-LOCAL") "file:///C:\\Eagle-Datasheet\\Sicherungen\\UMT_250_Schurter.pdf"))
      (libsource (lib "eagle-import") (part "_UMT4,00A"))
    )
    (comp (ref "F1003")
      (value "4,00A_UMT")
      (footprint "eagle-import:F_SMD_11,00MMX3,00MMX3,00MM_(UMT)_R_SCHURTER_REV01")
      (fields (field (name "PDF-LOCAL") "file:///C:\\Eagle-Datasheet\\Sicherungen\\UMT_250_Schurter.pdf"))
      (libsource (lib "eagle-import") (part "_UMT4,00A"))
    )
    (comp (ref "IC1001")
      (value "AQV252G2S")
      (footprint "eagle-import:K_SMD_SOP-6_R_PANASONIC_REV01")
      (fields (field (name "PDF-LOCAL") "file:///C:\\Eagle-Datasheet\\Relais\\AQV252G2_Panasonic.pdf"))
      (libsource (lib "eagle-import") (part "AQV25?S2G2"))
    )
    (comp (ref "IC1002")
      (value "AQV252G2S")
      (footprint "eagle-import:K_SMD_SOP-6_R_PANASONIC_REV01")
      (fields (field (name "PDF-LOCAL") "file:///C:\\Eagle-Datasheet\\Relais\\AQV252G2_Panasonic.pdf"))
      (libsource (lib "eagle-import") (part "AQV25?S2G2"))
    )
    (comp (ref "IC1003")
      (value "AQV252G2S")
      (footprint "eagle-import:K_SMD_SOP-6_R_PANASONIC_REV01")
      (fields (field (name "PDF-LOCAL") "file:///C:\\Eagle-Datasheet\\Relais\\AQV252G2_Panasonic.pdf"))
      (libsource (lib "eagle-import") (part "AQV25?S2G2"))
    )
    (comp (ref "LSP1001")
      (value "PAD_2.0X1.5MM")
      (footprint "eagle-import:PAD2.0X1.5MM")
      (libsource (lib "eagle-import") (part "PAD_2.0X1.5MM"))
    )
    (comp (ref "LSP1002")
      (value "PAD_2.0X1.5MM")
      (footprint "eagle-import:PAD2.0X1.5MM")
      (libsource (lib "eagle-import") (part "PAD_2.0X1.5MM"))
    )
    (comp (ref "LSP1003")
      (value "PAD_2.0X1.5MM")
      (footprint "eagle-import:PAD2.0X1.5MM")
      (libsource (lib "eagle-import") (part "PAD_2.0X1.5MM"))
    )
    (comp (ref "R1001")
      (value "10")
      (footprint "eagle-import:0603")
      (libsource (lib "eagle-import") (part "R0603_MET_"))
    )
    (comp (ref "R1002")
      (value "10k")
      (footprint "eagle-import:0603")
      (libsource (lib "eagle-import") (part "R0603_MET_"))
    )
    (comp (ref "R1003")
      (value "430")
      (footprint "eagle-import:0603")
      (libsource (lib "eagle-import") (part "R0603_MET_"))
    )
    (comp (ref "R1004")
      (value "10")
      (footprint "eagle-import:0603")
      (libsource (lib "eagle-import") (part "R0603_MET_"))
    )
    (comp (ref "R1005")
      (value "10k")
      (footprint "eagle-import:0603")
      (libsource (lib "eagle-import") (part "R0603_MET_"))
    )
    (comp (ref "R1006")
      (value "430")
      (footprint "eagle-import:0603")
      (libsource (lib "eagle-import") (part "R0603_MET_"))
    )
    (comp (ref "R1007")
      (value "10")
      (footprint "eagle-import:0603")
      (libsource (lib "eagle-import") (part "R0603_MET_"))
    )
    (comp (ref "R1008")
      (value "10k")
      (footprint "eagle-import:0603")
      (libsource (lib "eagle-import") (part "R0603_MET_"))
    )
    (comp (ref "R1009")
      (value "430")
      (footprint "eagle-import:0603")
      (libsource (lib "eagle-import") (part "R0603_MET_"))
    )
    (comp (ref "T1001")
      (value "IRLML0100TRPBF")
      (footprint "eagle-import:V_SMD_SOT-23_(TO-236AB)_R_IR_REV01")
      (fields (field (name "PDF-LOCAL") "file:///C:\\Eagle-Datasheet\\Transistoren\\IRLML0100PBF-1_IR.pdf"))
      (libsource (lib "eagle-import") (part "IR?LML0100TRPBF"))
    )
    (comp (ref "T1002")
      (value "IRLML0100TRPBF")
      (footprint "eagle-import:V_SMD_SOT-23_(TO-236AB)_R_IR_REV01")
      (fields (field (name "PDF-LOCAL") "file:///C:\\Eagle-Datasheet\\Transistoren\\IRLML0100PBF-1_IR.pdf"))
      (libsource (lib "eagle-import") (part "IR?LML0100TRPBF"))
    )
    (comp (ref "T1003")
      (value "IRLML0100TRPBF")
      (footprint "eagle-import:V_SMD_SOT-23_(TO-236AB)_R_IR_REV01")
      (fields (field (name "PDF-LOCAL") "file:///C:\\Eagle-Datasheet\\Transistoren\\IRLML0100PBF-1_IR.pdf"))
      (libsource (lib "eagle-import") (part "IR?LML0100TRPBF"))
    )
    (comp (ref "X1201")
      (value "43045-0400_MOLEX_4PIN")
      (footprint "eagle-import:X_TH_MOLEX_43045-0400_R_REV01")
      (fields (field (name "PDF-LOCAL") "file:///C:\\Eagle-Datasheet\\Steckverbindung\\430450400_Molex.pdf"))
      (libsource (lib "eagle-import") (part "43045-04?_MOLEX_4PIN00"))
    )
    (comp (ref "X1202")
      (value "43045-0400_MOLEX_4PIN")
      (footprint "eagle-import:X_TH_MOLEX_43045-0400_R_REV01")
      (fields (field (name "PDF-LOCAL") "file:///C:\\Eagle-Datasheet\\Steckverbindung\\430450400_Molex.pdf"))
      (libsource (lib "eagle-import") (part "43045-04?_MOLEX_4PIN00"))
    )
    (comp (ref "X1203")
      (value "43045-0400_MOLEX_4PIN")
      (footprint "eagle-import:X_TH_MOLEX_43045-0400_R_REV01")
      (fields (field (name "PDF-LOCAL") "file:///C:\\Eagle-Datasheet\\Steckverbindung\\430450400_Molex.pdf"))
      (libsource (lib "eagle-import") (part "43045-04?_MOLEX_4PIN00"))
    )
    (comp (ref "D2001")
      (value "DIODE-DO214BA")
      (footprint "eagle-import:DO214BA")
      (libsource (lib "eagle-import") (part "DIODE-DO214BA"))
    )
    (comp (ref "D2002")
      (value "DIODE-DO214BA")
      (footprint "eagle-import:DO214BA")
      (libsource (lib "eagle-import") (part "DIODE-DO214BA"))
    )
    (comp (ref "D2003")
      (value "DIODE-DO214BA")
      (footprint "eagle-import:DO214BA")
      (libsource (lib "eagle-import") (part "DIODE-DO214BA"))
    )
    (comp (ref "D2004")
      (value "DIODE-DO214BA")
      (footprint "eagle-import:DO214BA")
      (libsource (lib "eagle-import") (part "DIODE-DO214BA"))
    )
    (comp (ref "D2005")
      (value "DIODE-DO214BA")
      (footprint "eagle-import:DO214BA")
      (libsource (lib "eagle-import") (part "DIODE-DO214BA"))
    )
    (comp (ref "D2006")
      (value "DIODE-DO214BA")
      (footprint "eagle-import:DO214BA")
      (libsource (lib "eagle-import") (part "DIODE-DO214BA"))
    )
    (comp (ref "IC2001")
      (value "AQV25G2S")
      (footprint "eagle-import:SOP06")
      (libsource (lib "eagle-import") (part "AQV25G2S"))
    )
    (comp (ref "IC2002")
      (value "AQV25G2S")
      (footprint "eagle-import:SOP06")
      (libsource (lib "eagle-import") (part "AQV25G2S"))
    )
    (comp (ref "IC2003")
      (value "AQV25G2S")
      (footprint "eagle-import:SOP06")
      (libsource (lib "eagle-import") (part "AQV25G2S"))
    )
    (comp (ref "IC2004")
      (value "AQV25G2S")
      (footprint "eagle-import:SOP06")
      (libsource (lib "eagle-import") (part "AQV25G2S"))
    )
    (comp (ref "IC2005")
      (value "AQV25G2S")
      (footprint "eagle-import:SOP06")
      (libsource (lib "eagle-import") (part "AQV25G2S"))
    )
    (comp (ref "IC2006")
      (value "AQV25G2S")
      (footprint "eagle-import:SOP06")
      (libsource (lib "eagle-import") (part "AQV25G2S"))
    )
    (comp (ref "LSP2001")
      (value "PAD_2.0X1.5MM")
      (footprint "eagle-import:PAD2.0X1.5MM")
      (libsource (lib "eagle-import") (part "PAD_2.0X1.5MM"))
    )
    (comp (ref "LSP2002")
      (value "PAD_2.0X1.5MM")
      (footprint "eagle-import:PAD2.0X1.5MM")
      (libsource (lib "eagle-import") (part "PAD_2.0X1.5MM"))
    )
    (comp (ref "LSP2003")
      (value "PAD_2.0X1.5MM")
      (footprint "eagle-import:PAD2.0X1.5MM")
      (libsource (lib "eagle-import") (part "PAD_2.0X1.5MM"))
    )
    (comp (ref "LSP2004")
      (value "PAD_2.0X1.5MM")
      (footprint "eagle-import:PAD2.0X1.5MM")
      (libsource (lib "eagle-import") (part "PAD_2.0X1.5MM"))
    )
    (comp (ref "LSP2005")
      (value "PAD_2.0X1.5MM")
      (footprint "eagle-import:PAD2.0X1.5MM")
      (libsource (lib "eagle-import") (part "PAD_2.0X1.5MM"))
    )
    (comp (ref "LSP2006")
      (value "PAD_2.0X1.5MM")
      (footprint "eagle-import:PAD2.0X1.5MM")
      (libsource (lib "eagle-import") (part "PAD_2.0X1.5MM"))
    )
    (comp (ref "R2001")
      (value "10")
      (footprint "eagle-import:0603")
      (libsource (lib "eagle-import") (part "R0603_MET_"))
    )
    (comp (ref "R2002")
      (value "10")
      (footprint "eagle-import:0603")
      (libsource (lib "eagle-import") (part "R0603_MET_"))
    )
    (comp (ref "R2003")
      (value "10k")
      (footprint "eagle-import:0603")
      (libsource (lib "eagle-import") (part "R0603_MET_"))
    )
    (comp (ref "R2004")
      (value "10k")
      (footprint "eagle-import:0603")
      (libsource (lib "eagle-import") (part "R0603_MET_"))
    )
    (comp (ref "R2005")
      (value "430")
      (footprint "eagle-import:0603")
      (libsource (lib "eagle-import") (part "R0603_MET_"))
    )
    (comp (ref "R2006")
      (value "430")
      (footprint "eagle-import:0603")
      (libsource (lib "eagle-import") (part "R0603_MET_"))
    )
    (comp (ref "R2007")
      (value "10")
      (footprint "eagle-import:0603")
      (libsource (lib "eagle-import") (part "R0603_MET_"))
    )
    (comp (ref "R2008")
      (value "10")
      (footprint "eagle-import:0603")
      (libsource (lib "eagle-import") (part "R0603_MET_"))
    )
    (comp (ref "R2009")
      (value "10k")
      (footprint "eagle-import:0603")
      (libsource (lib "eagle-import") (part "R0603_MET_"))
    )
    (comp (ref "R2010")
      (value "10k")
      (footprint "eagle-import:0603")
      (libsource (lib "eagle-import") (part "R0603_MET_"))
    )
    (comp (ref "R2011")
      (value "430")
      (footprint "eagle-import:0603")
      (libsource (lib "eagle-import") (part "R0603_MET_"))
    )
    (comp (ref "R2012")
      (value "430")
      (footprint "eagle-import:0603")
      (libsource (lib "eagle-import") (part "R0603_MET_"))
    )
    (comp (ref "R2013")
      (value "10")
      (footprint "eagle-import:0603")
      (libsource (lib "eagle-import") (part "R0603_MET_"))
    )
    (comp (ref "R2014")
      (value "10")
      (footprint "eagle-import:0603")
      (libsource (lib "eagle-import") (part "R0603_MET_"))
    )
    (comp (ref "R2015")
      (value "10k")
      (footprint "eagle-import:0603")
      (libsource (lib "eagle-import") (part "R0603_MET_"))
    )
    (comp (ref "R2016")
      (value "10k")
      (footprint "eagle-import:0603")
      (libsource (lib "eagle-import") (part "R0603_MET_"))
    )
    (comp (ref "R2017")
      (value "430")
      (footprint "eagle-import:0603")
      (libsource (lib "eagle-import") (part "R0603_MET_"))
    )
    (comp (ref "R2018")
      (value "430")
      (footprint "eagle-import:0603")
      (libsource (lib "eagle-import") (part "R0603_MET_"))
    )
    (comp (ref "T2001")
      (value "IRLML0100TRPBF")
      (footprint "eagle-import:V_SMD_SOT-23_(TO-236AB)_R_IR_REV01")
      (fields (field (name "PDF-LOCAL") "file:///C:\\Eagle-Datasheet\\Transistoren\\IRLML0100PBF-1_IR.pdf"))
      (libsource (lib "eagle-import") (part "IR?LML0100TRPBF"))
    )
    (comp (ref "T2002")
      (value "IRLML0100TRPBF")
      (footprint "eagle-import:V_SMD_SOT-23_(TO-236AB)_R_IR_REV01")
      (fields (field (name "PDF-LOCAL") "file:///C:\\Eagle-Datasheet\\Transistoren\\IRLML0100PBF-1_IR.pdf"))
      (libsource (lib "eagle-import") (part "IR?LML0100TRPBF"))
    )
    (comp (ref "T2003")
      (value "IRLML0100TRPBF")
      (footprint "eagle-import:V_SMD_SOT-23_(TO-236AB)_R_IR_REV01")
      (fields (field (name "PDF-LOCAL") "file:///C:\\Eagle-Datasheet\\Transistoren\\IRLML0100PBF-1_IR.pdf"))
      (libsource (lib "eagle-import") (part "IR?LML0100TRPBF"))
    )
    (comp (ref "T2004")
      (value "IRLML0100TRPBF")
      (footprint "eagle-import:V_SMD_SOT-23_(TO-236AB)_R_IR_REV01")
      (fields (field (name "PDF-LOCAL") "file:///C:\\Eagle-Datasheet\\Transistoren\\IRLML0100PBF-1_IR.pdf"))
      (libsource (lib "eagle-import") (part "IR?LML0100TRPBF"))
    )
    (comp (ref "T2005")
      (value "IRLML0100TRPBF")
      (footprint "eagle-import:V_SMD_SOT-23_(TO-236AB)_R_IR_REV01")
      (fields (field (name "PDF-LOCAL") "file:///C:\\Eagle-Datasheet\\Transistoren\\IRLML0100PBF-1_IR.pdf"))
      (libsource (lib "eagle-import") (part "IR?LML0100TRPBF"))
    )
    (comp (ref "T2006")
      (value "IRLML0100TRPBF")
      (footprint "eagle-import:V_SMD_SOT-23_(TO-236AB)_R_IR_REV01")
      (fields (field (name "PDF-LOCAL") "file:///C:\\Eagle-Datasheet\\Transistoren\\IRLML0100PBF-1_IR.pdf"))
      (libsource (lib "eagle-import") (part "IR?LML0100TRPBF"))
    )
    (comp (ref "X2001")
      (value "43045-1200_MOLEX_12PIN")
      (footprint "eagle-import:X_TH_MOLEX_43045-1200_R_REV01")
      (fields (field (name "PDF-LOCAL") "file:///C:\\Eagle-Datasheet\\Steckverbindung\\430451200_Molex.pdf"))
      (libsource (lib "eagle-import") (part "43045-12?_MOLEX_12PIN00"))
    )
    (comp (ref "C1101")
      (value "100n")
      (footprint "eagle-import:0603")
      (libsource (lib "eagle-import") (part "C0603_X7R_"))
    )
    (comp (ref "C1102")
      (value "1µ")
      (footprint "eagle-import:0603")
      (libsource (lib "eagle-import") (part "C0603_X7R_"))
    )
    (comp (ref "C1103")
      (value "100n")
      (footprint "eagle-import:0603")
      (libsource (lib "eagle-import") (part "C0603_X7R_"))
    )
    (comp (ref "C1104")
      (value "100n")
      (footprint "eagle-import:0603")
      (libsource (lib "eagle-import") (part "C0603_X7R_"))
    )
    (comp (ref "C1105")
      (value "100n")
      (footprint "eagle-import:0603")
      (libsource (lib "eagle-import") (part "C0603_X7R_"))
    )
    (comp (ref "C1106")
      (value "100n")
      (footprint "eagle-import:0603")
      (libsource (lib "eagle-import") (part "C0603_X7R_"))
    )
    (comp (ref "D1101")
      (value "CDSOD323-T05")
      (footprint "eagle-import:D_SMD_SOD323_(SC-76)_R_BOURNS_REV01")
      (libsource (lib "eagle-import") (part "CDSOD323-T?05"))
    )
    (comp (ref "D1102")
      (value "CDSOD323-T05")
      (footprint "eagle-import:D_SMD_SOD323_(SC-76)_R_BOURNS_REV01")
      (libsource (lib "eagle-import") (part "CDSOD323-T?05"))
    )
    (comp (ref "D1103")
      (value "CDSOD323-T05")
      (footprint "eagle-import:D_SMD_SOD323_(SC-76)_R_BOURNS_REV01")
      (libsource (lib "eagle-import") (part "CDSOD323-T?05"))
    )
    (comp (ref "IC1101")
      (value "UA78L05ACPK")
      (footprint "eagle-import:IC_SMD_SOT-89_(SC-62_TO-243)_(R-PSSO-F3)_R_TI_REV01")
      (fields
        (field (name "PDF-LOCAL") "file:///C:\\Eagle-Datasheet\\Spannungsregler\\UA78L00_Texas_Instruments.pdf")
      )
      (libsource (lib "eagle-import") (part "UA78L?PK05AC"))
    )
    (comp (ref "IC1102")
      (value "ADUM3300ARW")
      (footprint "eagle-import:IC_SMD_SOIC-16_(JEDEC_MS-013-AA)_R_ANALOG_REV01")
      (libsource (lib "eagle-import") (part "ADUM3300ARW"))
    )
    (comp (ref "LSP1101")
      (value "PAD_2.0X1.5MM")
      (footprint "eagle-import:PAD2.0X1.5MM")
      (libsource (lib "eagle-import") (part "PAD_2.0X1.5MM"))
    )
    (comp (ref "LSP1102")
      (value "PAD_2.0X1.5MM")
      (footprint "eagle-import:PAD2.0X1.5MM")
      (libsource (lib "eagle-import") (part "PAD_2.0X1.5MM"))
    )
    (comp (ref "LSP1103")
      (value "PAD_2.0X1.5MM")
      (footprint "eagle-import:PAD2.0X1.5MM")
      (libsource (lib "eagle-import") (part "PAD_2.0X1.5MM"))
    )
    (comp (ref "R1101")
      (value "47")
      (footprint "eagle-import:0603")
      (libsource (lib "eagle-import") (part "R0603_MET_"))
    )
    (comp (ref "R1102")
      (value "47")
      (footprint "eagle-import:0603")
      (libsource (lib "eagle-import") (part "R0603_MET_"))
    )
    (comp (ref "R1103")
      (value "47")
      (footprint "eagle-import:0603")
      (libsource (lib "eagle-import") (part "R0603_MET_"))
    )
    (comp (ref "R1104")
      (value "10k")
      (footprint "eagle-import:0603")
      (libsource (lib "eagle-import") (part "R0603_MET_"))
    )
    (comp (ref "R1105")
      (value "10k")
      (footprint "eagle-import:0603")
      (libsource (lib "eagle-import") (part "R0603_MET_"))
    )
    (comp (ref "R1106")
      (value "10k")
      (footprint "eagle-import:0603")
      (libsource (lib "eagle-import") (part "R0603_MET_"))
    )
    (comp (ref "C1701")
      (value "100n")
      (footprint "eagle-import:0603")
      (libsource (lib "eagle-import") (part "C0603_X7R_"))
    )
    (comp (ref "C1702")
      (value "100n")
      (footprint "eagle-import:0603")
      (libsource (lib "eagle-import") (part "C0603_X7R_"))
    )
    (comp (ref "C1703")
      (value "1µ")
      (footprint "eagle-import:0603")
      (libsource (lib "eagle-import") (part "C0603_X7R_"))
    )
    (comp (ref "C1704")
      (value "100n")
      (footprint "eagle-import:0603")
      (libsource (lib "eagle-import") (part "C0603_X7R_"))
    )
    (comp (ref "C1705")
      (value "100n")
      (footprint "eagle-import:0603")
      (libsource (lib "eagle-import") (part "C0603_X7R_"))
    )
    (comp (ref "C1706")
      (value "100n")
      (footprint "eagle-import:0603")
      (libsource (lib "eagle-import") (part "C0603_X7R_"))
    )
    (comp (ref "C1707")
      (value "100n")
      (footprint "eagle-import:0603")
      (libsource (lib "eagle-import") (part "C0603_X7R_"))
    )
    (comp (ref "C1708")
      (value "100n")
      (footprint "eagle-import:0603")
      (libsource (lib "eagle-import") (part "C0603_X7R_"))
    )
    (comp (ref "D1701")
      (value "MM3Z3V3ST1G")
      (footprint "eagle-import:D_SMD_SOD323_(SC-76)_R_ON_REV01")
      (fields
        (field (name "PDF-LOCAL") "file:///C:\\Eagle-Datasheet\\Dioden\\MM3ZxxxT1-D_OnSemiconductor.pdf")
      )
      (libsource (lib "eagle-import") (part "MM3Z?T1G4V7"))
    )
    (comp (ref "D1702")
      (value "MM3Z3V3ST1G")
      (footprint "eagle-import:D_SMD_SOD323_(SC-76)_R_ON_REV01")
      (fields
        (field (name "PDF-LOCAL") "file:///C:\\Eagle-Datasheet\\Dioden\\MM3ZxxxT1-D_OnSemiconductor.pdf")
      )
      (libsource (lib "eagle-import") (part "MM3Z?T1G4V7"))
    )
    (comp (ref "D1703")
      (value "MM3Z3V3ST1G")
      (footprint "eagle-import:D_SMD_SOD323_(SC-76)_R_ON_REV01")
      (fields
        (field (name "PDF-LOCAL") "file:///C:\\Eagle-Datasheet\\Dioden\\MM3ZxxxT1-D_OnSemiconductor.pdf")
      )
      (libsource (lib "eagle-import") (part "MM3Z?T1G4V7"))
    )
    (comp (ref "D1704")
      (value "MM3Z3V3ST1G")
      (footprint "eagle-import:D_SMD_SOD323_(SC-76)_R_ON_REV01")
      (fields
        (field (name "PDF-LOCAL") "file:///C:\\Eagle-Datasheet\\Dioden\\MM3ZxxxT1-D_OnSemiconductor.pdf")
      )
      (libsource (lib "eagle-import") (part "MM3Z?T1G4V7"))
    )
    (comp (ref "D1705")
      (value "MM3Z3V3ST1G")
      (footprint "eagle-import:D_SMD_SOD323_(SC-76)_R_ON_REV01")
      (fields
        (field (name "PDF-LOCAL") "file:///C:\\Eagle-Datasheet\\Dioden\\MM3ZxxxT1-D_OnSemiconductor.pdf")
      )
      (libsource (lib "eagle-import") (part "MM3Z?T1G4V7"))
    )
    (comp (ref "IC1701")
      (value "ADR3425ARJZ")
      (footprint "eagle-import:IC_SMD_SOT23-6_(MO-178-AB)_R_AD_REV01")
      (fields
        (field (name "PDF-LOCAL") "file:///C:\\Eagle-Datasheet\\Referenzen\\ADR3412_ADR3420_ADR3425_ADR3430_ADR3433_ADR3440_ADR3450_Analog_Devices.pdf")
      )
      (libsource (lib "eagle-import") (part "ADR3425ARJZ"))
    )
    (comp (ref "LSP1701")
      (value "PAD_2.0X1.5MM")
      (footprint "eagle-import:PAD2.0X1.5MM")
      (libsource (lib "eagle-import") (part "PAD_2.0X1.5MM"))
    )
    (comp (ref "LSP1702")
      (value "PAD_2.0X1.5MM")
      (footprint "eagle-import:PAD2.0X1.5MM")
      (libsource (lib "eagle-import") (part "PAD_2.0X1.5MM"))
    )
    (comp (ref "LSP1703")
      (value "PAD_2.0X1.5MM")
      (footprint "eagle-import:PAD2.0X1.5MM")
      (libsource (lib "eagle-import") (part "PAD_2.0X1.5MM"))
    )
    (comp (ref "LSP1704")
      (value "PAD_2.0X1.5MM")
      (footprint "eagle-import:PAD2.0X1.5MM")
      (libsource (lib "eagle-import") (part "PAD_2.0X1.5MM"))
    )
    (comp (ref "LSP1705")
      (value "PAD_2.0X1.5MM")
      (footprint "eagle-import:PAD2.0X1.5MM")
      (libsource (lib "eagle-import") (part "PAD_2.0X1.5MM"))
    )
    (comp (ref "R1701")
      (value "0")
      (footprint "eagle-import:0603")
      (libsource (lib "eagle-import") (part "R0603_MET_"))
    )
    (comp (ref "R1702")
      (value "4.75k")
      (footprint "eagle-import:0603")
      (libsource (lib "eagle-import") (part "R0603_MET_"))
    )
    (comp (ref "R1703")
      (value "0")
      (footprint "eagle-import:0603")
      (libsource (lib "eagle-import") (part "R0603_MET_"))
    )
    (comp (ref "R1704")
      (value "4.75k")
      (footprint "eagle-import:0603")
      (libsource (lib "eagle-import") (part "R0603_MET_"))
    )
    (comp (ref "R1705")
      (value "0")
      (footprint "eagle-import:0603")
      (libsource (lib "eagle-import") (part "R0603_MET_"))
    )
    (comp (ref "R1706")
      (value "4.75k")
      (footprint "eagle-import:0603")
      (libsource (lib "eagle-import") (part "R0603_MET_"))
    )
    (comp (ref "R1707")
      (value "0")
      (footprint "eagle-import:0603")
      (libsource (lib "eagle-import") (part "R0603_MET_"))
    )
    (comp (ref "R1708")
      (value "4.75k")
      (footprint "eagle-import:0603")
      (libsource (lib "eagle-import") (part "R0603_MET_"))
    )
    (comp (ref "R1709")
      (value "0")
      (footprint "eagle-import:0603")
      (libsource (lib "eagle-import") (part "R0603_MET_"))
    )
    (comp (ref "R1710")
      (value "4.75k")
      (footprint "eagle-import:0603")
      (libsource (lib "eagle-import") (part "R0603_MET_"))
    )
    (comp (ref "X1701")
      (value "43045-1200_MOLEX_12PIN")
      (footprint "eagle-import:X_TH_MOLEX_43045-1200_R_REV01")
      (fields (field (name "PDF-LOCAL") "file:///C:\\Eagle-Datasheet\\Steckverbindung\\430451200_Molex.pdf"))
      (libsource (lib "eagle-import") (part "43045-12?_MOLEX_12PIN00"))
    )
  )
  (nets
    (net (code "1") (name "+3.3V_0") (class "Default")
      (node (ref "C1105") (pin "1") (pinfunction "1_1") (pintype "passive"))
      (node (ref "C1106") (pin "1") (pinfunction "1_1") (pintype "passive"))
      (node (ref "C1306") (pin "1") (pinfunction "1_1") (pintype "passive"))
      (node (ref "C1703") (pin "1") (pinfunction "1_1") (pintype "passive"))
      (node (ref "C1704") (pin "1") (pinfunction "1_1") (pintype "passive"))
      (node (ref "C1905") (pin "1") (pinfunction "1_1") (pintype "passive"))
      (node (ref "C1907") (pin "1") (pinfunction "1_1") (pintype "passive"))
      (node (ref "C807") (pin "2") (pinfunction "2_2") (pintype "passive"))
      (node (ref "IC1001") (pin "1") (pinfunction "1_1") (pintype "bidirectional"))
      (node (ref "IC1002") (pin "1") (pinfunction "1_1") (pintype "bidirectional"))
      (node (ref "IC1003") (pin "1") (pinfunction "1_1") (pintype "bidirectional"))
      (node (ref "IC1102") (pin "10") (pinfunction "VE2_10") (pintype "bidirectional"))
      (node (ref "IC1102") (pin "16") (pinfunction "VDD2_16") (pintype "power_in"))
      (node (ref "IC1303") (pin "1") (pinfunction "VDD1_1") (pintype "power_in"))
      (node (ref "IC1303") (pin "7") (pinfunction "VE1_7") (pintype "bidirectional"))
      (node (ref "IC1701") (pin "3") (pinfunction "ENABLE_3") (pintype "bidirectional"))
      (node (ref "IC1701") (pin "4") (pinfunction "VIN_4") (pintype "input"))
      (node (ref "IC1902") (pin "10") (pinfunction "VE2_10") (pintype "bidirectional"))
      (node (ref "IC1902") (pin "16") (pinfunction "VDD2_16") (pintype "power_in"))
      (node (ref "IC1903") (pin "10") (pinfunction "VE2_10") (pintype "bidirectional"))
      (node (ref "IC1903") (pin "16") (pinfunction "VDD2_16") (pintype "power_in"))
      (node (ref "IC2001") (pin "1") (pinfunction "A_1") (pintype "passive"))
      (node (ref "IC2002") (pin "1") (pinfunction "A_1") (pintype "passive"))
      (node (ref "IC2003") (pin "1") (pinfunction "A_1") (pintype "passive"))
      (node (ref "IC2004") (pin "1") (pinfunction "A_1") (pintype "passive"))
      (node (ref "IC2005") (pin "1") (pinfunction "A_1") (pintype "passive"))
      (node (ref "IC2006") (pin "1") (pinfunction "A_1") (pintype "passive"))
      (node (ref "IC803") (pin "1") (pinfunction "VDD_1") (pintype "power_in"))
      (node (ref "JP2201") (pin "1") (pinfunction "1_1") (pintype "passive"))
      (node (ref "JP2201") (pin "3") (pinfunction "3_3") (pintype "passive"))
      (node (ref "JP2202") (pin "1") (pinfunction "1_1") (pintype "passive"))
      (node (ref "JP2202") (pin "3") (pinfunction "3_3") (pintype "passive"))
      (node (ref "LSP2101") (pin "P$1") (pinfunction "MP_P$1") (pintype "passive"))
      (node (ref "R1501") (pin "2") (pinfunction "2_2") (pintype "passive"))
      (node (ref "R804") (pin "1") (pinfunction "1_1") (pintype "passive"))
      (node (ref "SV2101") (pin "1") (pinfunction "1_1") (pintype "passive"))
      (node (ref "T1501") (pin "2") (pinfunction "S_2") (pintype "passive"))
    )
    (net (code "2") (name "+5.0V_0") (class "Default")
      (node (ref "SV2101") (pin "2") (pinfunction "2_2") (pintype "passive"))
    )
    (net (code "3") (name "ADC_MCU_0_CH_0") (class "Default")
      (node (ref "C1701") (pin "1") (pinfunction "1_1") (pintype "passive"))
      (node (ref "D1701") (pin "C") (pinfunction "C_C") (pintype "bidirectional"))
      (node (ref "JP2202") (pin "8") (pinfunction "8_8") (pintype "passive"))
      (node (ref "LSP1701") (pin "P$1") (pinfunction "MP_P$1") (pintype "passive"))
      (node (ref "R1701") (pin "2") (pinfunction "2_2") (pintype "passive"))
      (node (ref "R1702") (pin "1") (pinfunction "1_1") (pintype "passive"))
    )
    (net (code "4") (name "ADC_MCU_0_CH_1") (class "Default")
      (node (ref "C1705") (pin "1") (pinfunction "1_1") (pintype "passive"))
      (node (ref "D1703") (pin "C") (pinfunction "C_C") (pintype "bidirectional"))
      (node (ref "JP2202") (pin "7") (pinfunction "7_7") (pintype "passive"))
      (node (ref "LSP1704") (pin "P$1") (pinfunction "MP_P$1") (pintype "passive"))
      (node (ref "R1705") (pin "2") (pinfunction "2_2") (pintype "passive"))
      (node (ref "R1706") (pin "1") (pinfunction "1_1") (pintype "passive"))
    )
    (net (code "5") (name "ADC_MCU_0_CH_2") (class "Default")
      (node (ref "C1708") (pin "1") (pinfunction "1_1") (pintype "passive"))
      (node (ref "D1705") (pin "C") (pinfunction "C_C") (pintype "bidirectional"))
      (node (ref "JP2202") (pin "6") (pinfunction "6_6") (pintype "passive"))
      (node (ref "LSP1705") (pin "P$1") (pinfunction "MP_P$1") (pintype "passive"))
      (node (ref "R1709") (pin "2") (pinfunction "2_2") (pintype "passive"))
      (node (ref "R1710") (pin "1") (pinfunction "1_1") (pintype "passive"))
    )
    (net (code "6") (name "ADC_MCU_0_CH_3") (class "Default")
      (node (ref "C1702") (pin "1") (pinfunction "1_1") (pintype "passive"))
      (node (ref "D1702") (pin "C") (pinfunction "C_C") (pintype "bidirectional"))
      (node (ref "JP2202") (pin "5") (pinfunction "5_5") (pintype "passive"))
      (node (ref "LSP1702") (pin "P$1") (pinfunction "MP_P$1") (pintype "passive"))
      (node (ref "R1703") (pin "2") (pinfunction "2_2") (pintype "passive"))
      (node (ref "R1704") (pin "1") (pinfunction "1_1") (pintype "passive"))
    )
    (net (code "7") (name "ADC_MCU_0_CH_4") (class "Default")
      (node (ref "C1706") (pin "1") (pinfunction "1_1") (pintype "passive"))
      (node (ref "D1704") (pin "C") (pinfunction "C_C") (pintype "bidirectional"))
      (node (ref "JP2202") (pin "9") (pinfunction "9_9") (pintype "passive"))
      (node (ref "LSP1703") (pin "P$1") (pinfunction "MP_P$1") (pintype "passive"))
      (node (ref "R1707") (pin "2") (pinfunction "2_2") (pintype "passive"))
      (node (ref "R1708") (pin "1") (pinfunction "1_1") (pintype "passive"))
    )
    (net (code "8") (name "ANALOG_IN_CH_0") (class "Default")
      (node (ref "R1701") (pin "1") (pinfunction "1_1") (pintype "passive"))
      (node (ref "X1701") (pin "2") (pinfunction "2_2") (pintype "passive"))
    )
    (net (code "9") (name "ANALOG_IN_CH_1") (class "Default")
      (node (ref "R1705") (pin "1") (pinfunction "1_1") (pintype "passive"))
      (node (ref "X1701") (pin "4") (pinfunction "4_4") (pintype "passive"))
    )
    (net (code "10") (name "ANALOG_IN_CH_2") (class "Default")
      (node (ref "R1709") (pin "1") (pinfunction "1_1") (pintype "passive"))
      (node (ref "X1701") (pin "6") (pinfunction "6_6") (pintype "passive"))
    )
    (net (code "11") (name "ANALOG_IN_CH_3") (class "Default")
      (node (ref "R1703") (pin "1") (pinfunction "1_1") (pintype "passive"))
      (node (ref "X1701") (pin "8") (pinfunction "8_8") (pintype "passive"))
    )
    (net (code "12") (name "ANALOG_IN_CH_4") (class "Default")
      (node (ref "R1707") (pin "1") (pinfunction "1_1") (pintype "passive"))
      (node (ref "X1701") (pin "10") (pinfunction "10_10") (pintype "passive"))
    )
    (net (code "13") (name "CAN_1_H") (class "Default")
      (node (ref "D801") (pin "1") (pinfunction "1_1") (pintype "passive"))
      (node (ref "L801") (pin "2") (pinfunction "2_2") (pintype "passive"))
      (node (ref "LSP802") (pin "P$1") (pinfunction "MP_P$1") (pintype "passive"))
      (node (ref "X801") (pin "4") (pinfunction "4_4") (pintype "passive"))
    )
    (net (code "14") (name "CAN_1_L") (class "Default")
      (node (ref "D801") (pin "2") (pinfunction "2_2") (pintype "passive"))
      (node (ref "L801") (pin "1") (pinfunction "1_1") (pintype "passive"))
      (node (ref "LSP803") (pin "P$1") (pinfunction "MP_P$1") (pintype "passive"))
      (node (ref "X801") (pin "3") (pinfunction "3_3") (pintype "passive"))
    )
    (net (code "15") (name "CAN_1_RX") (class "Default")
      (node (ref "IC803") (pin "5") (pinfunction "RXD_5") (pintype "bidirectional"))
      (node (ref "JP2201") (pin "6") (pinfunction "6_6") (pintype "passive"))
      (node (ref "LSP806") (pin "P$1") (pinfunction "MP_P$1") (pintype "passive"))
    )
    (net (code "16") (name "CAN_1_TRANS_STANDBY_CONTROL") (class "Default")
      (node (ref "JP2201") (pin "5") (pinfunction "5_5") (pintype "passive"))
      (node (ref "R806") (pin "2") (pinfunction "2_2") (pintype "passive"))
    )
    (net (code "17") (name "CAN_1_TX") (class "Default")
      (node (ref "IC803") (pin "3") (pinfunction "TXD_3") (pintype "bidirectional"))
      (node (ref "JP2201") (pin "7") (pinfunction "7_7") (pintype "passive"))
      (node (ref "LSP805") (pin "P$1") (pinfunction "MP_P$1") (pintype "passive"))
    )
    (net (code "18") (name "CAN_TRANS_1_EXT_SUPPLY") (class "Default")
      (node (ref "C803") (pin "2") (pinfunction "2_2") (pintype "passive"))
      (node (ref "C805") (pin "2") (pinfunction "2_2") (pintype "passive"))
      (node (ref "C806") (pin "2") (pinfunction "2_2") (pintype "passive"))
      (node (ref "IC801") (pin "3") (pinfunction "OUT_3") (pintype "output"))
      (node (ref "IC803") (pin "11") (pinfunction "VDD_11") (pintype "power_in"))
      (node (ref "IC803") (pin "16") (pinfunction "VDD_16") (pintype "power_in"))
      (node (ref "R803") (pin "1") (pinfunction "1_1") (pintype "passive"))
    )
    (net (code "19") (name "CAN_TRANS_1_STANDBY") (class "Default")
      (node (ref "IC802") (pin "4") (pinfunction "4_4") (pintype "bidirectional"))
      (node (ref "IC803") (pin "14") (pinfunction "STB_14") (pintype "bidirectional"))
      (node (ref "LSP804") (pin "P$1") (pinfunction "MP_P$1") (pintype "passive"))
      (node (ref "R803") (pin "2") (pinfunction "2_2") (pintype "passive"))
    )
    (net (code "20") (name "CONTACTORS_COMMON_NEG") (class "Default")
      (node (ref "D1001") (pin "A") (pinfunction "A_A") (pintype "passive"))
      (node (ref "D1002") (pin "A") (pinfunction "A_A") (pintype "passive"))
      (node (ref "D1003") (pin "A") (pinfunction "A_A") (pintype "passive"))
      (node (ref "T901") (pin "2") (pinfunction "D_2") (pintype "passive"))
      (node (ref "X1201") (pin "4") (pinfunction "4_4") (pintype "passive"))
      (node (ref "X1202") (pin "4") (pinfunction "4_4") (pintype "passive"))
      (node (ref "X1203") (pin "4") (pinfunction "4_4") (pintype "passive"))
    )
    (net (code "21") (name "CONTACTOR_6_COIL_POS") (class "Default")
      (node (ref "D1001") (pin "C") (pinfunction "C_C") (pintype "passive"))
      (node (ref "IC1001") (pin "5") (pinfunction "5_5") (pintype "bidirectional"))
      (node (ref "X1201") (pin "3") (pinfunction "3_3") (pintype "passive"))
    )
    (net (code "22") (name "CONTACTOR_6_CONTROL") (class "Default")
      (node (ref "JP2201") (pin "18") (pinfunction "18_18") (pintype "passive"))
      (node (ref "LSP1001") (pin "P$1") (pinfunction "MP_P$1") (pintype "passive"))
      (node (ref "R1001") (pin "2") (pinfunction "2_2") (pintype "passive"))
    )
    (net (code "23") (name "CONTACTOR_6_FEEDBACK") (class "Default")
      (node (ref "IC1102") (pin "14") (pinfunction "VOA_14") (pintype "bidirectional"))
      (node (ref "JP2201") (pin "17") (pinfunction "17_17") (pintype "passive"))
      (node (ref "LSP1101") (pin "P$1") (pinfunction "MP_P$1") (pintype "passive"))
    )
    (net (code "24") (name "CONTACTOR_6_FEEDBACK_EXT") (class "Default")
      (node (ref "R1101") (pin "2") (pinfunction "2_2") (pintype "passive"))
      (node (ref "X1201") (pin "2") (pinfunction "2_2") (pintype "passive"))
    )
    (net (code "25") (name "CONTACTOR_7_COIL_POS") (class "Default")
      (node (ref "D1002") (pin "C") (pinfunction "C_C") (pintype "passive"))
      (node (ref "IC1002") (pin "5") (pinfunction "5_5") (pintype "bidirectional"))
      (node (ref "X1202") (pin "3") (pinfunction "3_3") (pintype "passive"))
    )
    (net (code "26") (name "CONTACTOR_7_CONTROL") (class "Default")
      (node (ref "JP2201") (pin "16") (pinfunction "16_16") (pintype "passive"))
      (node (ref "LSP1002") (pin "P$1") (pinfunction "MP_P$1") (pintype "passive"))
      (node (ref "R1004") (pin "2") (pinfunction "2_2") (pintype "passive"))
    )
    (net (code "27") (name "CONTACTOR_7_FEEDBACK") (class "Default")
      (node (ref "IC1102") (pin "13") (pinfunction "VOB_13") (pintype "bidirectional"))
      (node (ref "JP2201") (pin "15") (pinfunction "15_15") (pintype "passive"))
      (node (ref "LSP1103") (pin "P$1") (pinfunction "MP_P$1") (pintype "passive"))
    )
    (net (code "28") (name "CONTACTOR_7_FEEDBACK_EXT") (class "Default")
      (node (ref "R1102") (pin "2") (pinfunction "2_2") (pintype "passive"))
      (node (ref "X1202") (pin "2") (pinfunction "2_2") (pintype "passive"))
    )
    (net (code "29") (name "CONTACTOR_8_COIL_POS") (class "Default")
      (node (ref "D1003") (pin "C") (pinfunction "C_C") (pintype "passive"))
      (node (ref "IC1003") (pin "5") (pinfunction "5_5") (pintype "bidirectional"))
      (node (ref "X1203") (pin "3") (pinfunction "3_3") (pintype "passive"))
    )
    (net (code "30") (name "CONTACTOR_8_CONTROL") (class "Default")
      (node (ref "JP2202") (pin "10") (pinfunction "10_10") (pintype "passive"))
      (node (ref "LSP1003") (pin "P$1") (pinfunction "MP_P$1") (pintype "passive"))
      (node (ref "R1007") (pin "2") (pinfunction "2_2") (pintype "passive"))
    )
    (net (code "31") (name "CONTACTOR_8_FEEDBACK") (class "Default")
      (node (ref "IC1102") (pin "12") (pinfunction "VOC_12") (pintype "bidirectional"))
      (node (ref "JP2202") (pin "11") (pinfunction "11_11") (pintype "passive"))
      (node (ref "LSP1102") (pin "P$1") (pinfunction "MP_P$1") (pintype "passive"))
    )
    (net (code "32") (name "CONTACTOR_8_FEEDBACK_EXT") (class "Default")
      (node (ref "R1103") (pin "2") (pinfunction "2_2") (pintype "passive"))
      (node (ref "X1203") (pin "2") (pinfunction "2_2") (pintype "passive"))
    )
    (net (code "33") (name "CONTACTOR_FEEDBACK_SUPPLY_EXT") (class "Default")
      (node (ref "C1103") (pin "1") (pinfunction "1_1") (pintype "passive"))
      (node (ref "C1104") (pin "1") (pinfunction "1_1") (pintype "passive"))
      (node (ref "IC1101") (pin "1") (pinfunction "OUT_1") (pintype "output"))
      (node (ref "IC1102") (pin "1") (pinfunction "VDD1_1") (pintype "power_in"))
      (node (ref "R1104") (pin "2") (pinfunction "2_2") (pintype "passive"))
      (node (ref "R1105") (pin "2") (pinfunction "2_2") (pintype "passive"))
      (node (ref "R1106") (pin "2") (pinfunction "2_2") (pintype "passive"))
    )
    (net (code "34") (name "DATA_STORAGE_SPI_MISO") (class "Default")
      (node (ref "JP2201") (pin "21") (pinfunction "21_21") (pintype "passive"))
      (node (ref "LSP1505") (pin "P$1") (pinfunction "MP_P$1") (pintype "passive"))
      (node (ref "R1507") (pin "1") (pinfunction "1_1") (pintype "passive"))
      (node (ref "SLOT1501") (pin "7") (pinfunction "7_7") (pintype "passive"))
    )
    (net (code "35") (name "DATA_STORAGE_SPI_MOSI") (class "Default")
      (node (ref "JP2201") (pin "19") (pinfunction "19_19") (pintype "passive"))
      (node (ref "LSP1503") (pin "P$1") (pinfunction "MP_P$1") (pintype "passive"))
      (node (ref "R1504") (pin "1") (pinfunction "1_1") (pintype "passive"))
      (node (ref "SLOT1501") (pin "3") (pinfunction "3_3") (pintype "passive"))
    )
    (net (code "36") (name "DATA_STORAGE_SPI_SCK") (class "Default")
      (node (ref "JP2201") (pin "20") (pinfunction "20_20") (pintype "passive"))
      (node (ref "LSP1504") (pin "P$1") (pinfunction "MP_P$1") (pintype "passive"))
      (node (ref "R1505") (pin "2") (pinfunction "2_2") (pintype "passive"))
      (node (ref "SLOT1501") (pin "5") (pinfunction "5_5") (pintype "passive"))
    )
    (net (code "37") (name "DATA_STORAGE_SPI_SDCARD_NSS") (class "Default")
      (node (ref "JP2201") (pin "23") (pinfunction "23_23") (pintype "passive"))
      (node (ref "LSP1502") (pin "P$1") (pinfunction "MP_P$1") (pintype "passive"))
      (node (ref "R1506") (pin "1") (pinfunction "1_1") (pintype "passive"))
      (node (ref "SLOT1501") (pin "2") (pinfunction "2_2") (pintype "passive"))
    )
    (net (code "38") (name "GND_0") (class "Default")
      (node (ref "C1105") (pin "2") (pinfunction "2_2") (pintype "passive"))
      (node (ref "C1106") (pin "2") (pinfunction "2_2") (pintype "passive"))
      (node (ref "C1306") (pin "2") (pinfunction "2_2") (pintype "passive"))
      (node (ref "C1501") (pin "1") (pinfunction "1_1") (pintype "passive"))
      (node (ref "C1502") (pin "2") (pinfunction "2_2") (pintype "passive"))
      (node (ref "C1701") (pin "2") (pinfunction "2_2") (pintype "passive"))
      (node (ref "C1702") (pin "2") (pinfunction "2_2") (pintype "passive"))
      (node (ref "C1703") (pin "2") (pinfunction "2_2") (pintype "passive"))
      (node (ref "C1704") (pin "2") (pinfunction "2_2") (pintype "passive"))
      (node (ref "C1705") (pin "2") (pinfunction "2_2") (pintype "passive"))
      (node (ref "C1706") (pin "2") (pinfunction "2_2") (pintype "passive"))
      (node (ref "C1707") (pin "2") (pinfunction "2_2") (pintype "passive"))
      (node (ref "C1708") (pin "2") (pinfunction "2_2") (pintype "passive"))
      (node (ref "C1905") (pin "2") (pinfunction "2_2") (pintype "passive"))
      (node (ref "C1907") (pin "2") (pinfunction "2_2") (pintype "passive"))
      (node (ref "C807") (pin "1") (pinfunction "1_1") (pintype "passive"))
      (node (ref "D1701") (pin "A") (pinfunction "A_A") (pintype "bidirectional"))
      (node (ref "D1702") (pin "A") (pinfunction "A_A") (pintype "bidirectional"))
      (node (ref "D1703") (pin "A") (pinfunction "A_A") (pintype "bidirectional"))
      (node (ref "D1704") (pin "A") (pinfunction "A_A") (pintype "bidirectional"))
      (node (ref "D1705") (pin "A") (pinfunction "A_A") (pintype "bidirectional"))
      (node (ref "IC1102") (pin "15") (pinfunction "GND2_15") (pintype "power_in"))
      (node (ref "IC1102") (pin "9") (pinfunction "GND2_9") (pintype "power_in"))
      (node (ref "IC1303") (pin "2") (pinfunction "GND1_2") (pintype "power_in"))
      (node (ref "IC1303") (pin "8") (pinfunction "GND1_8") (pintype "power_in"))
      (node (ref "IC1701") (pin "1") (pinfunction "GND_FORCE_1") (pintype "power_in"))
      (node (ref "IC1701") (pin "2") (pinfunction "GND_SENSE_2") (pintype "power_in"))
      (node (ref "IC1902") (pin "15") (pinfunction "GND2_15") (pintype "power_in"))
      (node (ref "IC1902") (pin "9") (pinfunction "GND2_9") (pintype "power_in"))
      (node (ref "IC1903") (pin "15") (pinfunction "GND2_15") (pintype "power_in"))
      (node (ref "IC1903") (pin "9") (pinfunction "GND2_9") (pintype "power_in"))
      (node (ref "IC803") (pin "2") (pinfunction "GND_2") (pintype "power_in"))
      (node (ref "IC803") (pin "7") (pinfunction "GND_7") (pintype "power_in"))
      (node (ref "IC803") (pin "8") (pinfunction "GND_8") (pintype "power_in"))
      (node (ref "JP2201") (pin "2") (pinfunction "2_2") (pintype "passive"))
      (node (ref "JP2201") (pin "4") (pinfunction "4_4") (pintype "passive"))
      (node (ref "JP2202") (pin "2") (pinfunction "2_2") (pintype "passive"))
      (node (ref "JP2202") (pin "4") (pinfunction "4_4") (pintype "passive"))
      (node (ref "LSP2102") (pin "P$1") (pinfunction "MP_P$1") (pintype "passive"))
      (node (ref "R1002") (pin "1") (pinfunction "1_1") (pintype "passive"))
      (node (ref "R1005") (pin "1") (pinfunction "1_1") (pintype "passive"))
      (node (ref "R1008") (pin "1") (pinfunction "1_1") (pintype "passive"))
      (node (ref "R1505") (pin "1") (pinfunction "1_1") (pintype "passive"))
      (node (ref "R1702") (pin "2") (pinfunction "2_2") (pintype "passive"))
      (node (ref "R1704") (pin "2") (pinfunction "2_2") (pintype "passive"))
      (node (ref "R1706") (pin "2") (pinfunction "2_2") (pintype "passive"))
      (node (ref "R1708") (pin "2") (pinfunction "2_2") (pintype "passive"))
      (node (ref "R1710") (pin "2") (pinfunction "2_2") (pintype "passive"))
      (node (ref "R2003") (pin "1") (pinfunction "1_1") (pintype "passive"))
      (node (ref "R2004") (pin "1") (pinfunction "1_1") (pintype "passive"))
      (node (ref "R2009") (pin "1") (pinfunction "1_1") (pintype "passive"))
      (node (ref "R2010") (pin "1") (pinfunction "1_1") (pintype "passive"))
      (node (ref "R2015") (pin "1") (pinfunction "1_1") (pintype "passive"))
      (node (ref "R2016") (pin "1") (pinfunction "1_1") (pintype "passive"))
      (node (ref "R805") (pin "2") (pinfunction "2_2") (pintype "passive"))
      (node (ref "SLOT1501") (pin "6") (pinfunction "6_6") (pintype "passive"))
      (node (ref "SLOT1501") (pin "6_1") (pinfunction "9_6_1") (pintype "passive"))
      (node (ref "SLOT1501") (pin "SH1") (pinfunction "SH_SH1") (pintype "passive"))
      (node (ref "SLOT1501") (pin "SH2") (pinfunction "SH_SH2") (pintype "passive"))
      (node (ref "SLOT1501") (pin "SH3") (pinfunction "SH_SH3") (pintype "passive"))
      (node (ref "SLOT1501") (pin "SH5") (pinfunction "SH_SH5") (pintype "passive"))
      (node (ref "SV2101") (pin "5") (pinfunction "5_5") (pintype "passive"))
      (node (ref "SV2101") (pin "6") (pinfunction "6_6") (pintype "passive"))
      (node (ref "T1001") (pin "2") (pinfunction "S_2") (pintype "passive"))
      (node (ref "T1002") (pin "2") (pinfunction "S_2") (pintype "passive"))
      (node (ref "T1003") (pin "2") (pinfunction "S_2") (pintype "passive"))
      (node (ref "T2001") (pin "2") (pinfunction "S_2") (pintype "passive"))
      (node (ref "T2002") (pin "2") (pinfunction "S_2") (pintype "passive"))
      (node (ref "T2003") (pin "2") (pinfunction "S_2") (pintype "passive"))
      (node (ref "T2004") (pin "2") (pinfunction "S_2") (pintype "passive"))
      (node (ref "T2005") (pin "2") (pinfunction "S_2") (pintype "passive"))
      (node (ref "T2006") (pin "2") (pinfunction "S_2") (pintype "passive"))
      (node (ref "T801") (pin "2") (pinfunction "S_2") (pintype "passive"))
      (node (ref "X1701") (pin "11") (pinfunction "11_11") (pintype "passive"))
      (node (ref "X1701") (pin "12") (pinfunction "12_12") (pintype "passive"))
    )
    (net (code "39") (name "GND_EXT_0") (class "Default")
      (node (ref "C1101") (pin "2") (pinfunction "2_2") (pintype "passive"))
      (node (ref "C1102") (pin "2") (pinfunction "2_2") (pintype "passive"))
      (node (ref "C1103") (pin "2") (pinfunction "2_2") (pintype "passive"))
      (node (ref "C1104") (pin "2") (pinfunction "2_2") (pintype "passive"))
      (node (ref "C1901") (pin "2") (pinfunction "2_2") (pintype "passive"))
      (node (ref "C1902") (pin "2") (pinfunction "2_2") (pintype "passive"))
      (node (ref "C1903") (pin "2") (pinfunction "2_2") (pintype "passive"))
      (node (ref "C1904") (pin "2") (pinfunction "2_2") (pintype "passive"))
      (node (ref "C1906") (pin "2") (pinfunction "2_2") (pintype "passive"))
      (node (ref "D1101") (pin "A") (pinfunction "A_A") (pintype "passive"))
      (node (ref "D1102") (pin "A") (pinfunction "A_A") (pintype "passive"))
      (node (ref "D1103") (pin "A") (pinfunction "A_A") (pintype "passive"))
      (node (ref "D1901") (pin "A") (pinfunction "A_A") (pintype "passive"))
      (node (ref "D1902") (pin "A") (pinfunction "A_A") (pintype "passive"))
      (node (ref "D1903") (pin "A") (pinfunction "A_A") (pintype "passive"))
      (node (ref "D1904") (pin "A") (pinfunction "A_A") (pintype "passive"))
      (node (ref "IC1101") (pin "2") (pinfunction "COM_2") (pintype "power_in"))
      (node (ref "IC1102") (pin "2") (pinfunction "GND1_2") (pintype "power_in"))
      (node (ref "IC1102") (pin "8") (pinfunction "GND1_8") (pintype "power_in"))
      (node (ref "IC1901") (pin "2") (pinfunction "COM_2") (pintype "power_in"))
      (node (ref "IC1902") (pin "2") (pinfunction "GND1_2") (pintype "power_in"))
      (node (ref "IC1902") (pin "8") (pinfunction "GND1_8") (pintype "power_in"))
      (node (ref "IC1903") (pin "2") (pinfunction "GND1_2") (pintype "power_in"))
      (node (ref "IC1903") (pin "8") (pinfunction "GND1_8") (pintype "power_in"))
      (node (ref "R1903") (pin "1") (pinfunction "1_1") (pintype "passive"))
      (node (ref "R1904") (pin "1") (pinfunction "1_1") (pintype "passive"))
      (node (ref "R1907") (pin "1") (pinfunction "1_1") (pintype "passive"))
      (node (ref "R1908") (pin "1") (pinfunction "1_1") (pintype "passive"))
      (node (ref "SV901") (pin "2") (pinfunction "2_2") (pintype "passive"))
      (node (ref "X1201") (pin "1") (pinfunction "1_1") (pintype "passive"))
      (node (ref "X1202") (pin "1") (pinfunction "1_1") (pintype "passive"))
      (node (ref "X1203") (pin "1") (pinfunction "1_1") (pintype "passive"))
      (node (ref "X1901") (pin "10") (pinfunction "10_10") (pintype "passive"))
      (node (ref "X1901") (pin "9") (pinfunction "9_9") (pintype "passive"))
    )
    (net (code "40") (name "GND_EXT_1") (class "Default")
      (node (ref "C801") (pin "1") (pinfunction "1_1") (pintype "passive"))
      (node (ref "C802") (pin "1") (pinfunction "1_1") (pintype "passive"))
      (node (ref "C803") (pin "1") (pinfunction "1_1") (pintype "passive"))
      (node (ref "C804") (pin "2") (pinfunction "2_2") (pintype "passive"))
      (node (ref "C805") (pin "1") (pinfunction "1_1") (pintype "passive"))
      (node (ref "C806") (pin "1") (pinfunction "1_1") (pintype "passive"))
      (node (ref "D801") (pin "3") (pinfunction "3_3") (pintype "passive"))
      (node (ref "IC801") (pin "2") (pinfunction "GND_2") (pintype "power_in"))
      (node (ref "IC802") (pin "3") (pinfunction "3_3") (pintype "bidirectional"))
      (node (ref "IC803") (pin "10") (pinfunction "GND_10") (pintype "power_in"))
      (node (ref "IC803") (pin "15") (pinfunction "GND_15") (pintype "power_in"))
      (node (ref "IC803") (pin "9") (pinfunction "GND_9") (pintype "power_in"))
      (node (ref "LSP801") (pin "P$1") (pinfunction "MP_P$1") (pintype "passive"))
      (node (ref "X801") (pin "1") (pinfunction "1_1") (pintype "passive"))
    )
    (net (code "41") (name "GND_EXT_2") (class "Default")
      (node (ref "C1301") (pin "2") (pinfunction "2_2") (pintype "passive"))
      (node (ref "C1302") (pin "2") (pinfunction "2_2") (pintype "passive"))
      (node (ref "C1303") (pin "2") (pinfunction "2_2") (pintype "passive"))
      (node (ref "C1304") (pin "2") (pinfunction "2_2") (pintype "passive"))
      (node (ref "C1305") (pin "2") (pinfunction "2_2") (pintype "passive"))
      (node (ref "IC1301") (pin "2") (pinfunction "COM_2") (pintype "power_in"))
      (node (ref "IC1302") (pin "5") (pinfunction "GND_5") (pintype "power_in"))
      (node (ref "IC1303") (pin "15") (pinfunction "GND2_15") (pintype "power_in"))
      (node (ref "IC1303") (pin "9") (pinfunction "GND2_9") (pintype "power_in"))
      (node (ref "R901") (pin "2") (pinfunction "2_2") (pintype "passive"))
      (node (ref "SV901") (pin "4") (pinfunction "4_4") (pintype "passive"))
      (node (ref "SV901") (pin "6") (pinfunction "6_6") (pintype "passive"))
      (node (ref "SV901") (pin "8") (pinfunction "8_8") (pintype "passive"))
      (node (ref "T901") (pin "3") (pinfunction "S_3") (pintype "passive"))
      (node (ref "X1301") (pin "1") (pinfunction "1_1") (pintype "passive"))
      (node (ref "X1301") (pin "6") (pinfunction "6_6") (pintype "passive"))
    )
    (net (code "42") (name "INTERLOCK_STATUS") (class "Default")
      (node (ref "LSP901") (pin "P$1") (pinfunction "MP_P$1") (pintype "passive"))
      (node (ref "R902") (pin "2") (pinfunction "2_2") (pintype "passive"))
      (node (ref "SV901") (pin "1") (pinfunction "1_1") (pintype "passive"))
    )
    (net (code "43") (name "ISONOC_0_CONTROL") (class "Default")
      (node (ref "JP2202") (pin "16") (pinfunction "16_16") (pintype "passive"))
      (node (ref "LSP2001") (pin "P$1") (pinfunction "MP_P$1") (pintype "passive"))
      (node (ref "R2001") (pin "2") (pinfunction "2_2") (pintype "passive"))
    )
    (net (code "44") (name "ISONOC_0_NEGATIVE") (class "Default")
      (node (ref "D2001") (pin "A") (pinfunction "A_A") (pintype "passive"))
      (node (ref "IC2001") (pin "5") (pinfunction "S_5") (pintype "passive"))
      (node (ref "X2001") (pin "7") (pinfunction "7_7") (pintype "passive"))
    )
    (net (code "45") (name "ISONOC_0_POSITIVE") (class "Default")
      (node (ref "D2001") (pin "C") (pinfunction "C_C") (pintype "passive"))
      (node (ref "IC2001") (pin "4") (pinfunction "D1_4") (pintype "passive"))
      (node (ref "IC2001") (pin "6") (pinfunction "D2_6") (pintype "passive"))
      (node (ref "X2001") (pin "1") (pinfunction "1_1") (pintype "passive"))
    )
    (net (code "46") (name "ISONOC_1_CONTROL") (class "Default")
      (node (ref "JP2202") (pin "17") (pinfunction "17_17") (pintype "passive"))
      (node (ref "LSP2003") (pin "P$1") (pinfunction "MP_P$1") (pintype "passive"))
      (node (ref "R2007") (pin "2") (pinfunction "2_2") (pintype "passive"))
    )
    (net (code "47") (name "ISONOC_1_NEGATIVE") (class "Default")
      (node (ref "D2003") (pin "A") (pinfunction "A_A") (pintype "passive"))
      (node (ref "IC2003") (pin "5") (pinfunction "S_5") (pintype "passive"))
      (node (ref "X2001") (pin "8") (pinfunction "8_8") (pintype "passive"))
    )
    (net (code "48") (name "ISONOC_1_POSITIVE") (class "Default")
      (node (ref "D2003") (pin "C") (pinfunction "C_C") (pintype "passive"))
      (node (ref "IC2003") (pin "4") (pinfunction "D1_4") (pintype "passive"))
      (node (ref "IC2003") (pin "6") (pinfunction "D2_6") (pintype "passive"))
      (node (ref "X2001") (pin "2") (pinfunction "2_2") (pintype "passive"))
    )
    (net (code "49") (name "ISONOC_2_CONTROL") (class "Default")
      (node (ref "JP2202") (pin "18") (pinfunction "18_18") (pintype "passive"))
      (node (ref "LSP2005") (pin "P$1") (pinfunction "MP_P$1") (pintype "passive"))
      (node (ref "R2013") (pin "2") (pinfunction "2_2") (pintype "passive"))
    )
    (net (code "50") (name "ISONOC_2_NEGATIVE") (class "Default")
      (node (ref "D2005") (pin "A") (pinfunction "A_A") (pintype "passive"))
      (node (ref "IC2005") (pin "5") (pinfunction "S_5") (pintype "passive"))
      (node (ref "X2001") (pin "9") (pinfunction "9_9") (pintype "passive"))
    )
    (net (code "51") (name "ISONOC_2_POSITIVE") (class "Default")
      (node (ref "D2005") (pin "C") (pinfunction "C_C") (pintype "passive"))
      (node (ref "IC2005") (pin "4") (pinfunction "D1_4") (pintype "passive"))
      (node (ref "IC2005") (pin "6") (pinfunction "D2_6") (pintype "passive"))
      (node (ref "X2001") (pin "3") (pinfunction "3_3") (pintype "passive"))
    )
    (net (code "52") (name "ISONOC_3_CONTROL") (class "Default")
      (node (ref "JP2202") (pin "19") (pinfunction "19_19") (pintype "passive"))
      (node (ref "LSP2002") (pin "P$1") (pinfunction "MP_P$1") (pintype "passive"))
      (node (ref "R2002") (pin "2") (pinfunction "2_2") (pintype "passive"))
    )
    (net (code "53") (name "ISONOC_3_NEGATIVE") (class "Default")
      (node (ref "D2002") (pin "A") (pinfunction "A_A") (pintype "passive"))
      (node (ref "IC2002") (pin "5") (pinfunction "S_5") (pintype "passive"))
      (node (ref "X2001") (pin "10") (pinfunction "10_10") (pintype "passive"))
    )
    (net (code "54") (name "ISONOC_3_POSITIVE") (class "Default")
      (node (ref "D2002") (pin "C") (pinfunction "C_C") (pintype "passive"))
      (node (ref "IC2002") (pin "4") (pinfunction "D1_4") (pintype "passive"))
      (node (ref "IC2002") (pin "6") (pinfunction "D2_6") (pintype "passive"))
      (node (ref "X2001") (pin "4") (pinfunction "4_4") (pintype "passive"))
    )
    (net (code "55") (name "ISONOC_4_CONTROL") (class "Default")
      (node (ref "JP2202") (pin "20") (pinfunction "20_20") (pintype "passive"))
      (node (ref "LSP2004") (pin "P$1") (pinfunction "MP_P$1") (pintype "passive"))
      (node (ref "R2008") (pin "2") (pinfunction "2_2") (pintype "passive"))
    )
    (net (code "56") (name "ISONOC_4_NEGATIVE") (class "Default")
      (node (ref "D2004") (pin "A") (pinfunction "A_A") (pintype "passive"))
      (node (ref "IC2004") (pin "5") (pinfunction "S_5") (pintype "passive"))
      (node (ref "X2001") (pin "11") (pinfunction "11_11") (pintype "passive"))
    )
    (net (code "57") (name "ISONOC_4_POSITIVE") (class "Default")
      (node (ref "D2004") (pin "C") (pinfunction "C_C") (pintype "passive"))
      (node (ref "IC2004") (pin "4") (pinfunction "D1_4") (pintype "passive"))
      (node (ref "IC2004") (pin "6") (pinfunction "D2_6") (pintype "passive"))
      (node (ref "X2001") (pin "5") (pinfunction "5_5") (pintype "passive"))
    )
    (net (code "58") (name "ISONOC_5_CONTROL") (class "Default")
      (node (ref "JP2202") (pin "21") (pinfunction "21_21") (pintype "passive"))
      (node (ref "LSP2006") (pin "P$1") (pinfunction "MP_P$1") (pintype "passive"))
      (node (ref "R2014") (pin "2") (pinfunction "2_2") (pintype "passive"))
    )
    (net (code "59") (name "ISONOC_5_NEGATIVE") (class "Default")
      (node (ref "D2006") (pin "A") (pinfunction "A_A") (pintype "passive"))
      (node (ref "IC2006") (pin "5") (pinfunction "S_5") (pintype "passive"))
      (node (ref "X2001") (pin "12") (pinfunction "12_12") (pintype "passive"))
    )
    (net (code "60") (name "ISONOC_5_POSITIVE") (class "Default")
      (node (ref "D2006") (pin "C") (pinfunction "C_C") (pintype "passive"))
      (node (ref "IC2006") (pin "4") (pinfunction "D1_4") (pintype "passive"))
      (node (ref "IC2006") (pin "6") (pinfunction "D2_6") (pintype "passive"))
      (node (ref "X2001") (pin "6") (pinfunction "6_6") (pintype "passive"))
    )
    (net (code "61") (name "ISO_GPIO_MCU_0_IN_0") (class "Default")
      (node (ref "IC1902") (pin "14") (pinfunction "VOA_14") (pintype "bidirectional"))
      (node (ref "JP2202") (pin "22") (pinfunction "22_22") (pintype "passive"))
      (node (ref "LSP1903") (pin "P$1") (pinfunction "MP_P$1") (pintype "passive"))
    )
    (net (code "62") (name "ISO_GPIO_MCU_0_IN_0_EXT") (class "Default")
      (node (ref "R1901") (pin "2") (pinfunction "2_2") (pintype "passive"))
      (node (ref "X1901") (pin "5") (pinfunction "5_5") (pintype "passive"))
    )
    (net (code "63") (name "ISO_GPIO_MCU_0_IN_1") (class "Default")
      (node (ref "IC1902") (pin "13") (pinfunction "VOB_13") (pintype "bidirectional"))
      (node (ref "JP2202") (pin "23") (pinfunction "23_23") (pintype "passive"))
      (node (ref "LSP1901") (pin "P$1") (pinfunction "MP_P$1") (pintype "passive"))
    )
    (net (code "64") (name "ISO_GPIO_MCU_0_IN_1_EXT") (class "Default")
      (node (ref "R1902") (pin "2") (pinfunction "2_2") (pintype "passive"))
      (node (ref "X1901") (pin "6") (pinfunction "6_6") (pintype "passive"))
    )
    (net (code "65") (name "ISO_GPIO_MCU_0_IN_2") (class "Default")
      (node (ref "IC1903") (pin "14") (pinfunction "VOA_14") (pintype "bidirectional"))
      (node (ref "JP2201") (pin "13") (pinfunction "13_13") (pintype "passive"))
      (node (ref "LSP1905") (pin "P$1") (pinfunction "MP_P$1") (pintype "passive"))
    )
    (net (code "66") (name "ISO_GPIO_MCU_0_IN_2_EXT") (class "Default")
      (node (ref "R1905") (pin "2") (pinfunction "2_2") (pintype "passive"))
      (node (ref "X1901") (pin "7") (pinfunction "7_7") (pintype "passive"))
    )
    (net (code "67") (name "ISO_GPIO_MCU_0_IN_3") (class "Default")
      (node (ref "IC1903") (pin "13") (pinfunction "VOB_13") (pintype "bidirectional"))
      (node (ref "JP2201") (pin "10") (pinfunction "10_10") (pintype "passive"))
      (node (ref "LSP1907") (pin "P$1") (pinfunction "MP_P$1") (pintype "passive"))
    )
    (net (code "68") (name "ISO_GPIO_MCU_0_IN_3_EXT") (class "Default")
      (node (ref "R1906") (pin "2") (pinfunction "2_2") (pintype "passive"))
      (node (ref "X1901") (pin "8") (pinfunction "8_8") (pintype "passive"))
    )
    (net (code "69") (name "ISO_GPIO_MCU_0_OUT_0") (class "Default")
      (node (ref "IC1902") (pin "12") (pinfunction "VIC_12") (pintype "bidirectional"))
      (node (ref "JP2201") (pin "9") (pinfunction "9_9") (pintype "passive"))
      (node (ref "LSP1904") (pin "P$1") (pinfunction "MP_P$1") (pintype "passive"))
    )
    (net (code "70") (name "ISO_GPIO_MCU_0_OUT_0_EXT") (class "Default")
      (node (ref "IC1902") (pin "5") (pinfunction "VOC_5") (pintype "bidirectional"))
      (node (ref "R1903") (pin "2") (pinfunction "2_2") (pintype "passive"))
      (node (ref "X1901") (pin "1") (pinfunction "1_1") (pintype "passive"))
    )
    (net (code "71") (name "ISO_GPIO_MCU_0_OUT_1") (class "Default")
      (node (ref "IC1902") (pin "11") (pinfunction "VID_11") (pintype "bidirectional"))
      (node (ref "JP2201") (pin "14") (pinfunction "14_14") (pintype "passive"))
      (node (ref "LSP1902") (pin "P$1") (pinfunction "MP_P$1") (pintype "passive"))
    )
    (net (code "72") (name "ISO_GPIO_MCU_0_OUT_1_EXT") (class "Default")
      (node (ref "IC1902") (pin "6") (pinfunction "VOD_6") (pintype "bidirectional"))
      (node (ref "R1904") (pin "2") (pinfunction "2_2") (pintype "passive"))
      (node (ref "X1901") (pin "2") (pinfunction "2_2") (pintype "passive"))
    )
    (net (code "73") (name "ISO_GPIO_MCU_0_OUT_2") (class "Default")
      (node (ref "IC1903") (pin "12") (pinfunction "VIC_12") (pintype "bidirectional"))
      (node (ref "JP2201") (pin "11") (pinfunction "11_11") (pintype "passive"))
      (node (ref "LSP1906") (pin "P$1") (pinfunction "MP_P$1") (pintype "passive"))
    )
    (net (code "74") (name "ISO_GPIO_MCU_0_OUT_2_EXT") (class "Default")
      (node (ref "IC1903") (pin "5") (pinfunction "VOC_5") (pintype "bidirectional"))
      (node (ref "R1907") (pin "2") (pinfunction "2_2") (pintype "passive"))
      (node (ref "X1901") (pin "3") (pinfunction "3_3") (pintype "passive"))
    )
    (net (code "75") (name "ISO_GPIO_MCU_0_OUT_3") (class "Default")
      (node (ref "IC1903") (pin "11") (pinfunction "VID_11") (pintype "bidirectional"))
      (node (ref "JP2201") (pin "12") (pinfunction "12_12") (pintype "passive"))
      (node (ref "LSP1908") (pin "P$1") (pinfunction "MP_P$1") (pintype "passive"))
    )
    (net (code "76") (name "ISO_GPIO_MCU_0_OUT_3_EXT") (class "Default")
      (node (ref "IC1903") (pin "6") (pinfunction "VOD_6") (pintype "bidirectional"))
      (node (ref "R1908") (pin "2") (pinfunction "2_2") (pintype "passive"))
      (node (ref "X1901") (pin "4") (pinfunction "4_4") (pintype "passive"))
    )
    (net (code "77") (name "ISO_GPIO_SUPPLY") (class "Default")
      (node (ref "C1903") (pin "1") (pinfunction "1_1") (pintype "passive"))
      (node (ref "C1904") (pin "1") (pinfunction "1_1") (pintype "passive"))
      (node (ref "C1906") (pin "1") (pinfunction "1_1") (pintype "passive"))
      (node (ref "IC1901") (pin "1") (pinfunction "OUT_1") (pintype "output"))
      (node (ref "IC1902") (pin "1") (pinfunction "VDD1_1") (pintype "power_in"))
      (node (ref "IC1902") (pin "7") (pinfunction "VE1_7") (pintype "bidirectional"))
      (node (ref "IC1903") (pin "1") (pinfunction "VDD1_1") (pintype "power_in"))
      (node (ref "IC1903") (pin "7") (pinfunction "VE1_7") (pintype "bidirectional"))
    )
    (net (code "78") (name "MCU_TO_FPGA_INTERFACE_MCU_0_CS") (class "Default")
      (node (ref "SV2101") (pin "8") (pinfunction "8_8") (pintype "passive"))
    )
    (net (code "79") (name "MCU_TO_FPGA_INTERFACE_MCU_0_MISO") (class "Default")
      (node (ref "SV2101") (pin "3") (pinfunction "3_3") (pintype "passive"))
    )
    (net (code "80") (name "MCU_TO_FPGA_INTERFACE_MCU_0_MOSI") (class "Default")
      (node (ref "SV2101") (pin "7") (pinfunction "7_7") (pintype "passive"))
    )
    (net (code "81") (name "MCU_TO_FPGA_INTERFACE_MCU_0_SCK") (class "Default")
      (node (ref "SV2101") (pin "4") (pinfunction "4_4") (pintype "passive"))
    )
    (net (code "82") (name "Net-(C804-Pad1)") (class "Default")
      (node (ref "C804") (pin "1") (pinfunction "1_1") (pintype "passive"))
      (node (ref "R801") (pin "2") (pinfunction "2_2") (pintype "passive"))
      (node (ref "R802") (pin "1") (pinfunction "1_1") (pintype "passive"))
    )
    (net (code "83") (name "Net-(F1001-Pad1)") (class "Default")
      (node (ref "F1001") (pin "1") (pinfunction "1_1") (pintype "bidirectional"))
      (node (ref "IC1001") (pin "4") (pinfunction "4_4") (pintype "bidirectional"))
      (node (ref "IC1001") (pin "6") (pinfunction "6_6") (pintype "bidirectional"))
    )
    (net (code "84") (name "Net-(F1002-Pad1)") (class "Default")
      (node (ref "F1002") (pin "1") (pinfunction "1_1") (pintype "bidirectional"))
      (node (ref "IC1002") (pin "4") (pinfunction "4_4") (pintype "bidirectional"))
      (node (ref "IC1002") (pin "6") (pinfunction "6_6") (pintype "bidirectional"))
    )
    (net (code "85") (name "Net-(F1003-Pad1)") (class "Default")
      (node (ref "F1003") (pin "1") (pinfunction "1_1") (pintype "bidirectional"))
      (node (ref "IC1003") (pin "4") (pinfunction "4_4") (pintype "bidirectional"))
      (node (ref "IC1003") (pin "6") (pinfunction "6_6") (pintype "bidirectional"))
    )
    (net (code "86") (name "Net-(IC802-CON+)") (class "Default")
      (node (ref "IC802") (pin "1") (pinfunction "CON+_1") (pintype "bidirectional"))
      (node (ref "R804") (pin "2") (pinfunction "2_2") (pintype "passive"))
    )
    (net (code "87") (name "Net-(IC802-CON-)") (class "Default")
      (node (ref "IC802") (pin "2") (pinfunction "CON-_2") (pintype "bidirectional"))
      (node (ref "T801") (pin "3") (pinfunction "D_3") (pintype "passive"))
    )
    (net (code "88") (name "Net-(IC803A-CANH)") (class "Default")
      (node (ref "IC803") (pin "13") (pinfunction "CANH_13") (pintype "bidirectional"))
      (node (ref "L801") (pin "3") (pinfunction "3_3") (pintype "passive"))
      (node (ref "R802") (pin "2") (pinfunction "2_2") (pintype "passive"))
    )
    (net (code "89") (name "Net-(IC803A-CANL)") (class "Default")
      (node (ref "IC803") (pin "12") (pinfunction "CANL_12") (pintype "bidirectional"))
      (node (ref "L801") (pin "4") (pinfunction "4_4") (pintype "passive"))
      (node (ref "R801") (pin "1") (pinfunction "1_1") (pintype "passive"))
    )
    (net (code "90") (name "Net-(IC1001-Pad2)") (class "Default")
      (node (ref "IC1001") (pin "2") (pinfunction "2_2") (pintype "bidirectional"))
      (node (ref "R1003") (pin "2") (pinfunction "2_2") (pintype "passive"))
    )
    (net (code "91") (name "Net-(IC1002-Pad2)") (class "Default")
      (node (ref "IC1002") (pin "2") (pinfunction "2_2") (pintype "bidirectional"))
      (node (ref "R1006") (pin "2") (pinfunction "2_2") (pintype "passive"))
    )
    (net (code "92") (name "Net-(IC1003-Pad2)") (class "Default")
      (node (ref "IC1003") (pin "2") (pinfunction "2_2") (pintype "bidirectional"))
      (node (ref "R1009") (pin "2") (pinfunction "2_2") (pintype "passive"))
    )
    (net (code "93") (name "Net-(IC1102A-VIA)") (class "Default")
      (node (ref "D1101") (pin "C") (pinfunction "C_C") (pintype "passive"))
      (node (ref "IC1102") (pin "3") (pinfunction "VIA_3") (pintype "bidirectional"))
      (node (ref "R1101") (pin "1") (pinfunction "1_1") (pintype "passive"))
      (node (ref "R1104") (pin "1") (pinfunction "1_1") (pintype "passive"))
    )
    (net (code "94") (name "Net-(IC1102A-VIB)") (class "Default")
      (node (ref "D1102") (pin "C") (pinfunction "C_C") (pintype "passive"))
      (node (ref "IC1102") (pin "4") (pinfunction "VIB_4") (pintype "bidirectional"))
      (node (ref "R1102") (pin "1") (pinfunction "1_1") (pintype "passive"))
      (node (ref "R1105") (pin "1") (pinfunction "1_1") (pintype "passive"))
    )
    (net (code "95") (name "Net-(IC1102A-VIC)") (class "Default")
      (node (ref "D1103") (pin "C") (pinfunction "C_C") (pintype "passive"))
      (node (ref "IC1102") (pin "5") (pinfunction "VIC_5") (pintype "bidirectional"))
      (node (ref "R1103") (pin "1") (pinfunction "1_1") (pintype "passive"))
      (node (ref "R1106") (pin "1") (pinfunction "1_1") (pintype "passive"))
    )
    (net (code "96") (name "Net-(IC1301-IN)") (class "Default")
      (node (ref "C1301") (pin "1") (pinfunction "1_1") (pintype "passive"))
      (node (ref "C1302") (pin "1") (pinfunction "1_1") (pintype "passive"))
      (node (ref "IC1301") (pin "3") (pinfunction "IN_3") (pintype "input"))
      (node (ref "X1301") (pin "4") (pinfunction "4_4") (pintype "passive"))
      (node (ref "X1301") (pin "5") (pinfunction "5_5") (pintype "passive"))
    )
    (net (code "97") (name "Net-(IC1301-OUT)") (class "Default")
      (node (ref "C1303") (pin "1") (pinfunction "1_1") (pintype "passive"))
      (node (ref "C1304") (pin "1") (pinfunction "1_1") (pintype "passive"))
      (node (ref "C1305") (pin "1") (pinfunction "1_1") (pintype "passive"))
      (node (ref "IC1301") (pin "1") (pinfunction "OUT_1") (pintype "output"))
      (node (ref "IC1302") (pin "8") (pinfunction "VCC_8") (pintype "power_in"))
      (node (ref "IC1303") (pin "10") (pinfunction "VE2_10") (pintype "bidirectional"))
      (node (ref "IC1303") (pin "16") (pinfunction "VDD2_16") (pintype "power_in"))
    )
    (net (code "98") (name "Net-(IC1302A-DE)") (class "Default")
      (node (ref "IC1302") (pin "3") (pinfunction "DE_3") (pintype "bidirectional"))
      (node (ref "IC1303") (pin "12") (pinfunction "VOC_12") (pintype "bidirectional"))
    )
    (net (code "99") (name "Net-(IC1302A-DI)") (class "Default")
      (node (ref "IC1302") (pin "4") (pinfunction "DI_4") (pintype "bidirectional"))
      (node (ref "IC1303") (pin "14") (pinfunction "VOA_14") (pintype "bidirectional"))
    )
    (net (code "100") (name "Net-(IC1302A-RO)") (class "Default")
      (node (ref "IC1302") (pin "1") (pinfunction "RO_1") (pintype "bidirectional"))
      (node (ref "IC1303") (pin "11") (pinfunction "VID_11") (pintype "bidirectional"))
    )
    (net (code "101") (name "Net-(IC1302A-~{RE})") (class "Default")
      (node (ref "IC1302") (pin "2") (pinfunction "~{RE}_2") (pintype "bidirectional"))
      (node (ref "IC1303") (pin "13") (pinfunction "VOB_13") (pintype "bidirectional"))
    )
    (net (code "102") (name "Net-(IC1701-VOUT_FORCE)") (class "Default")
      (node (ref "C1707") (pin "1") (pinfunction "1_1") (pintype "passive"))
      (node (ref "IC1701") (pin "5") (pinfunction "VOUT_SENSE_5") (pintype "output"))
      (node (ref "IC1701") (pin "6") (pinfunction "VOUT_FORCE_6") (pintype "output"))
      (node (ref "X1701") (pin "1") (pinfunction "1_1") (pintype "passive"))
      (node (ref "X1701") (pin "3") (pinfunction "3_3") (pintype "passive"))
      (node (ref "X1701") (pin "5") (pinfunction "5_5") (pintype "passive"))
      (node (ref "X1701") (pin "7") (pinfunction "7_7") (pintype "passive"))
      (node (ref "X1701") (pin "9") (pinfunction "9_9") (pintype "passive"))
    )
    (net (code "103") (name "Net-(IC1902A-VIA)") (class "Default")
      (node (ref "D1901") (pin "C") (pinfunction "C_C") (pintype "passive"))
      (node (ref "IC1902") (pin "3") (pinfunction "VIA_3") (pintype "bidirectional"))
      (node (ref "R1901") (pin "1") (pinfunction "1_1") (pintype "passive"))
    )
    (net (code "104") (name "Net-(IC1902A-VIB)") (class "Default")
      (node (ref "D1902") (pin "C") (pinfunction "C_C") (pintype "passive"))
      (node (ref "IC1902") (pin "4") (pinfunction "VIB_4") (pintype "bidirectional"))
      (node (ref "R1902") (pin "1") (pinfunction "1_1") (pintype "passive"))
    )
    (net (code "105") (name "Net-(IC1903A-VIA)") (class "Default")
      (node (ref "D1903") (pin "C") (pinfunction "C_C") (pintype "passive"))
      (node (ref "IC1903") (pin "3") (pinfunction "VIA_3") (pintype "bidirectional"))
      (node (ref "R1905") (pin "1") (pinfunction "1_1") (pintype "passive"))
    )
    (net (code "106") (name "Net-(IC1903A-VIB)") (class "Default")
      (node (ref "D1904") (pin "C") (pinfunction "C_C") (pintype "passive"))
      (node (ref "IC1903") (pin "4") (pinfunction "VIB_4") (pintype "bidirectional"))
      (node (ref "R1906") (pin "1") (pinfunction "1_1") (pintype "passive"))
    )
    (net (code "107") (name "Net-(IC2001-K)") (class "Default")
      (node (ref "IC2001") (pin "2") (pinfunction "K_2") (pintype "passive"))
      (node (ref "R2005") (pin "2") (pinfunction "2_2") (pintype "passive"))
    )
    (net (code "108") (name "Net-(IC2002-K)") (class "Default")
      (node (ref "IC2002") (pin "2") (pinfunction "K_2") (pintype "passive"))
      (node (ref "R2006") (pin "2") (pinfunction "2_2") (pintype "passive"))
    )
    (net (code "109") (name "Net-(IC2003-K)") (class "Default")
      (node (ref "IC2003") (pin "2") (pinfunction "K_2") (pintype "passive"))
      (node (ref "R2011") (pin "2") (pinfunction "2_2") (pintype "passive"))
    )
    (net (code "110") (name "Net-(IC2004-K)") (class "Default")
      (node (ref "IC2004") (pin "2") (pinfunction "K_2") (pintype "passive"))
      (node (ref "R2012") (pin "2") (pinfunction "2_2") (pintype "passive"))
    )
    (net (code "111") (name "Net-(IC2005-K)") (class "Default")
      (node (ref "IC2005") (pin "2") (pinfunction "K_2") (pintype "passive"))
      (node (ref "R2017") (pin "2") (pinfunction "2_2") (pintype "passive"))
    )
    (net (code "112") (name "Net-(IC2006-K)") (class "Default")
      (node (ref "IC2006") (pin "2") (pinfunction "K_2") (pintype "passive"))
      (node (ref "R2018") (pin "2") (pinfunction "2_2") (pintype "passive"))
    )
    (net (code "113") (name "Net-(LSP807-MP)") (class "Default")
      (node (ref "LSP807") (pin "P$1") (pinfunction "MP_P$1") (pintype "passive"))
      (node (ref "R805") (pin "1") (pinfunction "1_1") (pintype "passive"))
      (node (ref "R806") (pin "1") (pinfunction "1_1") (pintype "passive"))
      (node (ref "T801") (pin "1") (pinfunction "G_1") (pintype "passive"))
    )
    (net (code "114") (name "Net-(R1502-Pad1)") (class "Default")
      (node (ref "R1502") (pin "1") (pinfunction "1_1") (pintype "passive"))
      (node (ref "SLOT1501") (pin "1") (pinfunction "1_1") (pintype "passive"))
    )
    (net (code "115") (name "Net-(R1503-Pad1)") (class "Default")
      (node (ref "R1503") (pin "1") (pinfunction "1_1") (pintype "passive"))
      (node (ref "SLOT1501") (pin "8") (pinfunction "8_8") (pintype "passive"))
    )
    (net (code "116") (name "Net-(T901-G)") (class "Default")
      (node (ref "R901") (pin "1") (pinfunction "1_1") (pintype "passive"))
      (node (ref "R902") (pin "1") (pinfunction "1_1") (pintype "passive"))
      (node (ref "T901") (pin "1") (pinfunction "G_1") (pintype "passive"))
    )
    (net (code "117") (name "Net-(T1001-D)") (class "Default")
      (node (ref "R1003") (pin "1") (pinfunction "1_1") (pintype "passive"))
      (node (ref "T1001") (pin "3") (pinfunction "D_3") (pintype "passive"))
    )
    (net (code "118") (name "Net-(T1001-G)") (class "Default")
      (node (ref "R1001") (pin "1") (pinfunction "1_1") (pintype "passive"))
      (node (ref "R1002") (pin "2") (pinfunction "2_2") (pintype "passive"))
      (node (ref "T1001") (pin "1") (pinfunction "G_1") (pintype "passive"))
    )
    (net (code "119") (name "Net-(T1002-D)") (class "Default")
      (node (ref "R1006") (pin "1") (pinfunction "1_1") (pintype "passive"))
      (node (ref "T1002") (pin "3") (pinfunction "D_3") (pintype "passive"))
    )
    (net (code "120") (name "Net-(T1002-G)") (class "Default")
      (node (ref "R1004") (pin "1") (pinfunction "1_1") (pintype "passive"))
      (node (ref "R1005") (pin "2") (pinfunction "2_2") (pintype "passive"))
      (node (ref "T1002") (pin "1") (pinfunction "G_1") (pintype "passive"))
    )
    (net (code "121") (name "Net-(T1003-D)") (class "Default")
      (node (ref "R1009") (pin "1") (pinfunction "1_1") (pintype "passive"))
      (node (ref "T1003") (pin "3") (pinfunction "D_3") (pintype "passive"))
    )
    (net (code "122") (name "Net-(T1003-G)") (class "Default")
      (node (ref "R1007") (pin "1") (pinfunction "1_1") (pintype "passive"))
      (node (ref "R1008") (pin "2") (pinfunction "2_2") (pintype "passive"))
      (node (ref "T1003") (pin "1") (pinfunction "G_1") (pintype "passive"))
    )
    (net (code "123") (name "Net-(T1501-D)") (class "Default")
      (node (ref "L1501") (pin "2") (pinfunction "2_2") (pintype "passive"))
      (node (ref "T1501") (pin "3") (pinfunction "D_3") (pintype "passive"))
    )
    (net (code "124") (name "Net-(T2001-D)") (class "Default")
      (node (ref "R2005") (pin "1") (pinfunction "1_1") (pintype "passive"))
      (node (ref "T2001") (pin "3") (pinfunction "D_3") (pintype "passive"))
    )
    (net (code "125") (name "Net-(T2001-G)") (class "Default")
      (node (ref "R2001") (pin "1") (pinfunction "1_1") (pintype "passive"))
      (node (ref "R2003") (pin "2") (pinfunction "2_2") (pintype "passive"))
      (node (ref "T2001") (pin "1") (pinfunction "G_1") (pintype "passive"))
    )
    (net (code "126") (name "Net-(T2002-D)") (class "Default")
      (node (ref "R2006") (pin "1") (pinfunction "1_1") (pintype "passive"))
      (node (ref "T2002") (pin "3") (pinfunction "D_3") (pintype "passive"))
    )
    (net (code "127") (name "Net-(T2002-G)") (class "Default")
      (node (ref "R2002") (pin "1") (pinfunction "1_1") (pintype "passive"))
      (node (ref "R2004") (pin "2") (pinfunction "2_2") (pintype "passive"))
      (node (ref "T2002") (pin "1") (pinfunction "G_1") (pintype "passive"))
    )
    (net (code "128") (name "Net-(T2003-D)") (class "Default")
      (node (ref "R2011") (pin "1") (pinfunction "1_1") (pintype "passive"))
      (node (ref "T2003") (pin "3") (pinfunction "D_3") (pintype "passive"))
    )
    (net (code "129") (name "Net-(T2003-G)") (class "Default")
      (node (ref "R2007") (pin "1") (pinfunction "1_1") (pintype "passive"))
      (node (ref "R2009") (pin "2") (pinfunction "2_2") (pintype "passive"))
      (node (ref "T2003") (pin "1") (pinfunction "G_1") (pintype "passive"))
    )
    (net (code "130") (name "Net-(T2004-D)") (class "Default")
      (node (ref "R2012") (pin "1") (pinfunction "1_1") (pintype "passive"))
      (node (ref "T2004") (pin "3") (pinfunction "D_3") (pintype "passive"))
    )
    (net (code "131") (name "Net-(T2004-G)") (class "Default")
      (node (ref "R2008") (pin "1") (pinfunction "1_1") (pintype "passive"))
      (node (ref "R2010") (pin "2") (pinfunction "2_2") (pintype "passive"))
      (node (ref "T2004") (pin "1") (pinfunction "G_1") (pintype "passive"))
    )
    (net (code "132") (name "Net-(T2005-D)") (class "Default")
      (node (ref "R2017") (pin "1") (pinfunction "1_1") (pintype "passive"))
      (node (ref "T2005") (pin "3") (pinfunction "D_3") (pintype "passive"))
    )
    (net (code "133") (name "Net-(T2005-G)") (class "Default")
      (node (ref "R2013") (pin "1") (pinfunction "1_1") (pintype "passive"))
      (node (ref "R2015") (pin "2") (pinfunction "2_2") (pintype "passive"))
      (node (ref "T2005") (pin "1") (pinfunction "G_1") (pintype "passive"))
    )
    (net (code "134") (name "Net-(T2006-D)") (class "Default")
      (node (ref "R2018") (pin "1") (pinfunction "1_1") (pintype "passive"))
      (node (ref "T2006") (pin "3") (pinfunction "D_3") (pintype "passive"))
    )
    (net (code "135") (name "Net-(T2006-G)") (class "Default")
      (node (ref "R2014") (pin "1") (pinfunction "1_1") (pintype "passive"))
      (node (ref "R2016") (pin "2") (pinfunction "2_2") (pintype "passive"))
      (node (ref "T2006") (pin "1") (pinfunction "G_1") (pintype "passive"))
    )
    (net (code "136") (name "RS485_A_EXT") (class "Default")
      (node (ref "IC1302") (pin "6") (pinfunction "A_6") (pintype "bidirectional"))
      (node (ref "X1301") (pin "3") (pinfunction "3_3") (pintype "passive"))
    )
    (net (code "137") (name "RS485_B_EXT") (class "Default")
      (node (ref "IC1302") (pin "7") (pinfunction "B_7") (pintype "bidirectional"))
      (node (ref "X1301") (pin "2") (pinfunction "2_2") (pintype "passive"))
    )
    (net (code "138") (name "RS485_MCU_0_DE") (class "Default")
      (node (ref "IC1303") (pin "5") (pinfunction "VIC_5") (pintype "bidirectional"))
      (node (ref "JP2202") (pin "15") (pinfunction "15_15") (pintype "passive"))
      (node (ref "LSP1302") (pin "P$1") (pinfunction "MP_P$1") (pintype "passive"))
    )
    (net (code "139") (name "RS485_MCU_0_NRE") (class "Default")
      (node (ref "IC1303") (pin "4") (pinfunction "VIB_4") (pintype "bidirectional"))
      (node (ref "JP2202") (pin "14") (pinfunction "14_14") (pintype "passive"))
      (node (ref "LSP1303") (pin "P$1") (pinfunction "MP_P$1") (pintype "passive"))
    )
    (net (code "140") (name "RS485_MCU_0_RX") (class "Default")
      (node (ref "IC1303") (pin "6") (pinfunction "VOD_6") (pintype "bidirectional"))
      (node (ref "JP2202") (pin "13") (pinfunction "13_13") (pintype "passive"))
      (node (ref "LSP1304") (pin "P$1") (pinfunction "MP_P$1") (pintype "passive"))
    )
    (net (code "141") (name "RS485_MCU_0_TX") (class "Default")
      (node (ref "IC1303") (pin "3") (pinfunction "VIA_3") (pintype "bidirectional"))
      (node (ref "JP2202") (pin "12") (pinfunction "12_12") (pintype "passive"))
      (node (ref "LSP1301") (pin "P$1") (pinfunction "MP_P$1") (pintype "passive"))
    )
    (net (code "142") (name "SDCARD_SUPPLY") (class "Default")
      (node (ref "C1501") (pin "2") (pinfunction "2_2") (pintype "passive"))
      (node (ref "C1502") (pin "1") (pinfunction "1_1") (pintype "passive"))
      (node (ref "L1501") (pin "1") (pinfunction "1_1") (pintype "passive"))
      (node (ref "R1502") (pin "2") (pinfunction "2_2") (pintype "passive"))
      (node (ref "R1503") (pin "2") (pinfunction "2_2") (pintype "passive"))
      (node (ref "R1504") (pin "2") (pinfunction "2_2") (pintype "passive"))
      (node (ref "R1506") (pin "2") (pinfunction "2_2") (pintype "passive"))
      (node (ref "R1507") (pin "2") (pinfunction "2_2") (pintype "passive"))
      (node (ref "SLOT1501") (pin "4") (pinfunction "4_4") (pintype "passive"))
    )
    (net (code "143") (name "SDCARD_SUPPLY_CONTROL") (class "Default")
      (node (ref "JP2201") (pin "22") (pinfunction "22_22") (pintype "passive"))
      (node (ref "LSP1501") (pin "P$1") (pinfunction "MP_P$1") (pintype "passive"))
      (node (ref "R1501") (pin "1") (pinfunction "1_1") (pintype "passive"))
      (node (ref "T1501") (pin "1") (pinfunction "G_1") (pintype "passive"))
    )
    (net (code "144") (name "SUPPLY_EXT_0") (class "Default")
      (node (ref "C1101") (pin "1") (pinfunction "1_1") (pintype "passive"))
      (node (ref "C1102") (pin "1") (pinfunction "1_1") (pintype "passive"))
      (node (ref "C1901") (pin "1") (pinfunction "1_1") (pintype "passive"))
      (node (ref "C1902") (pin "1") (pinfunction "1_1") (pintype "passive"))
      (node (ref "IC1101") (pin "3") (pinfunction "IN_3") (pintype "input"))
      (node (ref "IC1901") (pin "3") (pinfunction "IN_3") (pintype "input"))
      (node (ref "SV901") (pin "3") (pinfunction "3_3") (pintype "passive"))
    )
    (net (code "145") (name "SUPPLY_EXT_1") (class "Default")
      (node (ref "C801") (pin "2") (pinfunction "2_2") (pintype "passive"))
      (node (ref "C802") (pin "2") (pinfunction "2_2") (pintype "passive"))
      (node (ref "IC801") (pin "1") (pinfunction "IN_1") (pintype "input"))
      (node (ref "X801") (pin "2") (pinfunction "2_2") (pintype "passive"))
    )
    (net (code "146") (name "SUPPLY_EXT_2") (class "Default")
      (node (ref "F1001") (pin "2") (pinfunction "2_2") (pintype "bidirectional"))
      (node (ref "F1002") (pin "2") (pinfunction "2_2") (pintype "bidirectional"))
      (node (ref "F1003") (pin "2") (pinfunction "2_2") (pintype "bidirectional"))
      (node (ref "SV901") (pin "5") (pinfunction "5_5") (pintype "passive"))
      (node (ref "SV901") (pin "7") (pinfunction "7_7") (pintype "passive"))
    )
    (net (code "147") (name "unconnected-(JP2201-Pad8)") (class "Default")
      (node (ref "JP2201") (pin "8") (pinfunction "8_8") (pintype "passive"))
    )
    (net (code "148") (name "unconnected-(JP2201-Pad24)") (class "Default")
      (node (ref "JP2201") (pin "24") (pinfunction "24_24") (pintype "passive"))
    )
    (net (code "149") (name "unconnected-(JP2202-Pad24)") (class "Default")
      (node (ref "JP2202") (pin "24") (pinfunction "24_24") (pintype "passive"))
    )
  )
)
